# CPU_Power.net
KiCad netlist of a schematic drawn in Altium Designer
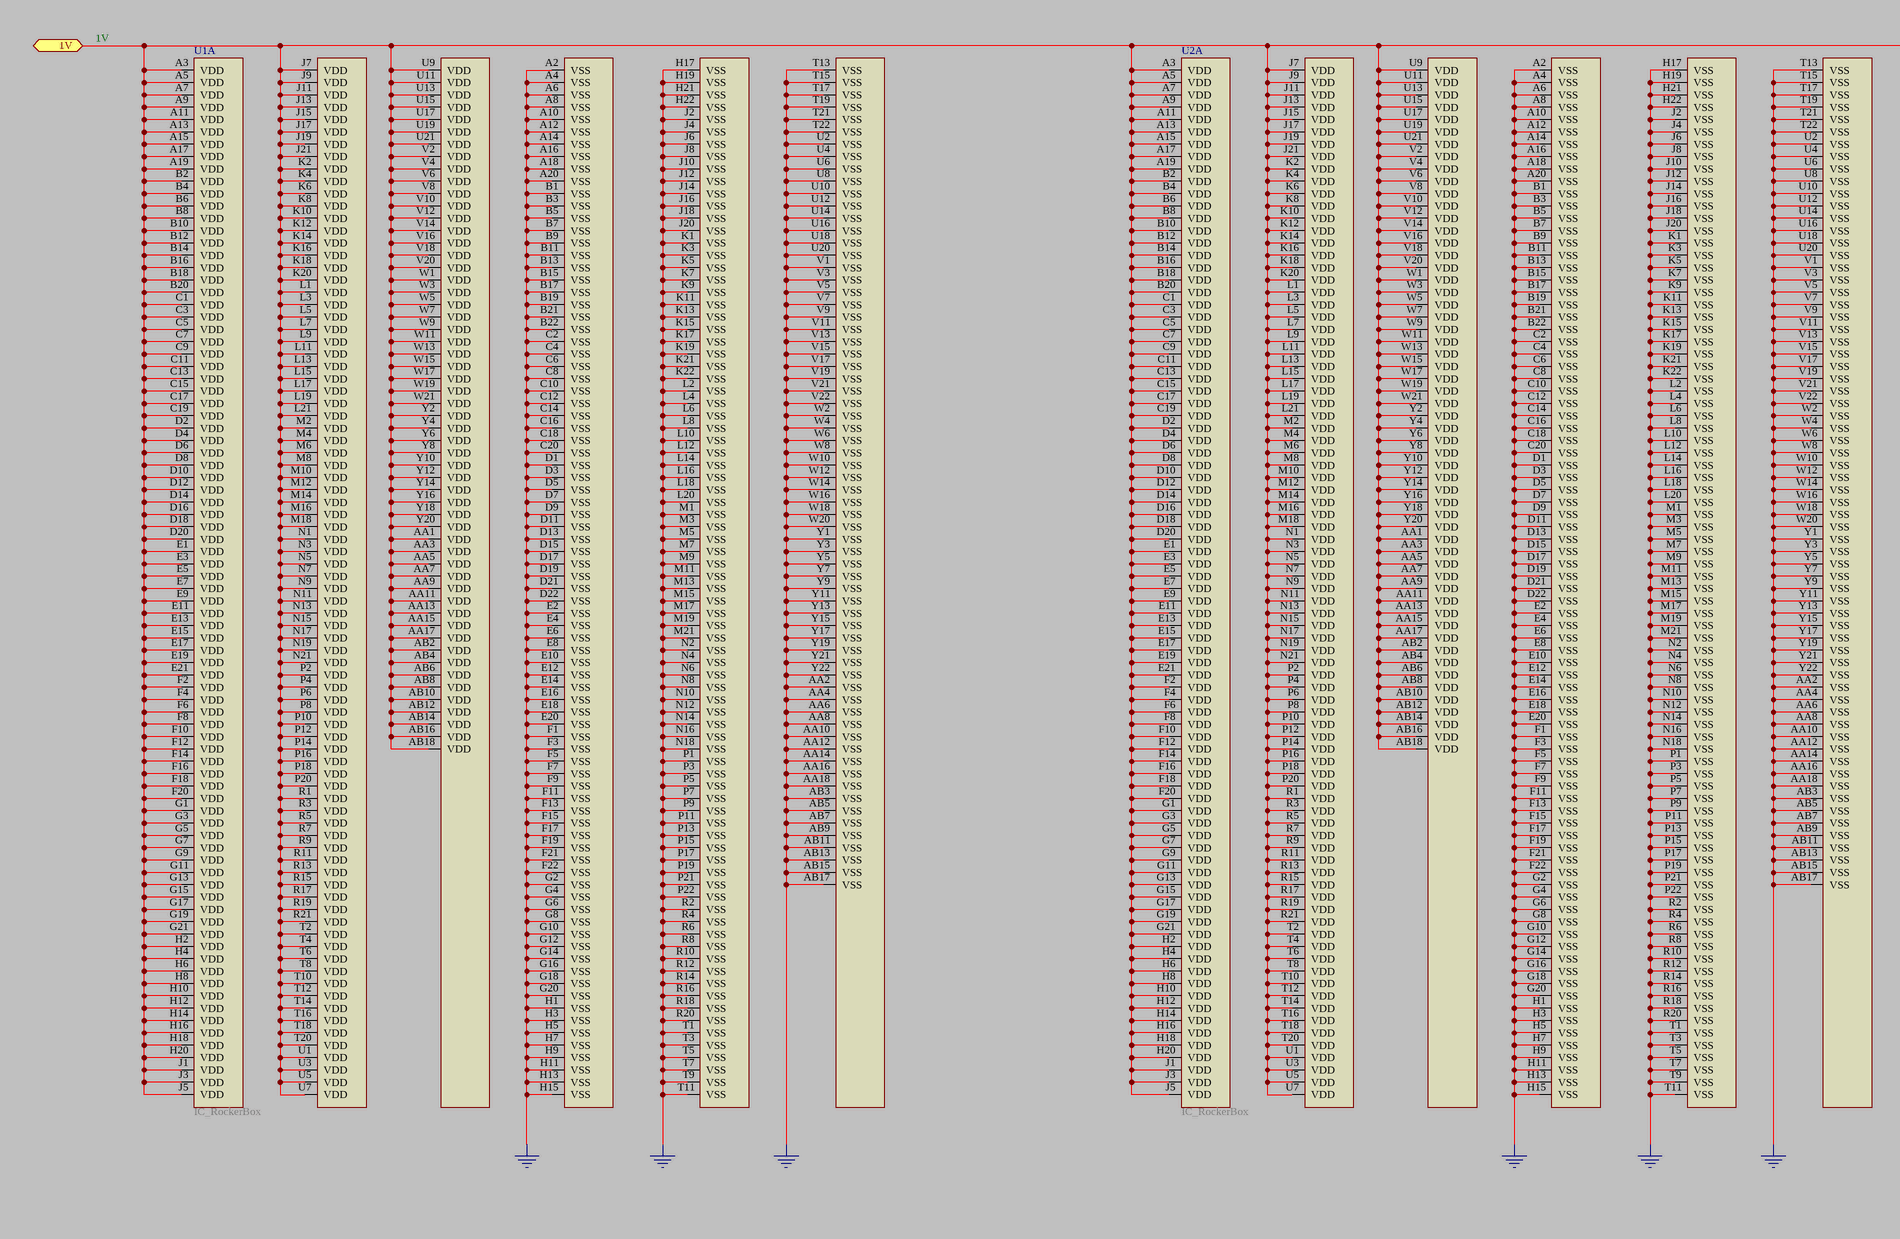
[diagram p0: CPU_Power.SchDoc, top left]
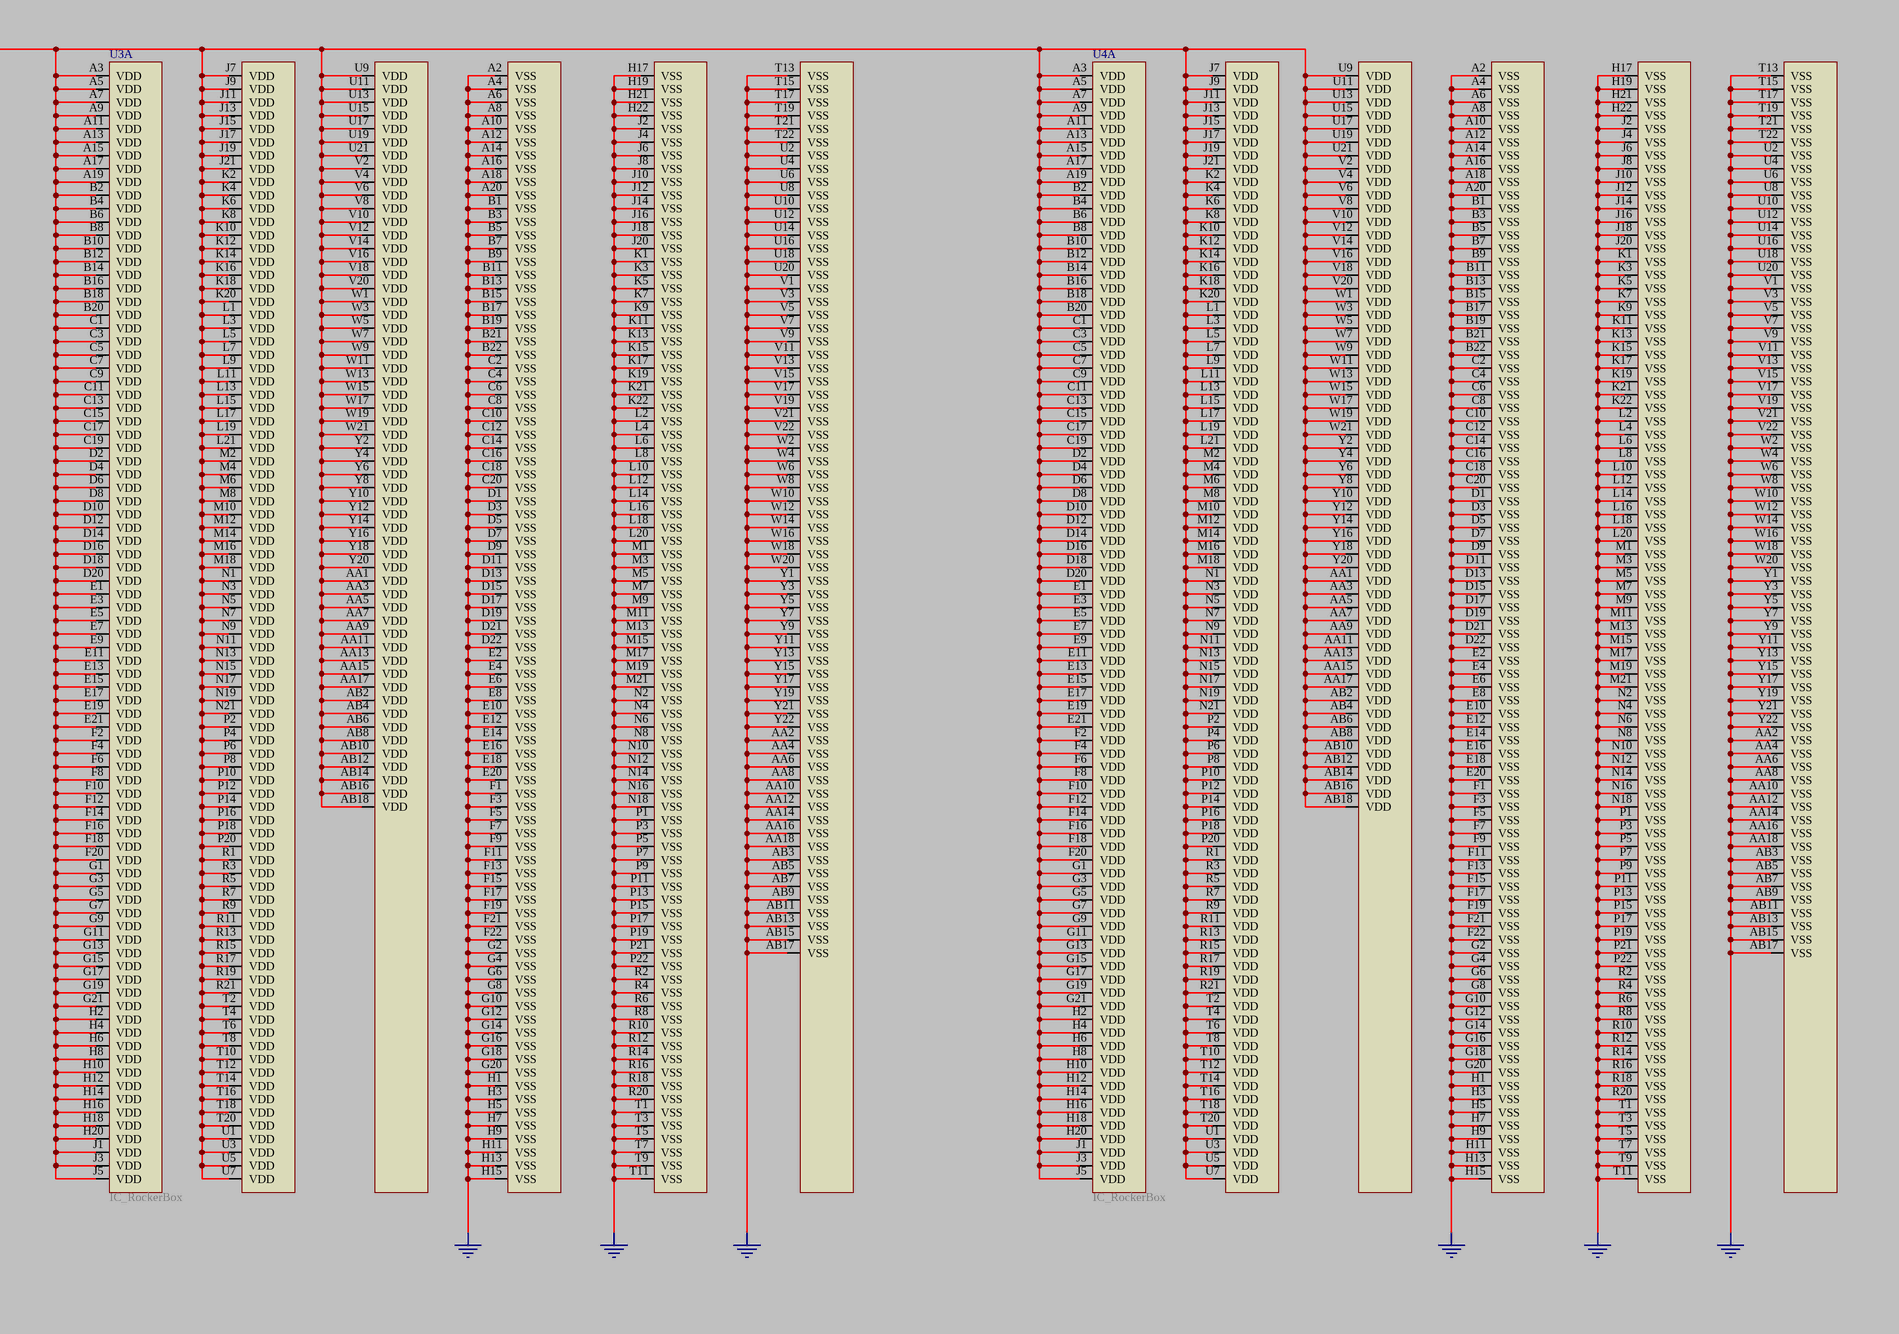
[diagram p1: CPU_Power.SchDoc, top right]
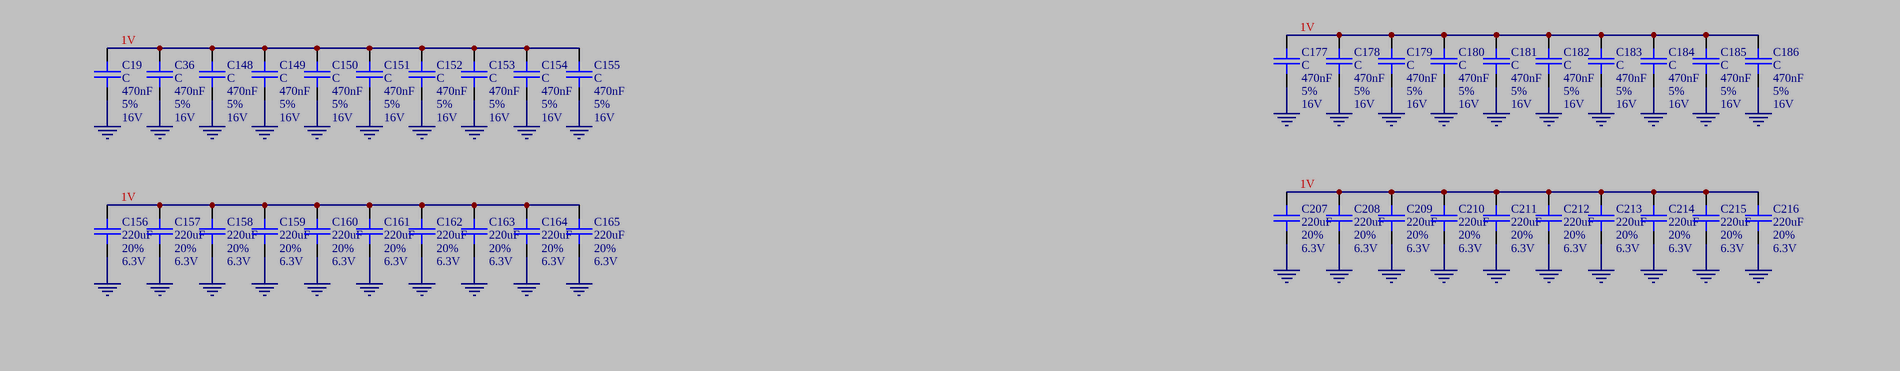
[diagram p2: CPU_Power.SchDoc, bottom left]
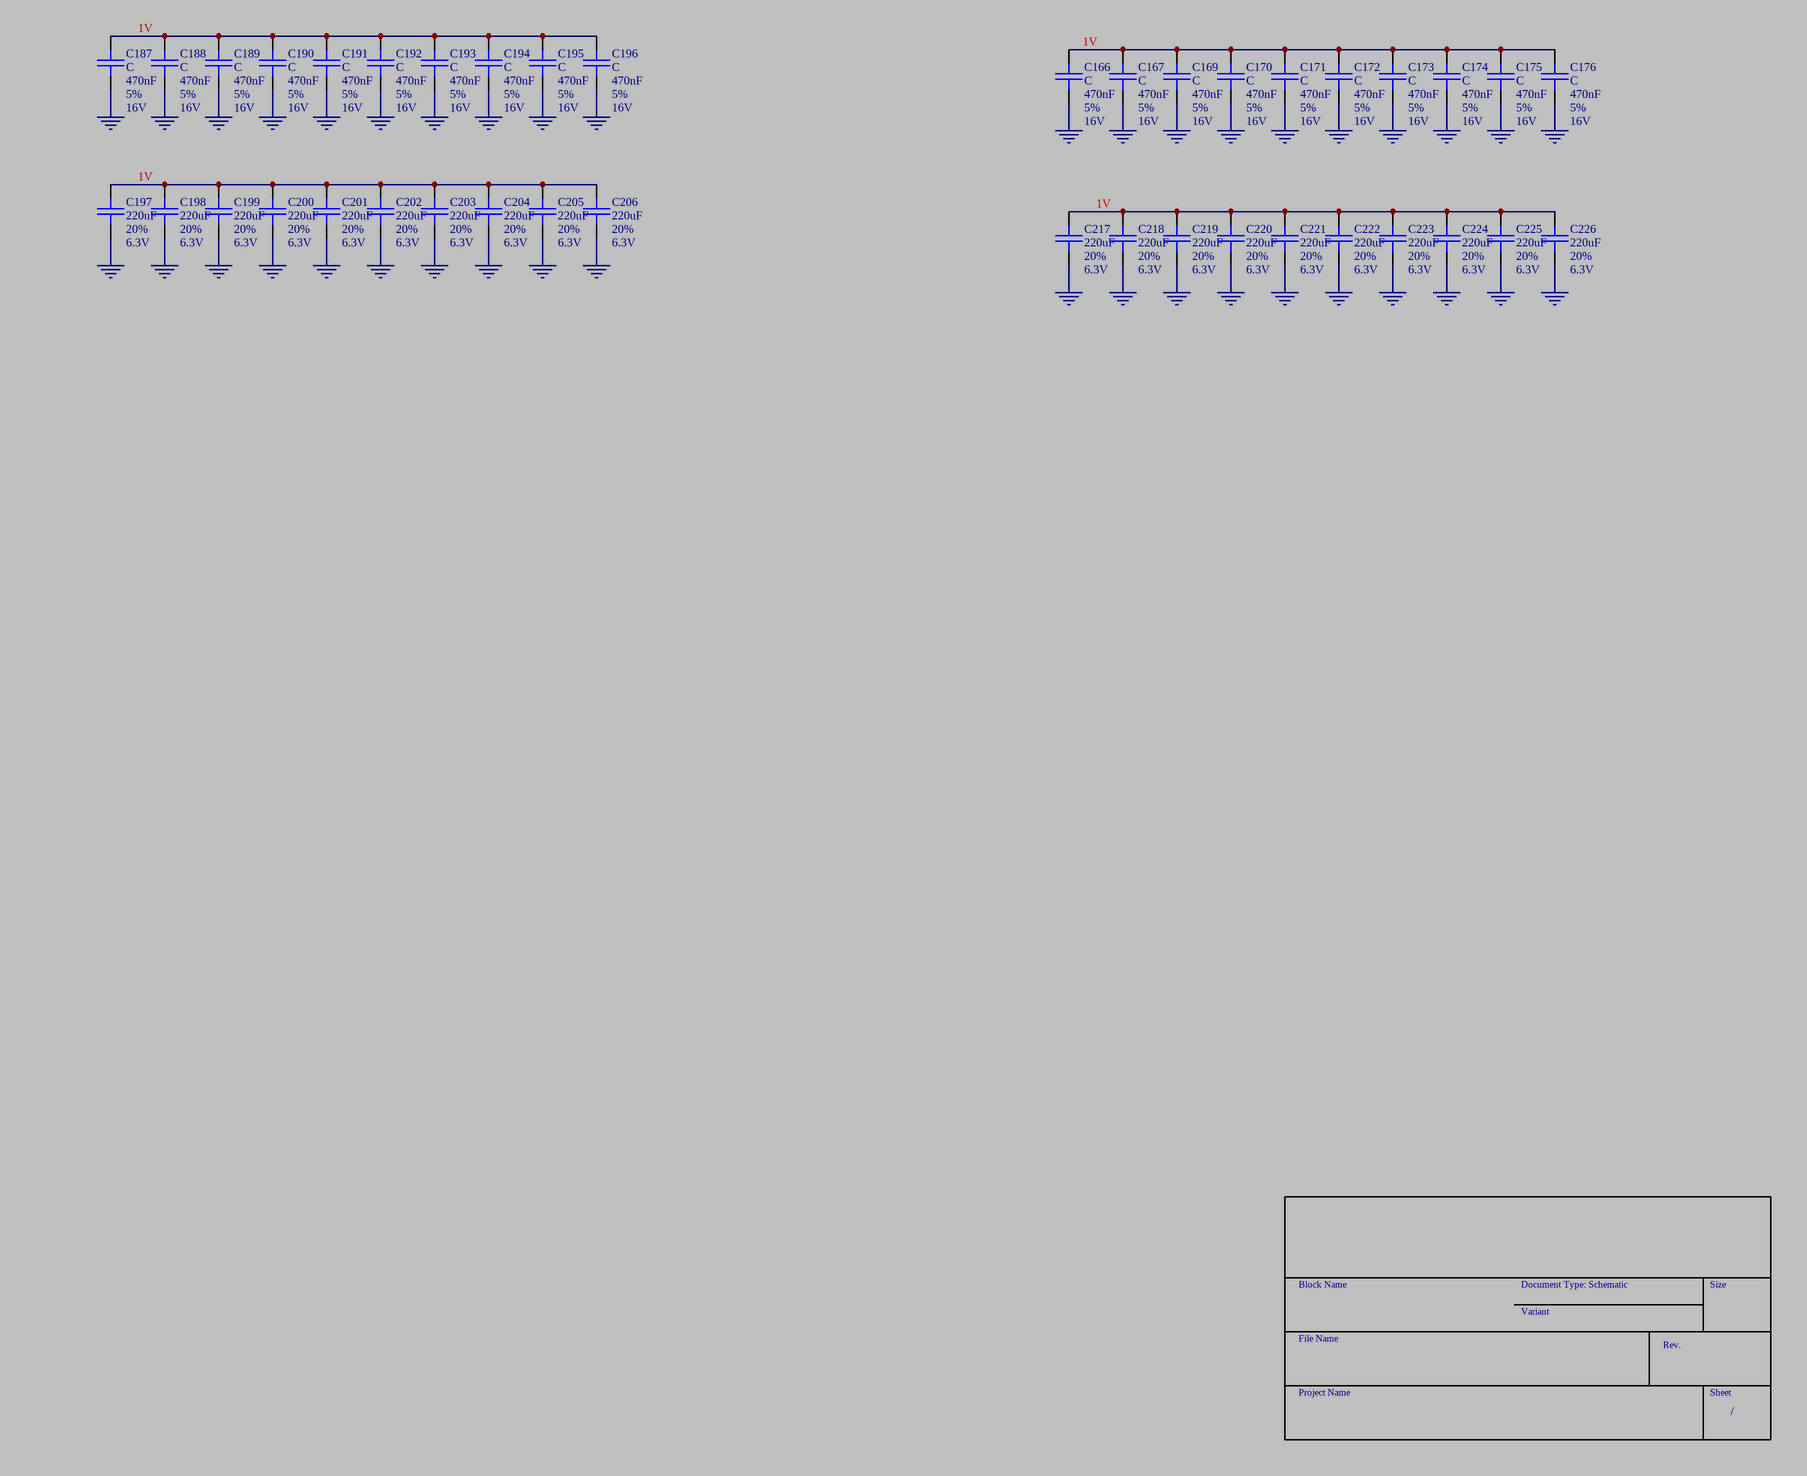
[diagram p3: CPU_Power.SchDoc, bottom right]

(export (version "E")
  (design (tool "Eeschema 10.0.6"))
  (components
    (comp (ref "C19")
      (value "C")
      (footprint "SMD_0603_CAPC1608X95N")
      (fields
        (field (name "DB_PART_NUMBER") "CAP000028169")
        (field (name "DB_VALUE") "470nF")
        (field (name "DB_TOLERANCE") "5%")
        (field (name "DB_VOLTAGE") "16V")
        (field (name "DB_MANUFACTURER_PART") "KEMET    C0603C474J4RAC")
      )
      (libsource (lib "Database_Libs1") (part "C"))
    )
    (comp (ref "C36")
      (value "C")
      (footprint "SMD_0603_CAPC1608X95N")
      (fields
        (field (name "DB_PART_NUMBER") "CAP000028169")
        (field (name "DB_VALUE") "470nF")
        (field (name "DB_TOLERANCE") "5%")
        (field (name "DB_VOLTAGE") "16V")
        (field (name "DB_MANUFACTURER_PART") "KEMET    C0603C474J4RAC")
      )
      (libsource (lib "Database_Libs1") (part "C"))
    )
    (comp (ref "C148")
      (value "C")
      (footprint "SMD_0603_CAPC1608X95N")
      (fields
        (field (name "DB_PART_NUMBER") "CAP000028169")
        (field (name "DB_VALUE") "470nF")
        (field (name "DB_TOLERANCE") "5%")
        (field (name "DB_VOLTAGE") "16V")
        (field (name "DB_MANUFACTURER_PART") "KEMET    C0603C474J4RAC")
      )
      (libsource (lib "Database_Libs1") (part "C"))
    )
    (comp (ref "C149")
      (value "C")
      (footprint "SMD_0603_CAPC1608X95N")
      (fields
        (field (name "DB_PART_NUMBER") "CAP000028169")
        (field (name "DB_VALUE") "470nF")
        (field (name "DB_TOLERANCE") "5%")
        (field (name "DB_VOLTAGE") "16V")
        (field (name "DB_MANUFACTURER_PART") "KEMET    C0603C474J4RAC")
      )
      (libsource (lib "Database_Libs1") (part "C"))
    )
    (comp (ref "C150")
      (value "C")
      (footprint "SMD_0603_CAPC1608X95N")
      (fields
        (field (name "DB_PART_NUMBER") "CAP000028169")
        (field (name "DB_VALUE") "470nF")
        (field (name "DB_TOLERANCE") "5%")
        (field (name "DB_VOLTAGE") "16V")
        (field (name "DB_MANUFACTURER_PART") "KEMET    C0603C474J4RAC")
      )
      (libsource (lib "Database_Libs1") (part "C"))
    )
    (comp (ref "C151")
      (value "C")
      (footprint "SMD_0603_CAPC1608X95N")
      (fields
        (field (name "DB_PART_NUMBER") "CAP000028169")
        (field (name "DB_VALUE") "470nF")
        (field (name "DB_TOLERANCE") "5%")
        (field (name "DB_VOLTAGE") "16V")
        (field (name "DB_MANUFACTURER_PART") "KEMET    C0603C474J4RAC")
      )
      (libsource (lib "Database_Libs1") (part "C"))
    )
    (comp (ref "C152")
      (value "C")
      (footprint "SMD_0603_CAPC1608X95N")
      (fields
        (field (name "DB_PART_NUMBER") "CAP000028169")
        (field (name "DB_VALUE") "470nF")
        (field (name "DB_TOLERANCE") "5%")
        (field (name "DB_VOLTAGE") "16V")
        (field (name "DB_MANUFACTURER_PART") "KEMET    C0603C474J4RAC")
      )
      (libsource (lib "Database_Libs1") (part "C"))
    )
    (comp (ref "C153")
      (value "C")
      (footprint "SMD_0603_CAPC1608X95N")
      (fields
        (field (name "DB_PART_NUMBER") "CAP000028169")
        (field (name "DB_VALUE") "470nF")
        (field (name "DB_TOLERANCE") "5%")
        (field (name "DB_VOLTAGE") "16V")
        (field (name "DB_MANUFACTURER_PART") "KEMET    C0603C474J4RAC")
      )
      (libsource (lib "Database_Libs1") (part "C"))
    )
    (comp (ref "C154")
      (value "C")
      (footprint "SMD_0603_CAPC1608X95N")
      (fields
        (field (name "DB_PART_NUMBER") "CAP000028169")
        (field (name "DB_VALUE") "470nF")
        (field (name "DB_TOLERANCE") "5%")
        (field (name "DB_VOLTAGE") "16V")
        (field (name "DB_MANUFACTURER_PART") "KEMET    C0603C474J4RAC")
      )
      (libsource (lib "Database_Libs1") (part "C"))
    )
    (comp (ref "C155")
      (value "C")
      (footprint "SMD_0603_CAPC1608X95N")
      (fields
        (field (name "DB_PART_NUMBER") "CAP000028169")
        (field (name "DB_VALUE") "470nF")
        (field (name "DB_TOLERANCE") "5%")
        (field (name "DB_VOLTAGE") "16V")
        (field (name "DB_MANUFACTURER_PART") "KEMET    C0603C474J4RAC")
      )
      (libsource (lib "Database_Libs1") (part "C"))
    )
    (comp (ref "C156")
      (value "C")
      (footprint "SMD_1210_CAPC3225X279N")
      (fields
        (field (name "DB_PART_NUMBER") "CAP000047355")
        (field (name "DB_VALUE") "220uF")
        (field (name "DB_TOLERANCE") "20%")
        (field (name "DB_VOLTAGE") "6.3V")
        (field (name "DB_MANUFACTURER_PART") "SAMSUNG    CL32A227MQVNNNE")
        (field (name "DB_APPROVED_BY") "VSN")
      )
      (libsource (lib "Database_Libs1") (part "C"))
    )
    (comp (ref "C157")
      (value "C")
      (footprint "SMD_1210_CAPC3225X279N")
      (fields
        (field (name "DB_PART_NUMBER") "CAP000047355")
        (field (name "DB_VALUE") "220uF")
        (field (name "DB_TOLERANCE") "20%")
        (field (name "DB_VOLTAGE") "6.3V")
        (field (name "DB_MANUFACTURER_PART") "SAMSUNG    CL32A227MQVNNNE")
        (field (name "DB_APPROVED_BY") "VSN")
      )
      (libsource (lib "Database_Libs1") (part "C"))
    )
    (comp (ref "C158")
      (value "C")
      (footprint "SMD_1210_CAPC3225X279N")
      (fields
        (field (name "DB_PART_NUMBER") "CAP000047355")
        (field (name "DB_VALUE") "220uF")
        (field (name "DB_TOLERANCE") "20%")
        (field (name "DB_VOLTAGE") "6.3V")
        (field (name "DB_MANUFACTURER_PART") "SAMSUNG    CL32A227MQVNNNE")
        (field (name "DB_APPROVED_BY") "VSN")
      )
      (libsource (lib "Database_Libs1") (part "C"))
    )
    (comp (ref "C159")
      (value "C")
      (footprint "SMD_1210_CAPC3225X279N")
      (fields
        (field (name "DB_PART_NUMBER") "CAP000047355")
        (field (name "DB_VALUE") "220uF")
        (field (name "DB_TOLERANCE") "20%")
        (field (name "DB_VOLTAGE") "6.3V")
        (field (name "DB_MANUFACTURER_PART") "SAMSUNG    CL32A227MQVNNNE")
        (field (name "DB_APPROVED_BY") "VSN")
      )
      (libsource (lib "Database_Libs1") (part "C"))
    )
    (comp (ref "C160")
      (value "C")
      (footprint "SMD_1210_CAPC3225X279N")
      (fields
        (field (name "DB_PART_NUMBER") "CAP000047355")
        (field (name "DB_VALUE") "220uF")
        (field (name "DB_TOLERANCE") "20%")
        (field (name "DB_VOLTAGE") "6.3V")
        (field (name "DB_MANUFACTURER_PART") "SAMSUNG    CL32A227MQVNNNE")
        (field (name "DB_APPROVED_BY") "VSN")
      )
      (libsource (lib "Database_Libs1") (part "C"))
    )
    (comp (ref "C161")
      (value "C")
      (footprint "SMD_1210_CAPC3225X279N")
      (fields
        (field (name "DB_PART_NUMBER") "CAP000047355")
        (field (name "DB_VALUE") "220uF")
        (field (name "DB_TOLERANCE") "20%")
        (field (name "DB_VOLTAGE") "6.3V")
        (field (name "DB_MANUFACTURER_PART") "SAMSUNG    CL32A227MQVNNNE")
        (field (name "DB_APPROVED_BY") "VSN")
      )
      (libsource (lib "Database_Libs1") (part "C"))
    )
    (comp (ref "C162")
      (value "C")
      (footprint "SMD_1210_CAPC3225X279N")
      (fields
        (field (name "DB_PART_NUMBER") "CAP000047355")
        (field (name "DB_VALUE") "220uF")
        (field (name "DB_TOLERANCE") "20%")
        (field (name "DB_VOLTAGE") "6.3V")
        (field (name "DB_MANUFACTURER_PART") "SAMSUNG    CL32A227MQVNNNE")
        (field (name "DB_APPROVED_BY") "VSN")
      )
      (libsource (lib "Database_Libs1") (part "C"))
    )
    (comp (ref "C163")
      (value "C")
      (footprint "SMD_1210_CAPC3225X279N")
      (fields
        (field (name "DB_PART_NUMBER") "CAP000047355")
        (field (name "DB_VALUE") "220uF")
        (field (name "DB_TOLERANCE") "20%")
        (field (name "DB_VOLTAGE") "6.3V")
        (field (name "DB_MANUFACTURER_PART") "SAMSUNG    CL32A227MQVNNNE")
        (field (name "DB_APPROVED_BY") "VSN")
      )
      (libsource (lib "Database_Libs1") (part "C"))
    )
    (comp (ref "C164")
      (value "C")
      (footprint "SMD_1210_CAPC3225X279N")
      (fields
        (field (name "DB_PART_NUMBER") "CAP000047355")
        (field (name "DB_VALUE") "220uF")
        (field (name "DB_TOLERANCE") "20%")
        (field (name "DB_VOLTAGE") "6.3V")
        (field (name "DB_MANUFACTURER_PART") "SAMSUNG    CL32A227MQVNNNE")
        (field (name "DB_APPROVED_BY") "VSN")
      )
      (libsource (lib "Database_Libs1") (part "C"))
    )
    (comp (ref "C165")
      (value "C")
      (footprint "SMD_1210_CAPC3225X279N")
      (fields
        (field (name "DB_PART_NUMBER") "CAP000047355")
        (field (name "DB_VALUE") "220uF")
        (field (name "DB_TOLERANCE") "20%")
        (field (name "DB_VOLTAGE") "6.3V")
        (field (name "DB_MANUFACTURER_PART") "SAMSUNG    CL32A227MQVNNNE")
        (field (name "DB_APPROVED_BY") "VSN")
      )
      (libsource (lib "Database_Libs1") (part "C"))
    )
    (comp (ref "C166")
      (value "C")
      (footprint "SMD_0603_CAPC1608X95N")
      (fields
        (field (name "DB_PART_NUMBER") "CAP000028169")
        (field (name "DB_VALUE") "470nF")
        (field (name "DB_TOLERANCE") "5%")
        (field (name "DB_VOLTAGE") "16V")
        (field (name "DB_MANUFACTURER_PART") "KEMET    C0603C474J4RAC")
      )
      (libsource (lib "Database_Libs1") (part "C"))
    )
    (comp (ref "C167")
      (value "C")
      (footprint "SMD_0603_CAPC1608X95N")
      (fields
        (field (name "DB_PART_NUMBER") "CAP000028169")
        (field (name "DB_VALUE") "470nF")
        (field (name "DB_TOLERANCE") "5%")
        (field (name "DB_VOLTAGE") "16V")
        (field (name "DB_MANUFACTURER_PART") "KEMET    C0603C474J4RAC")
      )
      (libsource (lib "Database_Libs1") (part "C"))
    )
    (comp (ref "C169")
      (value "C")
      (footprint "SMD_0603_CAPC1608X95N")
      (fields
        (field (name "DB_PART_NUMBER") "CAP000028169")
        (field (name "DB_VALUE") "470nF")
        (field (name "DB_TOLERANCE") "5%")
        (field (name "DB_VOLTAGE") "16V")
        (field (name "DB_MANUFACTURER_PART") "KEMET    C0603C474J4RAC")
      )
      (libsource (lib "Database_Libs1") (part "C"))
    )
    (comp (ref "C170")
      (value "C")
      (footprint "SMD_0603_CAPC1608X95N")
      (fields
        (field (name "DB_PART_NUMBER") "CAP000028169")
        (field (name "DB_VALUE") "470nF")
        (field (name "DB_TOLERANCE") "5%")
        (field (name "DB_VOLTAGE") "16V")
        (field (name "DB_MANUFACTURER_PART") "KEMET    C0603C474J4RAC")
      )
      (libsource (lib "Database_Libs1") (part "C"))
    )
    (comp (ref "C171")
      (value "C")
      (footprint "SMD_0603_CAPC1608X95N")
      (fields
        (field (name "DB_PART_NUMBER") "CAP000028169")
        (field (name "DB_VALUE") "470nF")
        (field (name "DB_TOLERANCE") "5%")
        (field (name "DB_VOLTAGE") "16V")
        (field (name "DB_MANUFACTURER_PART") "KEMET    C0603C474J4RAC")
      )
      (libsource (lib "Database_Libs1") (part "C"))
    )
    (comp (ref "C172")
      (value "C")
      (footprint "SMD_0603_CAPC1608X95N")
      (fields
        (field (name "DB_PART_NUMBER") "CAP000028169")
        (field (name "DB_VALUE") "470nF")
        (field (name "DB_TOLERANCE") "5%")
        (field (name "DB_VOLTAGE") "16V")
        (field (name "DB_MANUFACTURER_PART") "KEMET    C0603C474J4RAC")
      )
      (libsource (lib "Database_Libs1") (part "C"))
    )
    (comp (ref "C173")
      (value "C")
      (footprint "SMD_0603_CAPC1608X95N")
      (fields
        (field (name "DB_PART_NUMBER") "CAP000028169")
        (field (name "DB_VALUE") "470nF")
        (field (name "DB_TOLERANCE") "5%")
        (field (name "DB_VOLTAGE") "16V")
        (field (name "DB_MANUFACTURER_PART") "KEMET    C0603C474J4RAC")
      )
      (libsource (lib "Database_Libs1") (part "C"))
    )
    (comp (ref "C174")
      (value "C")
      (footprint "SMD_0603_CAPC1608X95N")
      (fields
        (field (name "DB_PART_NUMBER") "CAP000028169")
        (field (name "DB_VALUE") "470nF")
        (field (name "DB_TOLERANCE") "5%")
        (field (name "DB_VOLTAGE") "16V")
        (field (name "DB_MANUFACTURER_PART") "KEMET    C0603C474J4RAC")
      )
      (libsource (lib "Database_Libs1") (part "C"))
    )
    (comp (ref "C175")
      (value "C")
      (footprint "SMD_0603_CAPC1608X95N")
      (fields
        (field (name "DB_PART_NUMBER") "CAP000028169")
        (field (name "DB_VALUE") "470nF")
        (field (name "DB_TOLERANCE") "5%")
        (field (name "DB_VOLTAGE") "16V")
        (field (name "DB_MANUFACTURER_PART") "KEMET    C0603C474J4RAC")
      )
      (libsource (lib "Database_Libs1") (part "C"))
    )
    (comp (ref "C176")
      (value "C")
      (footprint "SMD_0603_CAPC1608X95N")
      (fields
        (field (name "DB_PART_NUMBER") "CAP000028169")
        (field (name "DB_VALUE") "470nF")
        (field (name "DB_TOLERANCE") "5%")
        (field (name "DB_VOLTAGE") "16V")
        (field (name "DB_MANUFACTURER_PART") "KEMET    C0603C474J4RAC")
      )
      (libsource (lib "Database_Libs1") (part "C"))
    )
    (comp (ref "C177")
      (value "C")
      (footprint "SMD_0603_CAPC1608X95N")
      (fields
        (field (name "DB_PART_NUMBER") "CAP000028169")
        (field (name "DB_VALUE") "470nF")
        (field (name "DB_TOLERANCE") "5%")
        (field (name "DB_VOLTAGE") "16V")
        (field (name "DB_MANUFACTURER_PART") "KEMET    C0603C474J4RAC")
      )
      (libsource (lib "Database_Libs1") (part "C"))
    )
    (comp (ref "C178")
      (value "C")
      (footprint "SMD_0603_CAPC1608X95N")
      (fields
        (field (name "DB_PART_NUMBER") "CAP000028169")
        (field (name "DB_VALUE") "470nF")
        (field (name "DB_TOLERANCE") "5%")
        (field (name "DB_VOLTAGE") "16V")
        (field (name "DB_MANUFACTURER_PART") "KEMET    C0603C474J4RAC")
      )
      (libsource (lib "Database_Libs1") (part "C"))
    )
    (comp (ref "C179")
      (value "C")
      (footprint "SMD_0603_CAPC1608X95N")
      (fields
        (field (name "DB_PART_NUMBER") "CAP000028169")
        (field (name "DB_VALUE") "470nF")
        (field (name "DB_TOLERANCE") "5%")
        (field (name "DB_VOLTAGE") "16V")
        (field (name "DB_MANUFACTURER_PART") "KEMET    C0603C474J4RAC")
      )
      (libsource (lib "Database_Libs1") (part "C"))
    )
    (comp (ref "C180")
      (value "C")
      (footprint "SMD_0603_CAPC1608X95N")
      (fields
        (field (name "DB_PART_NUMBER") "CAP000028169")
        (field (name "DB_VALUE") "470nF")
        (field (name "DB_TOLERANCE") "5%")
        (field (name "DB_VOLTAGE") "16V")
        (field (name "DB_MANUFACTURER_PART") "KEMET    C0603C474J4RAC")
      )
      (libsource (lib "Database_Libs1") (part "C"))
    )
    (comp (ref "C181")
      (value "C")
      (footprint "SMD_0603_CAPC1608X95N")
      (fields
        (field (name "DB_PART_NUMBER") "CAP000028169")
        (field (name "DB_VALUE") "470nF")
        (field (name "DB_TOLERANCE") "5%")
        (field (name "DB_VOLTAGE") "16V")
        (field (name "DB_MANUFACTURER_PART") "KEMET    C0603C474J4RAC")
      )
      (libsource (lib "Database_Libs1") (part "C"))
    )
    (comp (ref "C182")
      (value "C")
      (footprint "SMD_0603_CAPC1608X95N")
      (fields
        (field (name "DB_PART_NUMBER") "CAP000028169")
        (field (name "DB_VALUE") "470nF")
        (field (name "DB_TOLERANCE") "5%")
        (field (name "DB_VOLTAGE") "16V")
        (field (name "DB_MANUFACTURER_PART") "KEMET    C0603C474J4RAC")
      )
      (libsource (lib "Database_Libs1") (part "C"))
    )
    (comp (ref "C183")
      (value "C")
      (footprint "SMD_0603_CAPC1608X95N")
      (fields
        (field (name "DB_PART_NUMBER") "CAP000028169")
        (field (name "DB_VALUE") "470nF")
        (field (name "DB_TOLERANCE") "5%")
        (field (name "DB_VOLTAGE") "16V")
        (field (name "DB_MANUFACTURER_PART") "KEMET    C0603C474J4RAC")
      )
      (libsource (lib "Database_Libs1") (part "C"))
    )
    (comp (ref "C184")
      (value "C")
      (footprint "SMD_0603_CAPC1608X95N")
      (fields
        (field (name "DB_PART_NUMBER") "CAP000028169")
        (field (name "DB_VALUE") "470nF")
        (field (name "DB_TOLERANCE") "5%")
        (field (name "DB_VOLTAGE") "16V")
        (field (name "DB_MANUFACTURER_PART") "KEMET    C0603C474J4RAC")
      )
      (libsource (lib "Database_Libs1") (part "C"))
    )
    (comp (ref "C185")
      (value "C")
      (footprint "SMD_0603_CAPC1608X95N")
      (fields
        (field (name "DB_PART_NUMBER") "CAP000028169")
        (field (name "DB_VALUE") "470nF")
        (field (name "DB_TOLERANCE") "5%")
        (field (name "DB_VOLTAGE") "16V")
        (field (name "DB_MANUFACTURER_PART") "KEMET    C0603C474J4RAC")
      )
      (libsource (lib "Database_Libs1") (part "C"))
    )
    (comp (ref "C186")
      (value "C")
      (footprint "SMD_0603_CAPC1608X95N")
      (fields
        (field (name "DB_PART_NUMBER") "CAP000028169")
        (field (name "DB_VALUE") "470nF")
        (field (name "DB_TOLERANCE") "5%")
        (field (name "DB_VOLTAGE") "16V")
        (field (name "DB_MANUFACTURER_PART") "KEMET    C0603C474J4RAC")
      )
      (libsource (lib "Database_Libs1") (part "C"))
    )
    (comp (ref "C187")
      (value "C")
      (footprint "SMD_0603_CAPC1608X95N")
      (fields
        (field (name "DB_PART_NUMBER") "CAP000028169")
        (field (name "DB_VALUE") "470nF")
        (field (name "DB_TOLERANCE") "5%")
        (field (name "DB_VOLTAGE") "16V")
        (field (name "DB_MANUFACTURER_PART") "KEMET    C0603C474J4RAC")
      )
      (libsource (lib "Database_Libs1") (part "C"))
    )
    (comp (ref "C188")
      (value "C")
      (footprint "SMD_0603_CAPC1608X95N")
      (fields
        (field (name "DB_PART_NUMBER") "CAP000028169")
        (field (name "DB_VALUE") "470nF")
        (field (name "DB_TOLERANCE") "5%")
        (field (name "DB_VOLTAGE") "16V")
        (field (name "DB_MANUFACTURER_PART") "KEMET    C0603C474J4RAC")
      )
      (libsource (lib "Database_Libs1") (part "C"))
    )
    (comp (ref "C189")
      (value "C")
      (footprint "SMD_0603_CAPC1608X95N")
      (fields
        (field (name "DB_PART_NUMBER") "CAP000028169")
        (field (name "DB_VALUE") "470nF")
        (field (name "DB_TOLERANCE") "5%")
        (field (name "DB_VOLTAGE") "16V")
        (field (name "DB_MANUFACTURER_PART") "KEMET    C0603C474J4RAC")
      )
      (libsource (lib "Database_Libs1") (part "C"))
    )
    (comp (ref "C190")
      (value "C")
      (footprint "SMD_0603_CAPC1608X95N")
      (fields
        (field (name "DB_PART_NUMBER") "CAP000028169")
        (field (name "DB_VALUE") "470nF")
        (field (name "DB_TOLERANCE") "5%")
        (field (name "DB_VOLTAGE") "16V")
        (field (name "DB_MANUFACTURER_PART") "KEMET    C0603C474J4RAC")
      )
      (libsource (lib "Database_Libs1") (part "C"))
    )
    (comp (ref "C191")
      (value "C")
      (footprint "SMD_0603_CAPC1608X95N")
      (fields
        (field (name "DB_PART_NUMBER") "CAP000028169")
        (field (name "DB_VALUE") "470nF")
        (field (name "DB_TOLERANCE") "5%")
        (field (name "DB_VOLTAGE") "16V")
        (field (name "DB_MANUFACTURER_PART") "KEMET    C0603C474J4RAC")
      )
      (libsource (lib "Database_Libs1") (part "C"))
    )
    (comp (ref "C192")
      (value "C")
      (footprint "SMD_0603_CAPC1608X95N")
      (fields
        (field (name "DB_PART_NUMBER") "CAP000028169")
        (field (name "DB_VALUE") "470nF")
        (field (name "DB_TOLERANCE") "5%")
        (field (name "DB_VOLTAGE") "16V")
        (field (name "DB_MANUFACTURER_PART") "KEMET    C0603C474J4RAC")
      )
      (libsource (lib "Database_Libs1") (part "C"))
    )
    (comp (ref "C193")
      (value "C")
      (footprint "SMD_0603_CAPC1608X95N")
      (fields
        (field (name "DB_PART_NUMBER") "CAP000028169")
        (field (name "DB_VALUE") "470nF")
        (field (name "DB_TOLERANCE") "5%")
        (field (name "DB_VOLTAGE") "16V")
        (field (name "DB_MANUFACTURER_PART") "KEMET    C0603C474J4RAC")
      )
      (libsource (lib "Database_Libs1") (part "C"))
    )
    (comp (ref "C194")
      (value "C")
      (footprint "SMD_0603_CAPC1608X95N")
      (fields
        (field (name "DB_PART_NUMBER") "CAP000028169")
        (field (name "DB_VALUE") "470nF")
        (field (name "DB_TOLERANCE") "5%")
        (field (name "DB_VOLTAGE") "16V")
        (field (name "DB_MANUFACTURER_PART") "KEMET    C0603C474J4RAC")
      )
      (libsource (lib "Database_Libs1") (part "C"))
    )
    (comp (ref "C195")
      (value "C")
      (footprint "SMD_0603_CAPC1608X95N")
      (fields
        (field (name "DB_PART_NUMBER") "CAP000028169")
        (field (name "DB_VALUE") "470nF")
        (field (name "DB_TOLERANCE") "5%")
        (field (name "DB_VOLTAGE") "16V")
        (field (name "DB_MANUFACTURER_PART") "KEMET    C0603C474J4RAC")
      )
      (libsource (lib "Database_Libs1") (part "C"))
    )
    (comp (ref "C196")
      (value "C")
      (footprint "SMD_0603_CAPC1608X95N")
      (fields
        (field (name "DB_PART_NUMBER") "CAP000028169")
        (field (name "DB_VALUE") "470nF")
        (field (name "DB_TOLERANCE") "5%")
        (field (name "DB_VOLTAGE") "16V")
        (field (name "DB_MANUFACTURER_PART") "KEMET    C0603C474J4RAC")
      )
      (libsource (lib "Database_Libs1") (part "C"))
    )
    (comp (ref "C197")
      (value "C")
      (footprint "SMD_1210_CAPC3225X279N")
      (fields
        (field (name "DB_PART_NUMBER") "CAP000047355")
        (field (name "DB_VALUE") "220uF")
        (field (name "DB_TOLERANCE") "20%")
        (field (name "DB_VOLTAGE") "6.3V")
        (field (name "DB_MANUFACTURER_PART") "SAMSUNG    CL32A227MQVNNNE")
        (field (name "DB_APPROVED_BY") "VSN")
      )
      (libsource (lib "Database_Libs1") (part "C"))
    )
    (comp (ref "C198")
      (value "C")
      (footprint "SMD_1210_CAPC3225X279N")
      (fields
        (field (name "DB_PART_NUMBER") "CAP000047355")
        (field (name "DB_VALUE") "220uF")
        (field (name "DB_TOLERANCE") "20%")
        (field (name "DB_VOLTAGE") "6.3V")
        (field (name "DB_MANUFACTURER_PART") "SAMSUNG    CL32A227MQVNNNE")
        (field (name "DB_APPROVED_BY") "VSN")
      )
      (libsource (lib "Database_Libs1") (part "C"))
    )
    (comp (ref "C199")
      (value "C")
      (footprint "SMD_1210_CAPC3225X279N")
      (fields
        (field (name "DB_PART_NUMBER") "CAP000047355")
        (field (name "DB_VALUE") "220uF")
        (field (name "DB_TOLERANCE") "20%")
        (field (name "DB_VOLTAGE") "6.3V")
        (field (name "DB_MANUFACTURER_PART") "SAMSUNG    CL32A227MQVNNNE")
        (field (name "DB_APPROVED_BY") "VSN")
      )
      (libsource (lib "Database_Libs1") (part "C"))
    )
    (comp (ref "C200")
      (value "C")
      (footprint "SMD_1210_CAPC3225X279N")
      (fields
        (field (name "DB_PART_NUMBER") "CAP000047355")
        (field (name "DB_VALUE") "220uF")
        (field (name "DB_TOLERANCE") "20%")
        (field (name "DB_VOLTAGE") "6.3V")
        (field (name "DB_MANUFACTURER_PART") "SAMSUNG    CL32A227MQVNNNE")
        (field (name "DB_APPROVED_BY") "VSN")
      )
      (libsource (lib "Database_Libs1") (part "C"))
    )
    (comp (ref "C201")
      (value "C")
      (footprint "SMD_1210_CAPC3225X279N")
      (fields
        (field (name "DB_PART_NUMBER") "CAP000047355")
        (field (name "DB_VALUE") "220uF")
        (field (name "DB_TOLERANCE") "20%")
        (field (name "DB_VOLTAGE") "6.3V")
        (field (name "DB_MANUFACTURER_PART") "SAMSUNG    CL32A227MQVNNNE")
        (field (name "DB_APPROVED_BY") "VSN")
      )
      (libsource (lib "Database_Libs1") (part "C"))
    )
    (comp (ref "C202")
      (value "C")
      (footprint "SMD_1210_CAPC3225X279N")
      (fields
        (field (name "DB_PART_NUMBER") "CAP000047355")
        (field (name "DB_VALUE") "220uF")
        (field (name "DB_TOLERANCE") "20%")
        (field (name "DB_VOLTAGE") "6.3V")
        (field (name "DB_MANUFACTURER_PART") "SAMSUNG    CL32A227MQVNNNE")
        (field (name "DB_APPROVED_BY") "VSN")
      )
      (libsource (lib "Database_Libs1") (part "C"))
    )
    (comp (ref "C203")
      (value "C")
      (footprint "SMD_1210_CAPC3225X279N")
      (fields
        (field (name "DB_PART_NUMBER") "CAP000047355")
        (field (name "DB_VALUE") "220uF")
        (field (name "DB_TOLERANCE") "20%")
        (field (name "DB_VOLTAGE") "6.3V")
        (field (name "DB_MANUFACTURER_PART") "SAMSUNG    CL32A227MQVNNNE")
        (field (name "DB_APPROVED_BY") "VSN")
      )
      (libsource (lib "Database_Libs1") (part "C"))
    )
    (comp (ref "C204")
      (value "C")
      (footprint "SMD_1210_CAPC3225X279N")
      (fields
        (field (name "DB_PART_NUMBER") "CAP000047355")
        (field (name "DB_VALUE") "220uF")
        (field (name "DB_TOLERANCE") "20%")
        (field (name "DB_VOLTAGE") "6.3V")
        (field (name "DB_MANUFACTURER_PART") "SAMSUNG    CL32A227MQVNNNE")
        (field (name "DB_APPROVED_BY") "VSN")
      )
      (libsource (lib "Database_Libs1") (part "C"))
    )
    (comp (ref "C205")
      (value "C")
      (footprint "SMD_1210_CAPC3225X279N")
      (fields
        (field (name "DB_PART_NUMBER") "CAP000047355")
        (field (name "DB_VALUE") "220uF")
        (field (name "DB_TOLERANCE") "20%")
        (field (name "DB_VOLTAGE") "6.3V")
        (field (name "DB_MANUFACTURER_PART") "SAMSUNG    CL32A227MQVNNNE")
        (field (name "DB_APPROVED_BY") "VSN")
      )
      (libsource (lib "Database_Libs1") (part "C"))
    )
    (comp (ref "C206")
      (value "C")
      (footprint "SMD_1210_CAPC3225X279N")
      (fields
        (field (name "DB_PART_NUMBER") "CAP000047355")
        (field (name "DB_VALUE") "220uF")
        (field (name "DB_TOLERANCE") "20%")
        (field (name "DB_VOLTAGE") "6.3V")
        (field (name "DB_MANUFACTURER_PART") "SAMSUNG    CL32A227MQVNNNE")
        (field (name "DB_APPROVED_BY") "VSN")
      )
      (libsource (lib "Database_Libs1") (part "C"))
    )
    (comp (ref "C207")
      (value "C")
      (footprint "SMD_1210_CAPC3225X279N")
      (fields
        (field (name "DB_PART_NUMBER") "CAP000047355")
        (field (name "DB_VALUE") "220uF")
        (field (name "DB_TOLERANCE") "20%")
        (field (name "DB_VOLTAGE") "6.3V")
        (field (name "DB_MANUFACTURER_PART") "SAMSUNG    CL32A227MQVNNNE")
        (field (name "DB_APPROVED_BY") "VSN")
      )
      (libsource (lib "Database_Libs1") (part "C"))
    )
    (comp (ref "C208")
      (value "C")
      (footprint "SMD_1210_CAPC3225X279N")
      (fields
        (field (name "DB_PART_NUMBER") "CAP000047355")
        (field (name "DB_VALUE") "220uF")
        (field (name "DB_TOLERANCE") "20%")
        (field (name "DB_VOLTAGE") "6.3V")
        (field (name "DB_MANUFACTURER_PART") "SAMSUNG    CL32A227MQVNNNE")
        (field (name "DB_APPROVED_BY") "VSN")
      )
      (libsource (lib "Database_Libs1") (part "C"))
    )
    (comp (ref "C209")
      (value "C")
      (footprint "SMD_1210_CAPC3225X279N")
      (fields
        (field (name "DB_PART_NUMBER") "CAP000047355")
        (field (name "DB_VALUE") "220uF")
        (field (name "DB_TOLERANCE") "20%")
        (field (name "DB_VOLTAGE") "6.3V")
        (field (name "DB_MANUFACTURER_PART") "SAMSUNG    CL32A227MQVNNNE")
        (field (name "DB_APPROVED_BY") "VSN")
      )
      (libsource (lib "Database_Libs1") (part "C"))
    )
    (comp (ref "C210")
      (value "C")
      (footprint "SMD_1210_CAPC3225X279N")
      (fields
        (field (name "DB_PART_NUMBER") "CAP000047355")
        (field (name "DB_VALUE") "220uF")
        (field (name "DB_TOLERANCE") "20%")
        (field (name "DB_VOLTAGE") "6.3V")
        (field (name "DB_MANUFACTURER_PART") "SAMSUNG    CL32A227MQVNNNE")
        (field (name "DB_APPROVED_BY") "VSN")
      )
      (libsource (lib "Database_Libs1") (part "C"))
    )
    (comp (ref "C211")
      (value "C")
      (footprint "SMD_1210_CAPC3225X279N")
      (fields
        (field (name "DB_PART_NUMBER") "CAP000047355")
        (field (name "DB_VALUE") "220uF")
        (field (name "DB_TOLERANCE") "20%")
        (field (name "DB_VOLTAGE") "6.3V")
        (field (name "DB_MANUFACTURER_PART") "SAMSUNG    CL32A227MQVNNNE")
        (field (name "DB_APPROVED_BY") "VSN")
      )
      (libsource (lib "Database_Libs1") (part "C"))
    )
    (comp (ref "C212")
      (value "C")
      (footprint "SMD_1210_CAPC3225X279N")
      (fields
        (field (name "DB_PART_NUMBER") "CAP000047355")
        (field (name "DB_VALUE") "220uF")
        (field (name "DB_TOLERANCE") "20%")
        (field (name "DB_VOLTAGE") "6.3V")
        (field (name "DB_MANUFACTURER_PART") "SAMSUNG    CL32A227MQVNNNE")
        (field (name "DB_APPROVED_BY") "VSN")
      )
      (libsource (lib "Database_Libs1") (part "C"))
    )
    (comp (ref "C213")
      (value "C")
      (footprint "SMD_1210_CAPC3225X279N")
      (fields
        (field (name "DB_PART_NUMBER") "CAP000047355")
        (field (name "DB_VALUE") "220uF")
        (field (name "DB_TOLERANCE") "20%")
        (field (name "DB_VOLTAGE") "6.3V")
        (field (name "DB_MANUFACTURER_PART") "SAMSUNG    CL32A227MQVNNNE")
        (field (name "DB_APPROVED_BY") "VSN")
      )
      (libsource (lib "Database_Libs1") (part "C"))
    )
    (comp (ref "C214")
      (value "C")
      (footprint "SMD_1210_CAPC3225X279N")
      (fields
        (field (name "DB_PART_NUMBER") "CAP000047355")
        (field (name "DB_VALUE") "220uF")
        (field (name "DB_TOLERANCE") "20%")
        (field (name "DB_VOLTAGE") "6.3V")
        (field (name "DB_MANUFACTURER_PART") "SAMSUNG    CL32A227MQVNNNE")
        (field (name "DB_APPROVED_BY") "VSN")
      )
      (libsource (lib "Database_Libs1") (part "C"))
    )
    (comp (ref "C215")
      (value "C")
      (footprint "SMD_1210_CAPC3225X279N")
      (fields
        (field (name "DB_PART_NUMBER") "CAP000047355")
        (field (name "DB_VALUE") "220uF")
        (field (name "DB_TOLERANCE") "20%")
        (field (name "DB_VOLTAGE") "6.3V")
        (field (name "DB_MANUFACTURER_PART") "SAMSUNG    CL32A227MQVNNNE")
        (field (name "DB_APPROVED_BY") "VSN")
      )
      (libsource (lib "Database_Libs1") (part "C"))
    )
    (comp (ref "C216")
      (value "C")
      (footprint "SMD_1210_CAPC3225X279N")
      (fields
        (field (name "DB_PART_NUMBER") "CAP000047355")
        (field (name "DB_VALUE") "220uF")
        (field (name "DB_TOLERANCE") "20%")
        (field (name "DB_VOLTAGE") "6.3V")
        (field (name "DB_MANUFACTURER_PART") "SAMSUNG    CL32A227MQVNNNE")
        (field (name "DB_APPROVED_BY") "VSN")
      )
      (libsource (lib "Database_Libs1") (part "C"))
    )
    (comp (ref "C217")
      (value "C")
      (footprint "SMD_1210_CAPC3225X279N")
      (fields
        (field (name "DB_PART_NUMBER") "CAP000047355")
        (field (name "DB_VALUE") "220uF")
        (field (name "DB_TOLERANCE") "20%")
        (field (name "DB_VOLTAGE") "6.3V")
        (field (name "DB_MANUFACTURER_PART") "SAMSUNG    CL32A227MQVNNNE")
        (field (name "DB_APPROVED_BY") "VSN")
      )
      (libsource (lib "Database_Libs1") (part "C"))
    )
    (comp (ref "C218")
      (value "C")
      (footprint "SMD_1210_CAPC3225X279N")
      (fields
        (field (name "DB_PART_NUMBER") "CAP000047355")
        (field (name "DB_VALUE") "220uF")
        (field (name "DB_TOLERANCE") "20%")
        (field (name "DB_VOLTAGE") "6.3V")
        (field (name "DB_MANUFACTURER_PART") "SAMSUNG    CL32A227MQVNNNE")
        (field (name "DB_APPROVED_BY") "VSN")
      )
      (libsource (lib "Database_Libs1") (part "C"))
    )
    (comp (ref "C219")
      (value "C")
      (footprint "SMD_1210_CAPC3225X279N")
      (fields
        (field (name "DB_PART_NUMBER") "CAP000047355")
        (field (name "DB_VALUE") "220uF")
        (field (name "DB_TOLERANCE") "20%")
        (field (name "DB_VOLTAGE") "6.3V")
        (field (name "DB_MANUFACTURER_PART") "SAMSUNG    CL32A227MQVNNNE")
        (field (name "DB_APPROVED_BY") "VSN")
      )
      (libsource (lib "Database_Libs1") (part "C"))
    )
    (comp (ref "C220")
      (value "C")
      (footprint "SMD_1210_CAPC3225X279N")
      (fields
        (field (name "DB_PART_NUMBER") "CAP000047355")
        (field (name "DB_VALUE") "220uF")
        (field (name "DB_TOLERANCE") "20%")
        (field (name "DB_VOLTAGE") "6.3V")
        (field (name "DB_MANUFACTURER_PART") "SAMSUNG    CL32A227MQVNNNE")
        (field (name "DB_APPROVED_BY") "VSN")
      )
      (libsource (lib "Database_Libs1") (part "C"))
    )
    (comp (ref "C221")
      (value "C")
      (footprint "SMD_1210_CAPC3225X279N")
      (fields
        (field (name "DB_PART_NUMBER") "CAP000047355")
        (field (name "DB_VALUE") "220uF")
        (field (name "DB_TOLERANCE") "20%")
        (field (name "DB_VOLTAGE") "6.3V")
        (field (name "DB_MANUFACTURER_PART") "SAMSUNG    CL32A227MQVNNNE")
        (field (name "DB_APPROVED_BY") "VSN")
      )
      (libsource (lib "Database_Libs1") (part "C"))
    )
    (comp (ref "C222")
      (value "C")
      (footprint "SMD_1210_CAPC3225X279N")
      (fields
        (field (name "DB_PART_NUMBER") "CAP000047355")
        (field (name "DB_VALUE") "220uF")
        (field (name "DB_TOLERANCE") "20%")
        (field (name "DB_VOLTAGE") "6.3V")
        (field (name "DB_MANUFACTURER_PART") "SAMSUNG    CL32A227MQVNNNE")
        (field (name "DB_APPROVED_BY") "VSN")
      )
      (libsource (lib "Database_Libs1") (part "C"))
    )
    (comp (ref "C223")
      (value "C")
      (footprint "SMD_1210_CAPC3225X279N")
      (fields
        (field (name "DB_PART_NUMBER") "CAP000047355")
        (field (name "DB_VALUE") "220uF")
        (field (name "DB_TOLERANCE") "20%")
        (field (name "DB_VOLTAGE") "6.3V")
        (field (name "DB_MANUFACTURER_PART") "SAMSUNG    CL32A227MQVNNNE")
        (field (name "DB_APPROVED_BY") "VSN")
      )
      (libsource (lib "Database_Libs1") (part "C"))
    )
    (comp (ref "C224")
      (value "C")
      (footprint "SMD_1210_CAPC3225X279N")
      (fields
        (field (name "DB_PART_NUMBER") "CAP000047355")
        (field (name "DB_VALUE") "220uF")
        (field (name "DB_TOLERANCE") "20%")
        (field (name "DB_VOLTAGE") "6.3V")
        (field (name "DB_MANUFACTURER_PART") "SAMSUNG    CL32A227MQVNNNE")
        (field (name "DB_APPROVED_BY") "VSN")
      )
      (libsource (lib "Database_Libs1") (part "C"))
    )
    (comp (ref "C225")
      (value "C")
      (footprint "SMD_1210_CAPC3225X279N")
      (fields
        (field (name "DB_PART_NUMBER") "CAP000047355")
        (field (name "DB_VALUE") "220uF")
        (field (name "DB_TOLERANCE") "20%")
        (field (name "DB_VOLTAGE") "6.3V")
        (field (name "DB_MANUFACTURER_PART") "SAMSUNG    CL32A227MQVNNNE")
        (field (name "DB_APPROVED_BY") "VSN")
      )
      (libsource (lib "Database_Libs1") (part "C"))
    )
    (comp (ref "C226")
      (value "C")
      (footprint "SMD_1210_CAPC3225X279N")
      (fields
        (field (name "DB_PART_NUMBER") "CAP000047355")
        (field (name "DB_VALUE") "220uF")
        (field (name "DB_TOLERANCE") "20%")
        (field (name "DB_VOLTAGE") "6.3V")
        (field (name "DB_MANUFACTURER_PART") "SAMSUNG    CL32A227MQVNNNE")
        (field (name "DB_APPROVED_BY") "VSN")
      )
      (libsource (lib "Database_Libs1") (part "C"))
    )
    (comp (ref "U1")
      (value "IC_RockerBox")
      (footprint "SMD_BGA480C80P22X22")
      (libsource (lib "RockerBox") (part "IC_RockerBox"))
    )
    (comp (ref "U2")
      (value "IC_RockerBox")
      (footprint "SMD_BGA480C80P22X22")
      (libsource (lib "RockerBox") (part "IC_RockerBox"))
    )
    (comp (ref "U3")
      (value "IC_RockerBox")
      (footprint "SMD_BGA480C80P22X22")
      (libsource (lib "RockerBox") (part "IC_RockerBox"))
    )
    (comp (ref "U4")
      (value "IC_RockerBox")
      (footprint "SMD_BGA480C80P22X22")
      (libsource (lib "RockerBox") (part "IC_RockerBox"))
    )
  )
  (nets
    (net (code "1") (name "/1V") (class "Default")
      (node (ref "C148") (pin "2") (pinfunction "2_2") (pintype "passive"))
      (node (ref "C149") (pin "2") (pinfunction "2_2") (pintype "passive"))
      (node (ref "C150") (pin "2") (pinfunction "2_2") (pintype "passive"))
      (node (ref "C151") (pin "2") (pinfunction "2_2") (pintype "passive"))
      (node (ref "C152") (pin "2") (pinfunction "2_2") (pintype "passive"))
      (node (ref "C153") (pin "2") (pinfunction "2_2") (pintype "passive"))
      (node (ref "C154") (pin "2") (pinfunction "2_2") (pintype "passive"))
      (node (ref "C155") (pin "2") (pinfunction "2_2") (pintype "passive"))
      (node (ref "C156") (pin "2") (pinfunction "2_2") (pintype "passive"))
      (node (ref "C157") (pin "2") (pinfunction "2_2") (pintype "passive"))
      (node (ref "C158") (pin "2") (pinfunction "2_2") (pintype "passive"))
      (node (ref "C159") (pin "2") (pinfunction "2_2") (pintype "passive"))
      (node (ref "C160") (pin "2") (pinfunction "2_2") (pintype "passive"))
      (node (ref "C161") (pin "2") (pinfunction "2_2") (pintype "passive"))
      (node (ref "C162") (pin "2") (pinfunction "2_2") (pintype "passive"))
      (node (ref "C163") (pin "2") (pinfunction "2_2") (pintype "passive"))
      (node (ref "C164") (pin "2") (pinfunction "2_2") (pintype "passive"))
      (node (ref "C165") (pin "2") (pinfunction "2_2") (pintype "passive"))
      (node (ref "C166") (pin "2") (pinfunction "2_2") (pintype "passive"))
      (node (ref "C167") (pin "2") (pinfunction "2_2") (pintype "passive"))
      (node (ref "C169") (pin "2") (pinfunction "2_2") (pintype "passive"))
      (node (ref "C170") (pin "2") (pinfunction "2_2") (pintype "passive"))
      (node (ref "C171") (pin "2") (pinfunction "2_2") (pintype "passive"))
      (node (ref "C172") (pin "2") (pinfunction "2_2") (pintype "passive"))
      (node (ref "C173") (pin "2") (pinfunction "2_2") (pintype "passive"))
      (node (ref "C174") (pin "2") (pinfunction "2_2") (pintype "passive"))
      (node (ref "C175") (pin "2") (pinfunction "2_2") (pintype "passive"))
      (node (ref "C176") (pin "2") (pinfunction "2_2") (pintype "passive"))
      (node (ref "C177") (pin "2") (pinfunction "2_2") (pintype "passive"))
      (node (ref "C178") (pin "2") (pinfunction "2_2") (pintype "passive"))
      (node (ref "C179") (pin "2") (pinfunction "2_2") (pintype "passive"))
      (node (ref "C180") (pin "2") (pinfunction "2_2") (pintype "passive"))
      (node (ref "C181") (pin "2") (pinfunction "2_2") (pintype "passive"))
      (node (ref "C182") (pin "2") (pinfunction "2_2") (pintype "passive"))
      (node (ref "C183") (pin "2") (pinfunction "2_2") (pintype "passive"))
      (node (ref "C184") (pin "2") (pinfunction "2_2") (pintype "passive"))
      (node (ref "C185") (pin "2") (pinfunction "2_2") (pintype "passive"))
      (node (ref "C186") (pin "2") (pinfunction "2_2") (pintype "passive"))
      (node (ref "C187") (pin "2") (pinfunction "2_2") (pintype "passive"))
      (node (ref "C188") (pin "2") (pinfunction "2_2") (pintype "passive"))
      (node (ref "C189") (pin "2") (pinfunction "2_2") (pintype "passive"))
      (node (ref "C19") (pin "2") (pinfunction "2_2") (pintype "passive"))
      (node (ref "C190") (pin "2") (pinfunction "2_2") (pintype "passive"))
      (node (ref "C191") (pin "2") (pinfunction "2_2") (pintype "passive"))
      (node (ref "C192") (pin "2") (pinfunction "2_2") (pintype "passive"))
      (node (ref "C193") (pin "2") (pinfunction "2_2") (pintype "passive"))
      (node (ref "C194") (pin "2") (pinfunction "2_2") (pintype "passive"))
      (node (ref "C195") (pin "2") (pinfunction "2_2") (pintype "passive"))
      (node (ref "C196") (pin "2") (pinfunction "2_2") (pintype "passive"))
      (node (ref "C197") (pin "2") (pinfunction "2_2") (pintype "passive"))
      (node (ref "C198") (pin "2") (pinfunction "2_2") (pintype "passive"))
      (node (ref "C199") (pin "2") (pinfunction "2_2") (pintype "passive"))
      (node (ref "C200") (pin "2") (pinfunction "2_2") (pintype "passive"))
      (node (ref "C201") (pin "2") (pinfunction "2_2") (pintype "passive"))
      (node (ref "C202") (pin "2") (pinfunction "2_2") (pintype "passive"))
      (node (ref "C203") (pin "2") (pinfunction "2_2") (pintype "passive"))
      (node (ref "C204") (pin "2") (pinfunction "2_2") (pintype "passive"))
      (node (ref "C205") (pin "2") (pinfunction "2_2") (pintype "passive"))
      (node (ref "C206") (pin "2") (pinfunction "2_2") (pintype "passive"))
      (node (ref "C207") (pin "2") (pinfunction "2_2") (pintype "passive"))
      (node (ref "C208") (pin "2") (pinfunction "2_2") (pintype "passive"))
      (node (ref "C209") (pin "2") (pinfunction "2_2") (pintype "passive"))
      (node (ref "C210") (pin "2") (pinfunction "2_2") (pintype "passive"))
      (node (ref "C211") (pin "2") (pinfunction "2_2") (pintype "passive"))
      (node (ref "C212") (pin "2") (pinfunction "2_2") (pintype "passive"))
      (node (ref "C213") (pin "2") (pinfunction "2_2") (pintype "passive"))
      (node (ref "C214") (pin "2") (pinfunction "2_2") (pintype "passive"))
      (node (ref "C215") (pin "2") (pinfunction "2_2") (pintype "passive"))
      (node (ref "C216") (pin "2") (pinfunction "2_2") (pintype "passive"))
      (node (ref "C217") (pin "2") (pinfunction "2_2") (pintype "passive"))
      (node (ref "C218") (pin "2") (pinfunction "2_2") (pintype "passive"))
      (node (ref "C219") (pin "2") (pinfunction "2_2") (pintype "passive"))
      (node (ref "C220") (pin "2") (pinfunction "2_2") (pintype "passive"))
      (node (ref "C221") (pin "2") (pinfunction "2_2") (pintype "passive"))
      (node (ref "C222") (pin "2") (pinfunction "2_2") (pintype "passive"))
      (node (ref "C223") (pin "2") (pinfunction "2_2") (pintype "passive"))
      (node (ref "C224") (pin "2") (pinfunction "2_2") (pintype "passive"))
      (node (ref "C225") (pin "2") (pinfunction "2_2") (pintype "passive"))
      (node (ref "C226") (pin "2") (pinfunction "2_2") (pintype "passive"))
      (node (ref "C36") (pin "2") (pinfunction "2_2") (pintype "passive"))
      (node (ref "U1") (pin "A11") (pinfunction "VDD_A11") (pintype "passive"))
      (node (ref "U1") (pin "A13") (pinfunction "VDD_A13") (pintype "passive"))
      (node (ref "U1") (pin "A15") (pinfunction "VDD_A15") (pintype "passive"))
      (node (ref "U1") (pin "A17") (pinfunction "VDD_A17") (pintype "passive"))
      (node (ref "U1") (pin "A19") (pinfunction "VDD_A19") (pintype "passive"))
      (node (ref "U1") (pin "A3") (pinfunction "VDD_A3") (pintype "passive"))
      (node (ref "U1") (pin "A5") (pinfunction "VDD_A5") (pintype "passive"))
      (node (ref "U1") (pin "A7") (pinfunction "VDD_A7") (pintype "passive"))
      (node (ref "U1") (pin "A9") (pinfunction "VDD_A9") (pintype "passive"))
      (node (ref "U1") (pin "AA1") (pinfunction "VDD_AA1") (pintype "passive"))
      (node (ref "U1") (pin "AA11") (pinfunction "VDD_AA11") (pintype "passive"))
      (node (ref "U1") (pin "AA13") (pinfunction "VDD_AA13") (pintype "passive"))
      (node (ref "U1") (pin "AA15") (pinfunction "VDD_AA15") (pintype "passive"))
      (node (ref "U1") (pin "AA17") (pinfunction "VDD_AA17") (pintype "passive"))
      (node (ref "U1") (pin "AA3") (pinfunction "VDD_AA3") (pintype "passive"))
      (node (ref "U1") (pin "AA5") (pinfunction "VDD_AA5") (pintype "passive"))
      (node (ref "U1") (pin "AA7") (pinfunction "VDD_AA7") (pintype "passive"))
      (node (ref "U1") (pin "AA9") (pinfunction "VDD_AA9") (pintype "passive"))
      (node (ref "U1") (pin "AB10") (pinfunction "VDD_AB10") (pintype "passive"))
      (node (ref "U1") (pin "AB12") (pinfunction "VDD_AB12") (pintype "passive"))
      (node (ref "U1") (pin "AB14") (pinfunction "VDD_AB14") (pintype "passive"))
      (node (ref "U1") (pin "AB16") (pinfunction "VDD_AB16") (pintype "passive"))
      (node (ref "U1") (pin "AB18") (pinfunction "VDD_AB18") (pintype "passive"))
      (node (ref "U1") (pin "AB2") (pinfunction "VDD_AB2") (pintype "passive"))
      (node (ref "U1") (pin "AB4") (pinfunction "VDD_AB4") (pintype "passive"))
      (node (ref "U1") (pin "AB6") (pinfunction "VDD_AB6") (pintype "passive"))
      (node (ref "U1") (pin "AB8") (pinfunction "VDD_AB8") (pintype "passive"))
      (node (ref "U1") (pin "B10") (pinfunction "VDD_B10") (pintype "passive"))
      (node (ref "U1") (pin "B12") (pinfunction "VDD_B12") (pintype "passive"))
      (node (ref "U1") (pin "B14") (pinfunction "VDD_B14") (pintype "passive"))
      (node (ref "U1") (pin "B16") (pinfunction "VDD_B16") (pintype "passive"))
      (node (ref "U1") (pin "B18") (pinfunction "VDD_B18") (pintype "passive"))
      (node (ref "U1") (pin "B2") (pinfunction "VDD_B2") (pintype "passive"))
      (node (ref "U1") (pin "B20") (pinfunction "VDD_B20") (pintype "passive"))
      (node (ref "U1") (pin "B4") (pinfunction "VDD_B4") (pintype "passive"))
      (node (ref "U1") (pin "B6") (pinfunction "VDD_B6") (pintype "passive"))
      (node (ref "U1") (pin "B8") (pinfunction "VDD_B8") (pintype "passive"))
      (node (ref "U1") (pin "C1") (pinfunction "VDD_C1") (pintype "passive"))
      (node (ref "U1") (pin "C11") (pinfunction "VDD_C11") (pintype "passive"))
      (node (ref "U1") (pin "C13") (pinfunction "VDD_C13") (pintype "passive"))
      (node (ref "U1") (pin "C15") (pinfunction "VDD_C15") (pintype "passive"))
      (node (ref "U1") (pin "C17") (pinfunction "VDD_C17") (pintype "passive"))
      (node (ref "U1") (pin "C19") (pinfunction "VDD_C19") (pintype "passive"))
      (node (ref "U1") (pin "C3") (pinfunction "VDD_C3") (pintype "passive"))
      (node (ref "U1") (pin "C5") (pinfunction "VDD_C5") (pintype "passive"))
      (node (ref "U1") (pin "C7") (pinfunction "VDD_C7") (pintype "passive"))
      (node (ref "U1") (pin "C9") (pinfunction "VDD_C9") (pintype "passive"))
      (node (ref "U1") (pin "D10") (pinfunction "VDD_D10") (pintype "passive"))
      (node (ref "U1") (pin "D12") (pinfunction "VDD_D12") (pintype "passive"))
      (node (ref "U1") (pin "D14") (pinfunction "VDD_D14") (pintype "passive"))
      (node (ref "U1") (pin "D16") (pinfunction "VDD_D16") (pintype "passive"))
      (node (ref "U1") (pin "D18") (pinfunction "VDD_D18") (pintype "passive"))
      (node (ref "U1") (pin "D2") (pinfunction "VDD_D2") (pintype "passive"))
      (node (ref "U1") (pin "D20") (pinfunction "VDD_D20") (pintype "passive"))
      (node (ref "U1") (pin "D4") (pinfunction "VDD_D4") (pintype "passive"))
      (node (ref "U1") (pin "D6") (pinfunction "VDD_D6") (pintype "passive"))
      (node (ref "U1") (pin "D8") (pinfunction "VDD_D8") (pintype "passive"))
      (node (ref "U1") (pin "E1") (pinfunction "VDD_E1") (pintype "passive"))
      (node (ref "U1") (pin "E11") (pinfunction "VDD_E11") (pintype "passive"))
      (node (ref "U1") (pin "E13") (pinfunction "VDD_E13") (pintype "passive"))
      (node (ref "U1") (pin "E15") (pinfunction "VDD_E15") (pintype "passive"))
      (node (ref "U1") (pin "E17") (pinfunction "VDD_E17") (pintype "passive"))
      (node (ref "U1") (pin "E19") (pinfunction "VDD_E19") (pintype "passive"))
      (node (ref "U1") (pin "E21") (pinfunction "VDD_E21") (pintype "passive"))
      (node (ref "U1") (pin "E3") (pinfunction "VDD_E3") (pintype "passive"))
      (node (ref "U1") (pin "E5") (pinfunction "VDD_E5") (pintype "passive"))
      (node (ref "U1") (pin "E7") (pinfunction "VDD_E7") (pintype "passive"))
      (node (ref "U1") (pin "E9") (pinfunction "VDD_E9") (pintype "passive"))
      (node (ref "U1") (pin "F10") (pinfunction "VDD_F10") (pintype "passive"))
      (node (ref "U1") (pin "F12") (pinfunction "VDD_F12") (pintype "passive"))
      (node (ref "U1") (pin "F14") (pinfunction "VDD_F14") (pintype "passive"))
      (node (ref "U1") (pin "F16") (pinfunction "VDD_F16") (pintype "passive"))
      (node (ref "U1") (pin "F18") (pinfunction "VDD_F18") (pintype "passive"))
      (node (ref "U1") (pin "F2") (pinfunction "VDD_F2") (pintype "passive"))
      (node (ref "U1") (pin "F20") (pinfunction "VDD_F20") (pintype "passive"))
      (node (ref "U1") (pin "F4") (pinfunction "VDD_F4") (pintype "passive"))
      (node (ref "U1") (pin "F6") (pinfunction "VDD_F6") (pintype "passive"))
      (node (ref "U1") (pin "F8") (pinfunction "VDD_F8") (pintype "passive"))
      (node (ref "U1") (pin "G1") (pinfunction "VDD_G1") (pintype "passive"))
      (node (ref "U1") (pin "G11") (pinfunction "VDD_G11") (pintype "passive"))
      (node (ref "U1") (pin "G13") (pinfunction "VDD_G13") (pintype "passive"))
      (node (ref "U1") (pin "G15") (pinfunction "VDD_G15") (pintype "passive"))
      (node (ref "U1") (pin "G17") (pinfunction "VDD_G17") (pintype "passive"))
      (node (ref "U1") (pin "G19") (pinfunction "VDD_G19") (pintype "passive"))
      (node (ref "U1") (pin "G21") (pinfunction "VDD_G21") (pintype "passive"))
      (node (ref "U1") (pin "G3") (pinfunction "VDD_G3") (pintype "passive"))
      (node (ref "U1") (pin "G5") (pinfunction "VDD_G5") (pintype "passive"))
      (node (ref "U1") (pin "G7") (pinfunction "VDD_G7") (pintype "passive"))
      (node (ref "U1") (pin "G9") (pinfunction "VDD_G9") (pintype "passive"))
      (node (ref "U1") (pin "H10") (pinfunction "VDD_H10") (pintype "passive"))
      (node (ref "U1") (pin "H12") (pinfunction "VDD_H12") (pintype "passive"))
      (node (ref "U1") (pin "H14") (pinfunction "VDD_H14") (pintype "passive"))
      (node (ref "U1") (pin "H16") (pinfunction "VDD_H16") (pintype "passive"))
      (node (ref "U1") (pin "H18") (pinfunction "VDD_H18") (pintype "passive"))
      (node (ref "U1") (pin "H2") (pinfunction "VDD_H2") (pintype "passive"))
      (node (ref "U1") (pin "H20") (pinfunction "VDD_H20") (pintype "passive"))
      (node (ref "U1") (pin "H4") (pinfunction "VDD_H4") (pintype "passive"))
      (node (ref "U1") (pin "H6") (pinfunction "VDD_H6") (pintype "passive"))
      (node (ref "U1") (pin "H8") (pinfunction "VDD_H8") (pintype "passive"))
      (node (ref "U1") (pin "J1") (pinfunction "VDD_J1") (pintype "passive"))
      (node (ref "U1") (pin "J11") (pinfunction "VDD_J11") (pintype "passive"))
      (node (ref "U1") (pin "J13") (pinfunction "VDD_J13") (pintype "passive"))
      (node (ref "U1") (pin "J15") (pinfunction "VDD_J15") (pintype "passive"))
      (node (ref "U1") (pin "J17") (pinfunction "VDD_J17") (pintype "passive"))
      (node (ref "U1") (pin "J19") (pinfunction "VDD_J19") (pintype "passive"))
      (node (ref "U1") (pin "J21") (pinfunction "VDD_J21") (pintype "passive"))
      (node (ref "U1") (pin "J3") (pinfunction "VDD_J3") (pintype "passive"))
      (node (ref "U1") (pin "J5") (pinfunction "VDD_J5") (pintype "passive"))
      (node (ref "U1") (pin "J7") (pinfunction "VDD_J7") (pintype "passive"))
      (node (ref "U1") (pin "J9") (pinfunction "VDD_J9") (pintype "passive"))
      (node (ref "U1") (pin "K10") (pinfunction "VDD_K10") (pintype "passive"))
      (node (ref "U1") (pin "K12") (pinfunction "VDD_K12") (pintype "passive"))
      (node (ref "U1") (pin "K14") (pinfunction "VDD_K14") (pintype "passive"))
      (node (ref "U1") (pin "K16") (pinfunction "VDD_K16") (pintype "passive"))
      (node (ref "U1") (pin "K18") (pinfunction "VDD_K18") (pintype "passive"))
      (node (ref "U1") (pin "K2") (pinfunction "VDD_K2") (pintype "passive"))
      (node (ref "U1") (pin "K20") (pinfunction "VDD_K20") (pintype "passive"))
      (node (ref "U1") (pin "K4") (pinfunction "VDD_K4") (pintype "passive"))
      (node (ref "U1") (pin "K6") (pinfunction "VDD_K6") (pintype "passive"))
      (node (ref "U1") (pin "K8") (pinfunction "VDD_K8") (pintype "passive"))
      (node (ref "U1") (pin "L1") (pinfunction "VDD_L1") (pintype "passive"))
      (node (ref "U1") (pin "L11") (pinfunction "VDD_L11") (pintype "passive"))
      (node (ref "U1") (pin "L13") (pinfunction "VDD_L13") (pintype "passive"))
      (node (ref "U1") (pin "L15") (pinfunction "VDD_L15") (pintype "passive"))
      (node (ref "U1") (pin "L17") (pinfunction "VDD_L17") (pintype "passive"))
      (node (ref "U1") (pin "L19") (pinfunction "VDD_L19") (pintype "passive"))
      (node (ref "U1") (pin "L21") (pinfunction "VDD_L21") (pintype "passive"))
      (node (ref "U1") (pin "L3") (pinfunction "VDD_L3") (pintype "passive"))
      (node (ref "U1") (pin "L5") (pinfunction "VDD_L5") (pintype "passive"))
      (node (ref "U1") (pin "L7") (pinfunction "VDD_L7") (pintype "passive"))
      (node (ref "U1") (pin "L9") (pinfunction "VDD_L9") (pintype "passive"))
      (node (ref "U1") (pin "M10") (pinfunction "VDD_M10") (pintype "passive"))
      (node (ref "U1") (pin "M12") (pinfunction "VDD_M12") (pintype "passive"))
      (node (ref "U1") (pin "M14") (pinfunction "VDD_M14") (pintype "passive"))
      (node (ref "U1") (pin "M16") (pinfunction "VDD_M16") (pintype "passive"))
      (node (ref "U1") (pin "M18") (pinfunction "VDD_M18") (pintype "passive"))
      (node (ref "U1") (pin "M2") (pinfunction "VDD_M2") (pintype "passive"))
      (node (ref "U1") (pin "M4") (pinfunction "VDD_M4") (pintype "passive"))
      (node (ref "U1") (pin "M6") (pinfunction "VDD_M6") (pintype "passive"))
      (node (ref "U1") (pin "M8") (pinfunction "VDD_M8") (pintype "passive"))
      (node (ref "U1") (pin "N1") (pinfunction "VDD_N1") (pintype "passive"))
      (node (ref "U1") (pin "N11") (pinfunction "VDD_N11") (pintype "passive"))
      (node (ref "U1") (pin "N13") (pinfunction "VDD_N13") (pintype "passive"))
      (node (ref "U1") (pin "N15") (pinfunction "VDD_N15") (pintype "passive"))
      (node (ref "U1") (pin "N17") (pinfunction "VDD_N17") (pintype "passive"))
      (node (ref "U1") (pin "N19") (pinfunction "VDD_N19") (pintype "passive"))
      (node (ref "U1") (pin "N21") (pinfunction "VDD_N21") (pintype "passive"))
      (node (ref "U1") (pin "N3") (pinfunction "VDD_N3") (pintype "passive"))
      (node (ref "U1") (pin "N5") (pinfunction "VDD_N5") (pintype "passive"))
      (node (ref "U1") (pin "N7") (pinfunction "VDD_N7") (pintype "passive"))
      (node (ref "U1") (pin "N9") (pinfunction "VDD_N9") (pintype "passive"))
      (node (ref "U1") (pin "P10") (pinfunction "VDD_P10") (pintype "passive"))
      (node (ref "U1") (pin "P12") (pinfunction "VDD_P12") (pintype "passive"))
      (node (ref "U1") (pin "P14") (pinfunction "VDD_P14") (pintype "passive"))
      (node (ref "U1") (pin "P16") (pinfunction "VDD_P16") (pintype "passive"))
      (node (ref "U1") (pin "P18") (pinfunction "VDD_P18") (pintype "passive"))
      (node (ref "U1") (pin "P2") (pinfunction "VDD_P2") (pintype "passive"))
      (node (ref "U1") (pin "P20") (pinfunction "VDD_P20") (pintype "passive"))
      (node (ref "U1") (pin "P4") (pinfunction "VDD_P4") (pintype "passive"))
      (node (ref "U1") (pin "P6") (pinfunction "VDD_P6") (pintype "passive"))
      (node (ref "U1") (pin "P8") (pinfunction "VDD_P8") (pintype "passive"))
      (node (ref "U1") (pin "R1") (pinfunction "VDD_R1") (pintype "passive"))
      (node (ref "U1") (pin "R11") (pinfunction "VDD_R11") (pintype "passive"))
      (node (ref "U1") (pin "R13") (pinfunction "VDD_R13") (pintype "passive"))
      (node (ref "U1") (pin "R15") (pinfunction "VDD_R15") (pintype "passive"))
      (node (ref "U1") (pin "R17") (pinfunction "VDD_R17") (pintype "passive"))
      (node (ref "U1") (pin "R19") (pinfunction "VDD_R19") (pintype "passive"))
      (node (ref "U1") (pin "R21") (pinfunction "VDD_R21") (pintype "passive"))
      (node (ref "U1") (pin "R3") (pinfunction "VDD_R3") (pintype "passive"))
      (node (ref "U1") (pin "R5") (pinfunction "VDD_R5") (pintype "passive"))
      (node (ref "U1") (pin "R7") (pinfunction "VDD_R7") (pintype "passive"))
      (node (ref "U1") (pin "R9") (pinfunction "VDD_R9") (pintype "passive"))
      (node (ref "U1") (pin "T10") (pinfunction "VDD_T10") (pintype "passive"))
      (node (ref "U1") (pin "T12") (pinfunction "VDD_T12") (pintype "passive"))
      (node (ref "U1") (pin "T14") (pinfunction "VDD_T14") (pintype "passive"))
      (node (ref "U1") (pin "T16") (pinfunction "VDD_T16") (pintype "passive"))
      (node (ref "U1") (pin "T18") (pinfunction "VDD_T18") (pintype "passive"))
      (node (ref "U1") (pin "T2") (pinfunction "VDD_T2") (pintype "passive"))
      (node (ref "U1") (pin "T20") (pinfunction "VDD_T20") (pintype "passive"))
      (node (ref "U1") (pin "T4") (pinfunction "VDD_T4") (pintype "passive"))
      (node (ref "U1") (pin "T6") (pinfunction "VDD_T6") (pintype "passive"))
      (node (ref "U1") (pin "T8") (pinfunction "VDD_T8") (pintype "passive"))
      (node (ref "U1") (pin "U1") (pinfunction "VDD_U1") (pintype "passive"))
      (node (ref "U1") (pin "U11") (pinfunction "VDD_U11") (pintype "passive"))
      (node (ref "U1") (pin "U13") (pinfunction "VDD_U13") (pintype "passive"))
      (node (ref "U1") (pin "U15") (pinfunction "VDD_U15") (pintype "passive"))
      (node (ref "U1") (pin "U17") (pinfunction "VDD_U17") (pintype "passive"))
      (node (ref "U1") (pin "U19") (pinfunction "VDD_U19") (pintype "passive"))
      (node (ref "U1") (pin "U21") (pinfunction "VDD_U21") (pintype "passive"))
      (node (ref "U1") (pin "U3") (pinfunction "VDD_U3") (pintype "passive"))
      (node (ref "U1") (pin "U5") (pinfunction "VDD_U5") (pintype "passive"))
      (node (ref "U1") (pin "U7") (pinfunction "VDD_U7") (pintype "passive"))
      (node (ref "U1") (pin "U9") (pinfunction "VDD_U9") (pintype "passive"))
      (node (ref "U1") (pin "V10") (pinfunction "VDD_V10") (pintype "passive"))
      (node (ref "U1") (pin "V12") (pinfunction "VDD_V12") (pintype "passive"))
      (node (ref "U1") (pin "V14") (pinfunction "VDD_V14") (pintype "passive"))
      (node (ref "U1") (pin "V16") (pinfunction "VDD_V16") (pintype "passive"))
      (node (ref "U1") (pin "V18") (pinfunction "VDD_V18") (pintype "passive"))
      (node (ref "U1") (pin "V2") (pinfunction "VDD_V2") (pintype "passive"))
      (node (ref "U1") (pin "V20") (pinfunction "VDD_V20") (pintype "passive"))
      (node (ref "U1") (pin "V4") (pinfunction "VDD_V4") (pintype "passive"))
      (node (ref "U1") (pin "V6") (pinfunction "VDD_V6") (pintype "passive"))
      (node (ref "U1") (pin "V8") (pinfunction "VDD_V8") (pintype "passive"))
      (node (ref "U1") (pin "W1") (pinfunction "VDD_W1") (pintype "passive"))
      (node (ref "U1") (pin "W11") (pinfunction "VDD_W11") (pintype "passive"))
      (node (ref "U1") (pin "W13") (pinfunction "VDD_W13") (pintype "passive"))
      (node (ref "U1") (pin "W15") (pinfunction "VDD_W15") (pintype "passive"))
      (node (ref "U1") (pin "W17") (pinfunction "VDD_W17") (pintype "passive"))
      (node (ref "U1") (pin "W19") (pinfunction "VDD_W19") (pintype "passive"))
      (node (ref "U1") (pin "W21") (pinfunction "VDD_W21") (pintype "passive"))
      (node (ref "U1") (pin "W3") (pinfunction "VDD_W3") (pintype "passive"))
      (node (ref "U1") (pin "W5") (pinfunction "VDD_W5") (pintype "passive"))
      (node (ref "U1") (pin "W7") (pinfunction "VDD_W7") (pintype "passive"))
      (node (ref "U1") (pin "W9") (pinfunction "VDD_W9") (pintype "passive"))
      (node (ref "U1") (pin "Y10") (pinfunction "VDD_Y10") (pintype "passive"))
      (node (ref "U1") (pin "Y12") (pinfunction "VDD_Y12") (pintype "passive"))
      (node (ref "U1") (pin "Y14") (pinfunction "VDD_Y14") (pintype "passive"))
      (node (ref "U1") (pin "Y16") (pinfunction "VDD_Y16") (pintype "passive"))
      (node (ref "U1") (pin "Y18") (pinfunction "VDD_Y18") (pintype "passive"))
      (node (ref "U1") (pin "Y2") (pinfunction "VDD_Y2") (pintype "passive"))
      (node (ref "U1") (pin "Y20") (pinfunction "VDD_Y20") (pintype "passive"))
      (node (ref "U1") (pin "Y4") (pinfunction "VDD_Y4") (pintype "passive"))
      (node (ref "U1") (pin "Y6") (pinfunction "VDD_Y6") (pintype "passive"))
      (node (ref "U1") (pin "Y8") (pinfunction "VDD_Y8") (pintype "passive"))
      (node (ref "U2") (pin "A11") (pinfunction "VDD_A11") (pintype "passive"))
      (node (ref "U2") (pin "A13") (pinfunction "VDD_A13") (pintype "passive"))
      (node (ref "U2") (pin "A15") (pinfunction "VDD_A15") (pintype "passive"))
      (node (ref "U2") (pin "A17") (pinfunction "VDD_A17") (pintype "passive"))
      (node (ref "U2") (pin "A19") (pinfunction "VDD_A19") (pintype "passive"))
      (node (ref "U2") (pin "A3") (pinfunction "VDD_A3") (pintype "passive"))
      (node (ref "U2") (pin "A5") (pinfunction "VDD_A5") (pintype "passive"))
      (node (ref "U2") (pin "A7") (pinfunction "VDD_A7") (pintype "passive"))
      (node (ref "U2") (pin "A9") (pinfunction "VDD_A9") (pintype "passive"))
      (node (ref "U2") (pin "AA1") (pinfunction "VDD_AA1") (pintype "passive"))
      (node (ref "U2") (pin "AA11") (pinfunction "VDD_AA11") (pintype "passive"))
      (node (ref "U2") (pin "AA13") (pinfunction "VDD_AA13") (pintype "passive"))
      (node (ref "U2") (pin "AA15") (pinfunction "VDD_AA15") (pintype "passive"))
      (node (ref "U2") (pin "AA17") (pinfunction "VDD_AA17") (pintype "passive"))
      (node (ref "U2") (pin "AA3") (pinfunction "VDD_AA3") (pintype "passive"))
      (node (ref "U2") (pin "AA5") (pinfunction "VDD_AA5") (pintype "passive"))
      (node (ref "U2") (pin "AA7") (pinfunction "VDD_AA7") (pintype "passive"))
      (node (ref "U2") (pin "AA9") (pinfunction "VDD_AA9") (pintype "passive"))
      (node (ref "U2") (pin "AB10") (pinfunction "VDD_AB10") (pintype "passive"))
      (node (ref "U2") (pin "AB12") (pinfunction "VDD_AB12") (pintype "passive"))
      (node (ref "U2") (pin "AB14") (pinfunction "VDD_AB14") (pintype "passive"))
      (node (ref "U2") (pin "AB16") (pinfunction "VDD_AB16") (pintype "passive"))
      (node (ref "U2") (pin "AB18") (pinfunction "VDD_AB18") (pintype "passive"))
      (node (ref "U2") (pin "AB2") (pinfunction "VDD_AB2") (pintype "passive"))
      (node (ref "U2") (pin "AB4") (pinfunction "VDD_AB4") (pintype "passive"))
      (node (ref "U2") (pin "AB6") (pinfunction "VDD_AB6") (pintype "passive"))
      (node (ref "U2") (pin "AB8") (pinfunction "VDD_AB8") (pintype "passive"))
      (node (ref "U2") (pin "B10") (pinfunction "VDD_B10") (pintype "passive"))
      (node (ref "U2") (pin "B12") (pinfunction "VDD_B12") (pintype "passive"))
      (node (ref "U2") (pin "B14") (pinfunction "VDD_B14") (pintype "passive"))
      (node (ref "U2") (pin "B16") (pinfunction "VDD_B16") (pintype "passive"))
      (node (ref "U2") (pin "B18") (pinfunction "VDD_B18") (pintype "passive"))
      (node (ref "U2") (pin "B2") (pinfunction "VDD_B2") (pintype "passive"))
      (node (ref "U2") (pin "B20") (pinfunction "VDD_B20") (pintype "passive"))
      (node (ref "U2") (pin "B4") (pinfunction "VDD_B4") (pintype "passive"))
      (node (ref "U2") (pin "B6") (pinfunction "VDD_B6") (pintype "passive"))
      (node (ref "U2") (pin "B8") (pinfunction "VDD_B8") (pintype "passive"))
      (node (ref "U2") (pin "C1") (pinfunction "VDD_C1") (pintype "passive"))
      (node (ref "U2") (pin "C11") (pinfunction "VDD_C11") (pintype "passive"))
      (node (ref "U2") (pin "C13") (pinfunction "VDD_C13") (pintype "passive"))
      (node (ref "U2") (pin "C15") (pinfunction "VDD_C15") (pintype "passive"))
      (node (ref "U2") (pin "C17") (pinfunction "VDD_C17") (pintype "passive"))
      (node (ref "U2") (pin "C19") (pinfunction "VDD_C19") (pintype "passive"))
      (node (ref "U2") (pin "C3") (pinfunction "VDD_C3") (pintype "passive"))
      (node (ref "U2") (pin "C5") (pinfunction "VDD_C5") (pintype "passive"))
      (node (ref "U2") (pin "C7") (pinfunction "VDD_C7") (pintype "passive"))
      (node (ref "U2") (pin "C9") (pinfunction "VDD_C9") (pintype "passive"))
      (node (ref "U2") (pin "D10") (pinfunction "VDD_D10") (pintype "passive"))
      (node (ref "U2") (pin "D12") (pinfunction "VDD_D12") (pintype "passive"))
      (node (ref "U2") (pin "D14") (pinfunction "VDD_D14") (pintype "passive"))
      (node (ref "U2") (pin "D16") (pinfunction "VDD_D16") (pintype "passive"))
      (node (ref "U2") (pin "D18") (pinfunction "VDD_D18") (pintype "passive"))
      (node (ref "U2") (pin "D2") (pinfunction "VDD_D2") (pintype "passive"))
      (node (ref "U2") (pin "D20") (pinfunction "VDD_D20") (pintype "passive"))
      (node (ref "U2") (pin "D4") (pinfunction "VDD_D4") (pintype "passive"))
      (node (ref "U2") (pin "D6") (pinfunction "VDD_D6") (pintype "passive"))
      (node (ref "U2") (pin "D8") (pinfunction "VDD_D8") (pintype "passive"))
      (node (ref "U2") (pin "E1") (pinfunction "VDD_E1") (pintype "passive"))
      (node (ref "U2") (pin "E11") (pinfunction "VDD_E11") (pintype "passive"))
      (node (ref "U2") (pin "E13") (pinfunction "VDD_E13") (pintype "passive"))
      (node (ref "U2") (pin "E15") (pinfunction "VDD_E15") (pintype "passive"))
      (node (ref "U2") (pin "E17") (pinfunction "VDD_E17") (pintype "passive"))
      (node (ref "U2") (pin "E19") (pinfunction "VDD_E19") (pintype "passive"))
      (node (ref "U2") (pin "E21") (pinfunction "VDD_E21") (pintype "passive"))
      (node (ref "U2") (pin "E3") (pinfunction "VDD_E3") (pintype "passive"))
      (node (ref "U2") (pin "E5") (pinfunction "VDD_E5") (pintype "passive"))
      (node (ref "U2") (pin "E7") (pinfunction "VDD_E7") (pintype "passive"))
      (node (ref "U2") (pin "E9") (pinfunction "VDD_E9") (pintype "passive"))
      (node (ref "U2") (pin "F10") (pinfunction "VDD_F10") (pintype "passive"))
      (node (ref "U2") (pin "F12") (pinfunction "VDD_F12") (pintype "passive"))
      (node (ref "U2") (pin "F14") (pinfunction "VDD_F14") (pintype "passive"))
      (node (ref "U2") (pin "F16") (pinfunction "VDD_F16") (pintype "passive"))
      (node (ref "U2") (pin "F18") (pinfunction "VDD_F18") (pintype "passive"))
      (node (ref "U2") (pin "F2") (pinfunction "VDD_F2") (pintype "passive"))
      (node (ref "U2") (pin "F20") (pinfunction "VDD_F20") (pintype "passive"))
      (node (ref "U2") (pin "F4") (pinfunction "VDD_F4") (pintype "passive"))
      (node (ref "U2") (pin "F6") (pinfunction "VDD_F6") (pintype "passive"))
      (node (ref "U2") (pin "F8") (pinfunction "VDD_F8") (pintype "passive"))
      (node (ref "U2") (pin "G1") (pinfunction "VDD_G1") (pintype "passive"))
      (node (ref "U2") (pin "G11") (pinfunction "VDD_G11") (pintype "passive"))
      (node (ref "U2") (pin "G13") (pinfunction "VDD_G13") (pintype "passive"))
      (node (ref "U2") (pin "G15") (pinfunction "VDD_G15") (pintype "passive"))
      (node (ref "U2") (pin "G17") (pinfunction "VDD_G17") (pintype "passive"))
      (node (ref "U2") (pin "G19") (pinfunction "VDD_G19") (pintype "passive"))
      (node (ref "U2") (pin "G21") (pinfunction "VDD_G21") (pintype "passive"))
      (node (ref "U2") (pin "G3") (pinfunction "VDD_G3") (pintype "passive"))
      (node (ref "U2") (pin "G5") (pinfunction "VDD_G5") (pintype "passive"))
      (node (ref "U2") (pin "G7") (pinfunction "VDD_G7") (pintype "passive"))
      (node (ref "U2") (pin "G9") (pinfunction "VDD_G9") (pintype "passive"))
      (node (ref "U2") (pin "H10") (pinfunction "VDD_H10") (pintype "passive"))
      (node (ref "U2") (pin "H12") (pinfunction "VDD_H12") (pintype "passive"))
      (node (ref "U2") (pin "H14") (pinfunction "VDD_H14") (pintype "passive"))
      (node (ref "U2") (pin "H16") (pinfunction "VDD_H16") (pintype "passive"))
      (node (ref "U2") (pin "H18") (pinfunction "VDD_H18") (pintype "passive"))
      (node (ref "U2") (pin "H2") (pinfunction "VDD_H2") (pintype "passive"))
      (node (ref "U2") (pin "H20") (pinfunction "VDD_H20") (pintype "passive"))
      (node (ref "U2") (pin "H4") (pinfunction "VDD_H4") (pintype "passive"))
      (node (ref "U2") (pin "H6") (pinfunction "VDD_H6") (pintype "passive"))
      (node (ref "U2") (pin "H8") (pinfunction "VDD_H8") (pintype "passive"))
      (node (ref "U2") (pin "J1") (pinfunction "VDD_J1") (pintype "passive"))
      (node (ref "U2") (pin "J11") (pinfunction "VDD_J11") (pintype "passive"))
      (node (ref "U2") (pin "J13") (pinfunction "VDD_J13") (pintype "passive"))
      (node (ref "U2") (pin "J15") (pinfunction "VDD_J15") (pintype "passive"))
      (node (ref "U2") (pin "J17") (pinfunction "VDD_J17") (pintype "passive"))
      (node (ref "U2") (pin "J19") (pinfunction "VDD_J19") (pintype "passive"))
      (node (ref "U2") (pin "J21") (pinfunction "VDD_J21") (pintype "passive"))
      (node (ref "U2") (pin "J3") (pinfunction "VDD_J3") (pintype "passive"))
      (node (ref "U2") (pin "J5") (pinfunction "VDD_J5") (pintype "passive"))
      (node (ref "U2") (pin "J7") (pinfunction "VDD_J7") (pintype "passive"))
      (node (ref "U2") (pin "J9") (pinfunction "VDD_J9") (pintype "passive"))
      (node (ref "U2") (pin "K10") (pinfunction "VDD_K10") (pintype "passive"))
      (node (ref "U2") (pin "K12") (pinfunction "VDD_K12") (pintype "passive"))
      (node (ref "U2") (pin "K14") (pinfunction "VDD_K14") (pintype "passive"))
      (node (ref "U2") (pin "K16") (pinfunction "VDD_K16") (pintype "passive"))
      (node (ref "U2") (pin "K18") (pinfunction "VDD_K18") (pintype "passive"))
      (node (ref "U2") (pin "K2") (pinfunction "VDD_K2") (pintype "passive"))
      (node (ref "U2") (pin "K20") (pinfunction "VDD_K20") (pintype "passive"))
      (node (ref "U2") (pin "K4") (pinfunction "VDD_K4") (pintype "passive"))
      (node (ref "U2") (pin "K6") (pinfunction "VDD_K6") (pintype "passive"))
      (node (ref "U2") (pin "K8") (pinfunction "VDD_K8") (pintype "passive"))
      (node (ref "U2") (pin "L1") (pinfunction "VDD_L1") (pintype "passive"))
      (node (ref "U2") (pin "L11") (pinfunction "VDD_L11") (pintype "passive"))
      (node (ref "U2") (pin "L13") (pinfunction "VDD_L13") (pintype "passive"))
      (node (ref "U2") (pin "L15") (pinfunction "VDD_L15") (pintype "passive"))
      (node (ref "U2") (pin "L17") (pinfunction "VDD_L17") (pintype "passive"))
      (node (ref "U2") (pin "L19") (pinfunction "VDD_L19") (pintype "passive"))
      (node (ref "U2") (pin "L21") (pinfunction "VDD_L21") (pintype "passive"))
      (node (ref "U2") (pin "L3") (pinfunction "VDD_L3") (pintype "passive"))
      (node (ref "U2") (pin "L5") (pinfunction "VDD_L5") (pintype "passive"))
      (node (ref "U2") (pin "L7") (pinfunction "VDD_L7") (pintype "passive"))
      (node (ref "U2") (pin "L9") (pinfunction "VDD_L9") (pintype "passive"))
      (node (ref "U2") (pin "M10") (pinfunction "VDD_M10") (pintype "passive"))
      (node (ref "U2") (pin "M12") (pinfunction "VDD_M12") (pintype "passive"))
      (node (ref "U2") (pin "M14") (pinfunction "VDD_M14") (pintype "passive"))
      (node (ref "U2") (pin "M16") (pinfunction "VDD_M16") (pintype "passive"))
      (node (ref "U2") (pin "M18") (pinfunction "VDD_M18") (pintype "passive"))
      (node (ref "U2") (pin "M2") (pinfunction "VDD_M2") (pintype "passive"))
      (node (ref "U2") (pin "M4") (pinfunction "VDD_M4") (pintype "passive"))
      (node (ref "U2") (pin "M6") (pinfunction "VDD_M6") (pintype "passive"))
      (node (ref "U2") (pin "M8") (pinfunction "VDD_M8") (pintype "passive"))
      (node (ref "U2") (pin "N1") (pinfunction "VDD_N1") (pintype "passive"))
      (node (ref "U2") (pin "N11") (pinfunction "VDD_N11") (pintype "passive"))
      (node (ref "U2") (pin "N13") (pinfunction "VDD_N13") (pintype "passive"))
      (node (ref "U2") (pin "N15") (pinfunction "VDD_N15") (pintype "passive"))
      (node (ref "U2") (pin "N17") (pinfunction "VDD_N17") (pintype "passive"))
      (node (ref "U2") (pin "N19") (pinfunction "VDD_N19") (pintype "passive"))
      (node (ref "U2") (pin "N21") (pinfunction "VDD_N21") (pintype "passive"))
      (node (ref "U2") (pin "N3") (pinfunction "VDD_N3") (pintype "passive"))
      (node (ref "U2") (pin "N5") (pinfunction "VDD_N5") (pintype "passive"))
      (node (ref "U2") (pin "N7") (pinfunction "VDD_N7") (pintype "passive"))
      (node (ref "U2") (pin "N9") (pinfunction "VDD_N9") (pintype "passive"))
      (node (ref "U2") (pin "P10") (pinfunction "VDD_P10") (pintype "passive"))
      (node (ref "U2") (pin "P12") (pinfunction "VDD_P12") (pintype "passive"))
      (node (ref "U2") (pin "P14") (pinfunction "VDD_P14") (pintype "passive"))
      (node (ref "U2") (pin "P16") (pinfunction "VDD_P16") (pintype "passive"))
      (node (ref "U2") (pin "P18") (pinfunction "VDD_P18") (pintype "passive"))
      (node (ref "U2") (pin "P2") (pinfunction "VDD_P2") (pintype "passive"))
      (node (ref "U2") (pin "P20") (pinfunction "VDD_P20") (pintype "passive"))
      (node (ref "U2") (pin "P4") (pinfunction "VDD_P4") (pintype "passive"))
      (node (ref "U2") (pin "P6") (pinfunction "VDD_P6") (pintype "passive"))
      (node (ref "U2") (pin "P8") (pinfunction "VDD_P8") (pintype "passive"))
      (node (ref "U2") (pin "R1") (pinfunction "VDD_R1") (pintype "passive"))
      (node (ref "U2") (pin "R11") (pinfunction "VDD_R11") (pintype "passive"))
      (node (ref "U2") (pin "R13") (pinfunction "VDD_R13") (pintype "passive"))
      (node (ref "U2") (pin "R15") (pinfunction "VDD_R15") (pintype "passive"))
      (node (ref "U2") (pin "R17") (pinfunction "VDD_R17") (pintype "passive"))
      (node (ref "U2") (pin "R19") (pinfunction "VDD_R19") (pintype "passive"))
      (node (ref "U2") (pin "R21") (pinfunction "VDD_R21") (pintype "passive"))
      (node (ref "U2") (pin "R3") (pinfunction "VDD_R3") (pintype "passive"))
      (node (ref "U2") (pin "R5") (pinfunction "VDD_R5") (pintype "passive"))
      (node (ref "U2") (pin "R7") (pinfunction "VDD_R7") (pintype "passive"))
      (node (ref "U2") (pin "R9") (pinfunction "VDD_R9") (pintype "passive"))
      (node (ref "U2") (pin "T10") (pinfunction "VDD_T10") (pintype "passive"))
      (node (ref "U2") (pin "T12") (pinfunction "VDD_T12") (pintype "passive"))
      (node (ref "U2") (pin "T14") (pinfunction "VDD_T14") (pintype "passive"))
      (node (ref "U2") (pin "T16") (pinfunction "VDD_T16") (pintype "passive"))
      (node (ref "U2") (pin "T18") (pinfunction "VDD_T18") (pintype "passive"))
      (node (ref "U2") (pin "T2") (pinfunction "VDD_T2") (pintype "passive"))
      (node (ref "U2") (pin "T20") (pinfunction "VDD_T20") (pintype "passive"))
      (node (ref "U2") (pin "T4") (pinfunction "VDD_T4") (pintype "passive"))
      (node (ref "U2") (pin "T6") (pinfunction "VDD_T6") (pintype "passive"))
      (node (ref "U2") (pin "T8") (pinfunction "VDD_T8") (pintype "passive"))
      (node (ref "U2") (pin "U1") (pinfunction "VDD_U1") (pintype "passive"))
      (node (ref "U2") (pin "U11") (pinfunction "VDD_U11") (pintype "passive"))
      (node (ref "U2") (pin "U13") (pinfunction "VDD_U13") (pintype "passive"))
      (node (ref "U2") (pin "U15") (pinfunction "VDD_U15") (pintype "passive"))
      (node (ref "U2") (pin "U17") (pinfunction "VDD_U17") (pintype "passive"))
      (node (ref "U2") (pin "U19") (pinfunction "VDD_U19") (pintype "passive"))
      (node (ref "U2") (pin "U21") (pinfunction "VDD_U21") (pintype "passive"))
      (node (ref "U2") (pin "U3") (pinfunction "VDD_U3") (pintype "passive"))
      (node (ref "U2") (pin "U5") (pinfunction "VDD_U5") (pintype "passive"))
      (node (ref "U2") (pin "U7") (pinfunction "VDD_U7") (pintype "passive"))
      (node (ref "U2") (pin "U9") (pinfunction "VDD_U9") (pintype "passive"))
      (node (ref "U2") (pin "V10") (pinfunction "VDD_V10") (pintype "passive"))
      (node (ref "U2") (pin "V12") (pinfunction "VDD_V12") (pintype "passive"))
      (node (ref "U2") (pin "V14") (pinfunction "VDD_V14") (pintype "passive"))
      (node (ref "U2") (pin "V16") (pinfunction "VDD_V16") (pintype "passive"))
      (node (ref "U2") (pin "V18") (pinfunction "VDD_V18") (pintype "passive"))
      (node (ref "U2") (pin "V2") (pinfunction "VDD_V2") (pintype "passive"))
      (node (ref "U2") (pin "V20") (pinfunction "VDD_V20") (pintype "passive"))
      (node (ref "U2") (pin "V4") (pinfunction "VDD_V4") (pintype "passive"))
      (node (ref "U2") (pin "V6") (pinfunction "VDD_V6") (pintype "passive"))
      (node (ref "U2") (pin "V8") (pinfunction "VDD_V8") (pintype "passive"))
      (node (ref "U2") (pin "W1") (pinfunction "VDD_W1") (pintype "passive"))
      (node (ref "U2") (pin "W11") (pinfunction "VDD_W11") (pintype "passive"))
      (node (ref "U2") (pin "W13") (pinfunction "VDD_W13") (pintype "passive"))
      (node (ref "U2") (pin "W15") (pinfunction "VDD_W15") (pintype "passive"))
      (node (ref "U2") (pin "W17") (pinfunction "VDD_W17") (pintype "passive"))
      (node (ref "U2") (pin "W19") (pinfunction "VDD_W19") (pintype "passive"))
      (node (ref "U2") (pin "W21") (pinfunction "VDD_W21") (pintype "passive"))
      (node (ref "U2") (pin "W3") (pinfunction "VDD_W3") (pintype "passive"))
      (node (ref "U2") (pin "W5") (pinfunction "VDD_W5") (pintype "passive"))
      (node (ref "U2") (pin "W7") (pinfunction "VDD_W7") (pintype "passive"))
      (node (ref "U2") (pin "W9") (pinfunction "VDD_W9") (pintype "passive"))
      (node (ref "U2") (pin "Y10") (pinfunction "VDD_Y10") (pintype "passive"))
      (node (ref "U2") (pin "Y12") (pinfunction "VDD_Y12") (pintype "passive"))
      (node (ref "U2") (pin "Y14") (pinfunction "VDD_Y14") (pintype "passive"))
      (node (ref "U2") (pin "Y16") (pinfunction "VDD_Y16") (pintype "passive"))
      (node (ref "U2") (pin "Y18") (pinfunction "VDD_Y18") (pintype "passive"))
      (node (ref "U2") (pin "Y2") (pinfunction "VDD_Y2") (pintype "passive"))
      (node (ref "U2") (pin "Y20") (pinfunction "VDD_Y20") (pintype "passive"))
      (node (ref "U2") (pin "Y4") (pinfunction "VDD_Y4") (pintype "passive"))
      (node (ref "U2") (pin "Y6") (pinfunction "VDD_Y6") (pintype "passive"))
      (node (ref "U2") (pin "Y8") (pinfunction "VDD_Y8") (pintype "passive"))
      (node (ref "U3") (pin "A11") (pinfunction "VDD_A11") (pintype "passive"))
      (node (ref "U3") (pin "A13") (pinfunction "VDD_A13") (pintype "passive"))
      (node (ref "U3") (pin "A15") (pinfunction "VDD_A15") (pintype "passive"))
      (node (ref "U3") (pin "A17") (pinfunction "VDD_A17") (pintype "passive"))
      (node (ref "U3") (pin "A19") (pinfunction "VDD_A19") (pintype "passive"))
      (node (ref "U3") (pin "A3") (pinfunction "VDD_A3") (pintype "passive"))
      (node (ref "U3") (pin "A5") (pinfunction "VDD_A5") (pintype "passive"))
      (node (ref "U3") (pin "A7") (pinfunction "VDD_A7") (pintype "passive"))
      (node (ref "U3") (pin "A9") (pinfunction "VDD_A9") (pintype "passive"))
      (node (ref "U3") (pin "AA1") (pinfunction "VDD_AA1") (pintype "passive"))
      (node (ref "U3") (pin "AA11") (pinfunction "VDD_AA11") (pintype "passive"))
      (node (ref "U3") (pin "AA13") (pinfunction "VDD_AA13") (pintype "passive"))
      (node (ref "U3") (pin "AA15") (pinfunction "VDD_AA15") (pintype "passive"))
      (node (ref "U3") (pin "AA17") (pinfunction "VDD_AA17") (pintype "passive"))
      (node (ref "U3") (pin "AA3") (pinfunction "VDD_AA3") (pintype "passive"))
      (node (ref "U3") (pin "AA5") (pinfunction "VDD_AA5") (pintype "passive"))
      (node (ref "U3") (pin "AA7") (pinfunction "VDD_AA7") (pintype "passive"))
      (node (ref "U3") (pin "AA9") (pinfunction "VDD_AA9") (pintype "passive"))
      (node (ref "U3") (pin "AB10") (pinfunction "VDD_AB10") (pintype "passive"))
      (node (ref "U3") (pin "AB12") (pinfunction "VDD_AB12") (pintype "passive"))
      (node (ref "U3") (pin "AB14") (pinfunction "VDD_AB14") (pintype "passive"))
      (node (ref "U3") (pin "AB16") (pinfunction "VDD_AB16") (pintype "passive"))
      (node (ref "U3") (pin "AB18") (pinfunction "VDD_AB18") (pintype "passive"))
      (node (ref "U3") (pin "AB2") (pinfunction "VDD_AB2") (pintype "passive"))
      (node (ref "U3") (pin "AB4") (pinfunction "VDD_AB4") (pintype "passive"))
      (node (ref "U3") (pin "AB6") (pinfunction "VDD_AB6") (pintype "passive"))
      (node (ref "U3") (pin "AB8") (pinfunction "VDD_AB8") (pintype "passive"))
      (node (ref "U3") (pin "B10") (pinfunction "VDD_B10") (pintype "passive"))
      (node (ref "U3") (pin "B12") (pinfunction "VDD_B12") (pintype "passive"))
      (node (ref "U3") (pin "B14") (pinfunction "VDD_B14") (pintype "passive"))
      (node (ref "U3") (pin "B16") (pinfunction "VDD_B16") (pintype "passive"))
      (node (ref "U3") (pin "B18") (pinfunction "VDD_B18") (pintype "passive"))
      (node (ref "U3") (pin "B2") (pinfunction "VDD_B2") (pintype "passive"))
      (node (ref "U3") (pin "B20") (pinfunction "VDD_B20") (pintype "passive"))
      (node (ref "U3") (pin "B4") (pinfunction "VDD_B4") (pintype "passive"))
      (node (ref "U3") (pin "B6") (pinfunction "VDD_B6") (pintype "passive"))
      (node (ref "U3") (pin "B8") (pinfunction "VDD_B8") (pintype "passive"))
      (node (ref "U3") (pin "C1") (pinfunction "VDD_C1") (pintype "passive"))
      (node (ref "U3") (pin "C11") (pinfunction "VDD_C11") (pintype "passive"))
      (node (ref "U3") (pin "C13") (pinfunction "VDD_C13") (pintype "passive"))
      (node (ref "U3") (pin "C15") (pinfunction "VDD_C15") (pintype "passive"))
      (node (ref "U3") (pin "C17") (pinfunction "VDD_C17") (pintype "passive"))
      (node (ref "U3") (pin "C19") (pinfunction "VDD_C19") (pintype "passive"))
      (node (ref "U3") (pin "C3") (pinfunction "VDD_C3") (pintype "passive"))
      (node (ref "U3") (pin "C5") (pinfunction "VDD_C5") (pintype "passive"))
      (node (ref "U3") (pin "C7") (pinfunction "VDD_C7") (pintype "passive"))
      (node (ref "U3") (pin "C9") (pinfunction "VDD_C9") (pintype "passive"))
      (node (ref "U3") (pin "D10") (pinfunction "VDD_D10") (pintype "passive"))
      (node (ref "U3") (pin "D12") (pinfunction "VDD_D12") (pintype "passive"))
      (node (ref "U3") (pin "D14") (pinfunction "VDD_D14") (pintype "passive"))
      (node (ref "U3") (pin "D16") (pinfunction "VDD_D16") (pintype "passive"))
      (node (ref "U3") (pin "D18") (pinfunction "VDD_D18") (pintype "passive"))
      (node (ref "U3") (pin "D2") (pinfunction "VDD_D2") (pintype "passive"))
      (node (ref "U3") (pin "D20") (pinfunction "VDD_D20") (pintype "passive"))
      (node (ref "U3") (pin "D4") (pinfunction "VDD_D4") (pintype "passive"))
      (node (ref "U3") (pin "D6") (pinfunction "VDD_D6") (pintype "passive"))
      (node (ref "U3") (pin "D8") (pinfunction "VDD_D8") (pintype "passive"))
      (node (ref "U3") (pin "E1") (pinfunction "VDD_E1") (pintype "passive"))
      (node (ref "U3") (pin "E11") (pinfunction "VDD_E11") (pintype "passive"))
      (node (ref "U3") (pin "E13") (pinfunction "VDD_E13") (pintype "passive"))
      (node (ref "U3") (pin "E15") (pinfunction "VDD_E15") (pintype "passive"))
      (node (ref "U3") (pin "E17") (pinfunction "VDD_E17") (pintype "passive"))
      (node (ref "U3") (pin "E19") (pinfunction "VDD_E19") (pintype "passive"))
      (node (ref "U3") (pin "E21") (pinfunction "VDD_E21") (pintype "passive"))
      (node (ref "U3") (pin "E3") (pinfunction "VDD_E3") (pintype "passive"))
      (node (ref "U3") (pin "E5") (pinfunction "VDD_E5") (pintype "passive"))
      (node (ref "U3") (pin "E7") (pinfunction "VDD_E7") (pintype "passive"))
      (node (ref "U3") (pin "E9") (pinfunction "VDD_E9") (pintype "passive"))
      (node (ref "U3") (pin "F10") (pinfunction "VDD_F10") (pintype "passive"))
      (node (ref "U3") (pin "F12") (pinfunction "VDD_F12") (pintype "passive"))
      (node (ref "U3") (pin "F14") (pinfunction "VDD_F14") (pintype "passive"))
      (node (ref "U3") (pin "F16") (pinfunction "VDD_F16") (pintype "passive"))
      (node (ref "U3") (pin "F18") (pinfunction "VDD_F18") (pintype "passive"))
      (node (ref "U3") (pin "F2") (pinfunction "VDD_F2") (pintype "passive"))
      (node (ref "U3") (pin "F20") (pinfunction "VDD_F20") (pintype "passive"))
      (node (ref "U3") (pin "F4") (pinfunction "VDD_F4") (pintype "passive"))
      (node (ref "U3") (pin "F6") (pinfunction "VDD_F6") (pintype "passive"))
      (node (ref "U3") (pin "F8") (pinfunction "VDD_F8") (pintype "passive"))
      (node (ref "U3") (pin "G1") (pinfunction "VDD_G1") (pintype "passive"))
      (node (ref "U3") (pin "G11") (pinfunction "VDD_G11") (pintype "passive"))
      (node (ref "U3") (pin "G13") (pinfunction "VDD_G13") (pintype "passive"))
      (node (ref "U3") (pin "G15") (pinfunction "VDD_G15") (pintype "passive"))
      (node (ref "U3") (pin "G17") (pinfunction "VDD_G17") (pintype "passive"))
      (node (ref "U3") (pin "G19") (pinfunction "VDD_G19") (pintype "passive"))
      (node (ref "U3") (pin "G21") (pinfunction "VDD_G21") (pintype "passive"))
      (node (ref "U3") (pin "G3") (pinfunction "VDD_G3") (pintype "passive"))
      (node (ref "U3") (pin "G5") (pinfunction "VDD_G5") (pintype "passive"))
      (node (ref "U3") (pin "G7") (pinfunction "VDD_G7") (pintype "passive"))
      (node (ref "U3") (pin "G9") (pinfunction "VDD_G9") (pintype "passive"))
      (node (ref "U3") (pin "H10") (pinfunction "VDD_H10") (pintype "passive"))
      (node (ref "U3") (pin "H12") (pinfunction "VDD_H12") (pintype "passive"))
      (node (ref "U3") (pin "H14") (pinfunction "VDD_H14") (pintype "passive"))
      (node (ref "U3") (pin "H16") (pinfunction "VDD_H16") (pintype "passive"))
      (node (ref "U3") (pin "H18") (pinfunction "VDD_H18") (pintype "passive"))
      (node (ref "U3") (pin "H2") (pinfunction "VDD_H2") (pintype "passive"))
      (node (ref "U3") (pin "H20") (pinfunction "VDD_H20") (pintype "passive"))
      (node (ref "U3") (pin "H4") (pinfunction "VDD_H4") (pintype "passive"))
      (node (ref "U3") (pin "H6") (pinfunction "VDD_H6") (pintype "passive"))
      (node (ref "U3") (pin "H8") (pinfunction "VDD_H8") (pintype "passive"))
      (node (ref "U3") (pin "J1") (pinfunction "VDD_J1") (pintype "passive"))
      (node (ref "U3") (pin "J11") (pinfunction "VDD_J11") (pintype "passive"))
      (node (ref "U3") (pin "J13") (pinfunction "VDD_J13") (pintype "passive"))
      (node (ref "U3") (pin "J15") (pinfunction "VDD_J15") (pintype "passive"))
      (node (ref "U3") (pin "J17") (pinfunction "VDD_J17") (pintype "passive"))
      (node (ref "U3") (pin "J19") (pinfunction "VDD_J19") (pintype "passive"))
      (node (ref "U3") (pin "J21") (pinfunction "VDD_J21") (pintype "passive"))
      (node (ref "U3") (pin "J3") (pinfunction "VDD_J3") (pintype "passive"))
      (node (ref "U3") (pin "J5") (pinfunction "VDD_J5") (pintype "passive"))
      (node (ref "U3") (pin "J7") (pinfunction "VDD_J7") (pintype "passive"))
      (node (ref "U3") (pin "J9") (pinfunction "VDD_J9") (pintype "passive"))
      (node (ref "U3") (pin "K10") (pinfunction "VDD_K10") (pintype "passive"))
      (node (ref "U3") (pin "K12") (pinfunction "VDD_K12") (pintype "passive"))
      (node (ref "U3") (pin "K14") (pinfunction "VDD_K14") (pintype "passive"))
      (node (ref "U3") (pin "K16") (pinfunction "VDD_K16") (pintype "passive"))
      (node (ref "U3") (pin "K18") (pinfunction "VDD_K18") (pintype "passive"))
      (node (ref "U3") (pin "K2") (pinfunction "VDD_K2") (pintype "passive"))
      (node (ref "U3") (pin "K20") (pinfunction "VDD_K20") (pintype "passive"))
      (node (ref "U3") (pin "K4") (pinfunction "VDD_K4") (pintype "passive"))
      (node (ref "U3") (pin "K6") (pinfunction "VDD_K6") (pintype "passive"))
      (node (ref "U3") (pin "K8") (pinfunction "VDD_K8") (pintype "passive"))
      (node (ref "U3") (pin "L1") (pinfunction "VDD_L1") (pintype "passive"))
      (node (ref "U3") (pin "L11") (pinfunction "VDD_L11") (pintype "passive"))
      (node (ref "U3") (pin "L13") (pinfunction "VDD_L13") (pintype "passive"))
      (node (ref "U3") (pin "L15") (pinfunction "VDD_L15") (pintype "passive"))
      (node (ref "U3") (pin "L17") (pinfunction "VDD_L17") (pintype "passive"))
      (node (ref "U3") (pin "L19") (pinfunction "VDD_L19") (pintype "passive"))
      (node (ref "U3") (pin "L21") (pinfunction "VDD_L21") (pintype "passive"))
      (node (ref "U3") (pin "L3") (pinfunction "VDD_L3") (pintype "passive"))
      (node (ref "U3") (pin "L5") (pinfunction "VDD_L5") (pintype "passive"))
      (node (ref "U3") (pin "L7") (pinfunction "VDD_L7") (pintype "passive"))
      (node (ref "U3") (pin "L9") (pinfunction "VDD_L9") (pintype "passive"))
      (node (ref "U3") (pin "M10") (pinfunction "VDD_M10") (pintype "passive"))
      (node (ref "U3") (pin "M12") (pinfunction "VDD_M12") (pintype "passive"))
      (node (ref "U3") (pin "M14") (pinfunction "VDD_M14") (pintype "passive"))
      (node (ref "U3") (pin "M16") (pinfunction "VDD_M16") (pintype "passive"))
      (node (ref "U3") (pin "M18") (pinfunction "VDD_M18") (pintype "passive"))
      (node (ref "U3") (pin "M2") (pinfunction "VDD_M2") (pintype "passive"))
      (node (ref "U3") (pin "M4") (pinfunction "VDD_M4") (pintype "passive"))
      (node (ref "U3") (pin "M6") (pinfunction "VDD_M6") (pintype "passive"))
      (node (ref "U3") (pin "M8") (pinfunction "VDD_M8") (pintype "passive"))
      (node (ref "U3") (pin "N1") (pinfunction "VDD_N1") (pintype "passive"))
      (node (ref "U3") (pin "N11") (pinfunction "VDD_N11") (pintype "passive"))
      (node (ref "U3") (pin "N13") (pinfunction "VDD_N13") (pintype "passive"))
      (node (ref "U3") (pin "N15") (pinfunction "VDD_N15") (pintype "passive"))
      (node (ref "U3") (pin "N17") (pinfunction "VDD_N17") (pintype "passive"))
      (node (ref "U3") (pin "N19") (pinfunction "VDD_N19") (pintype "passive"))
      (node (ref "U3") (pin "N21") (pinfunction "VDD_N21") (pintype "passive"))
      (node (ref "U3") (pin "N3") (pinfunction "VDD_N3") (pintype "passive"))
      (node (ref "U3") (pin "N5") (pinfunction "VDD_N5") (pintype "passive"))
      (node (ref "U3") (pin "N7") (pinfunction "VDD_N7") (pintype "passive"))
      (node (ref "U3") (pin "N9") (pinfunction "VDD_N9") (pintype "passive"))
      (node (ref "U3") (pin "P10") (pinfunction "VDD_P10") (pintype "passive"))
      (node (ref "U3") (pin "P12") (pinfunction "VDD_P12") (pintype "passive"))
      (node (ref "U3") (pin "P14") (pinfunction "VDD_P14") (pintype "passive"))
      (node (ref "U3") (pin "P16") (pinfunction "VDD_P16") (pintype "passive"))
      (node (ref "U3") (pin "P18") (pinfunction "VDD_P18") (pintype "passive"))
      (node (ref "U3") (pin "P2") (pinfunction "VDD_P2") (pintype "passive"))
      (node (ref "U3") (pin "P20") (pinfunction "VDD_P20") (pintype "passive"))
      (node (ref "U3") (pin "P4") (pinfunction "VDD_P4") (pintype "passive"))
      (node (ref "U3") (pin "P6") (pinfunction "VDD_P6") (pintype "passive"))
      (node (ref "U3") (pin "P8") (pinfunction "VDD_P8") (pintype "passive"))
      (node (ref "U3") (pin "R1") (pinfunction "VDD_R1") (pintype "passive"))
      (node (ref "U3") (pin "R11") (pinfunction "VDD_R11") (pintype "passive"))
      (node (ref "U3") (pin "R13") (pinfunction "VDD_R13") (pintype "passive"))
      (node (ref "U3") (pin "R15") (pinfunction "VDD_R15") (pintype "passive"))
      (node (ref "U3") (pin "R17") (pinfunction "VDD_R17") (pintype "passive"))
      (node (ref "U3") (pin "R19") (pinfunction "VDD_R19") (pintype "passive"))
      (node (ref "U3") (pin "R21") (pinfunction "VDD_R21") (pintype "passive"))
      (node (ref "U3") (pin "R3") (pinfunction "VDD_R3") (pintype "passive"))
      (node (ref "U3") (pin "R5") (pinfunction "VDD_R5") (pintype "passive"))
      (node (ref "U3") (pin "R7") (pinfunction "VDD_R7") (pintype "passive"))
      (node (ref "U3") (pin "R9") (pinfunction "VDD_R9") (pintype "passive"))
      (node (ref "U3") (pin "T10") (pinfunction "VDD_T10") (pintype "passive"))
      (node (ref "U3") (pin "T12") (pinfunction "VDD_T12") (pintype "passive"))
      (node (ref "U3") (pin "T14") (pinfunction "VDD_T14") (pintype "passive"))
      (node (ref "U3") (pin "T16") (pinfunction "VDD_T16") (pintype "passive"))
      (node (ref "U3") (pin "T18") (pinfunction "VDD_T18") (pintype "passive"))
      (node (ref "U3") (pin "T2") (pinfunction "VDD_T2") (pintype "passive"))
      (node (ref "U3") (pin "T20") (pinfunction "VDD_T20") (pintype "passive"))
      (node (ref "U3") (pin "T4") (pinfunction "VDD_T4") (pintype "passive"))
      (node (ref "U3") (pin "T6") (pinfunction "VDD_T6") (pintype "passive"))
      (node (ref "U3") (pin "T8") (pinfunction "VDD_T8") (pintype "passive"))
      (node (ref "U3") (pin "U1") (pinfunction "VDD_U1") (pintype "passive"))
      (node (ref "U3") (pin "U11") (pinfunction "VDD_U11") (pintype "passive"))
      (node (ref "U3") (pin "U13") (pinfunction "VDD_U13") (pintype "passive"))
      (node (ref "U3") (pin "U15") (pinfunction "VDD_U15") (pintype "passive"))
      (node (ref "U3") (pin "U17") (pinfunction "VDD_U17") (pintype "passive"))
      (node (ref "U3") (pin "U19") (pinfunction "VDD_U19") (pintype "passive"))
      (node (ref "U3") (pin "U21") (pinfunction "VDD_U21") (pintype "passive"))
      (node (ref "U3") (pin "U3") (pinfunction "VDD_U3") (pintype "passive"))
      (node (ref "U3") (pin "U5") (pinfunction "VDD_U5") (pintype "passive"))
      (node (ref "U3") (pin "U7") (pinfunction "VDD_U7") (pintype "passive"))
      (node (ref "U3") (pin "U9") (pinfunction "VDD_U9") (pintype "passive"))
      (node (ref "U3") (pin "V10") (pinfunction "VDD_V10") (pintype "passive"))
      (node (ref "U3") (pin "V12") (pinfunction "VDD_V12") (pintype "passive"))
      (node (ref "U3") (pin "V14") (pinfunction "VDD_V14") (pintype "passive"))
      (node (ref "U3") (pin "V16") (pinfunction "VDD_V16") (pintype "passive"))
      (node (ref "U3") (pin "V18") (pinfunction "VDD_V18") (pintype "passive"))
      (node (ref "U3") (pin "V2") (pinfunction "VDD_V2") (pintype "passive"))
      (node (ref "U3") (pin "V20") (pinfunction "VDD_V20") (pintype "passive"))
      (node (ref "U3") (pin "V4") (pinfunction "VDD_V4") (pintype "passive"))
      (node (ref "U3") (pin "V6") (pinfunction "VDD_V6") (pintype "passive"))
      (node (ref "U3") (pin "V8") (pinfunction "VDD_V8") (pintype "passive"))
      (node (ref "U3") (pin "W1") (pinfunction "VDD_W1") (pintype "passive"))
      (node (ref "U3") (pin "W11") (pinfunction "VDD_W11") (pintype "passive"))
      (node (ref "U3") (pin "W13") (pinfunction "VDD_W13") (pintype "passive"))
      (node (ref "U3") (pin "W15") (pinfunction "VDD_W15") (pintype "passive"))
      (node (ref "U3") (pin "W17") (pinfunction "VDD_W17") (pintype "passive"))
      (node (ref "U3") (pin "W19") (pinfunction "VDD_W19") (pintype "passive"))
      (node (ref "U3") (pin "W21") (pinfunction "VDD_W21") (pintype "passive"))
      (node (ref "U3") (pin "W3") (pinfunction "VDD_W3") (pintype "passive"))
      (node (ref "U3") (pin "W5") (pinfunction "VDD_W5") (pintype "passive"))
      (node (ref "U3") (pin "W7") (pinfunction "VDD_W7") (pintype "passive"))
      (node (ref "U3") (pin "W9") (pinfunction "VDD_W9") (pintype "passive"))
      (node (ref "U3") (pin "Y10") (pinfunction "VDD_Y10") (pintype "passive"))
      (node (ref "U3") (pin "Y12") (pinfunction "VDD_Y12") (pintype "passive"))
      (node (ref "U3") (pin "Y14") (pinfunction "VDD_Y14") (pintype "passive"))
      (node (ref "U3") (pin "Y16") (pinfunction "VDD_Y16") (pintype "passive"))
      (node (ref "U3") (pin "Y18") (pinfunction "VDD_Y18") (pintype "passive"))
      (node (ref "U3") (pin "Y2") (pinfunction "VDD_Y2") (pintype "passive"))
      (node (ref "U3") (pin "Y20") (pinfunction "VDD_Y20") (pintype "passive"))
      (node (ref "U3") (pin "Y4") (pinfunction "VDD_Y4") (pintype "passive"))
      (node (ref "U3") (pin "Y6") (pinfunction "VDD_Y6") (pintype "passive"))
      (node (ref "U3") (pin "Y8") (pinfunction "VDD_Y8") (pintype "passive"))
      (node (ref "U4") (pin "A11") (pinfunction "VDD_A11") (pintype "passive"))
      (node (ref "U4") (pin "A13") (pinfunction "VDD_A13") (pintype "passive"))
      (node (ref "U4") (pin "A15") (pinfunction "VDD_A15") (pintype "passive"))
      (node (ref "U4") (pin "A17") (pinfunction "VDD_A17") (pintype "passive"))
      (node (ref "U4") (pin "A19") (pinfunction "VDD_A19") (pintype "passive"))
      (node (ref "U4") (pin "A3") (pinfunction "VDD_A3") (pintype "passive"))
      (node (ref "U4") (pin "A5") (pinfunction "VDD_A5") (pintype "passive"))
      (node (ref "U4") (pin "A7") (pinfunction "VDD_A7") (pintype "passive"))
      (node (ref "U4") (pin "A9") (pinfunction "VDD_A9") (pintype "passive"))
      (node (ref "U4") (pin "AA1") (pinfunction "VDD_AA1") (pintype "passive"))
      (node (ref "U4") (pin "AA11") (pinfunction "VDD_AA11") (pintype "passive"))
      (node (ref "U4") (pin "AA13") (pinfunction "VDD_AA13") (pintype "passive"))
      (node (ref "U4") (pin "AA15") (pinfunction "VDD_AA15") (pintype "passive"))
      (node (ref "U4") (pin "AA17") (pinfunction "VDD_AA17") (pintype "passive"))
      (node (ref "U4") (pin "AA3") (pinfunction "VDD_AA3") (pintype "passive"))
      (node (ref "U4") (pin "AA5") (pinfunction "VDD_AA5") (pintype "passive"))
      (node (ref "U4") (pin "AA7") (pinfunction "VDD_AA7") (pintype "passive"))
      (node (ref "U4") (pin "AA9") (pinfunction "VDD_AA9") (pintype "passive"))
      (node (ref "U4") (pin "AB10") (pinfunction "VDD_AB10") (pintype "passive"))
      (node (ref "U4") (pin "AB12") (pinfunction "VDD_AB12") (pintype "passive"))
      (node (ref "U4") (pin "AB14") (pinfunction "VDD_AB14") (pintype "passive"))
      (node (ref "U4") (pin "AB16") (pinfunction "VDD_AB16") (pintype "passive"))
      (node (ref "U4") (pin "AB18") (pinfunction "VDD_AB18") (pintype "passive"))
      (node (ref "U4") (pin "AB2") (pinfunction "VDD_AB2") (pintype "passive"))
      (node (ref "U4") (pin "AB4") (pinfunction "VDD_AB4") (pintype "passive"))
      (node (ref "U4") (pin "AB6") (pinfunction "VDD_AB6") (pintype "passive"))
      (node (ref "U4") (pin "AB8") (pinfunction "VDD_AB8") (pintype "passive"))
      (node (ref "U4") (pin "B10") (pinfunction "VDD_B10") (pintype "passive"))
      (node (ref "U4") (pin "B12") (pinfunction "VDD_B12") (pintype "passive"))
      (node (ref "U4") (pin "B14") (pinfunction "VDD_B14") (pintype "passive"))
      (node (ref "U4") (pin "B16") (pinfunction "VDD_B16") (pintype "passive"))
      (node (ref "U4") (pin "B18") (pinfunction "VDD_B18") (pintype "passive"))
      (node (ref "U4") (pin "B2") (pinfunction "VDD_B2") (pintype "passive"))
      (node (ref "U4") (pin "B20") (pinfunction "VDD_B20") (pintype "passive"))
      (node (ref "U4") (pin "B4") (pinfunction "VDD_B4") (pintype "passive"))
      (node (ref "U4") (pin "B6") (pinfunction "VDD_B6") (pintype "passive"))
      (node (ref "U4") (pin "B8") (pinfunction "VDD_B8") (pintype "passive"))
      (node (ref "U4") (pin "C1") (pinfunction "VDD_C1") (pintype "passive"))
      (node (ref "U4") (pin "C11") (pinfunction "VDD_C11") (pintype "passive"))
      (node (ref "U4") (pin "C13") (pinfunction "VDD_C13") (pintype "passive"))
      (node (ref "U4") (pin "C15") (pinfunction "VDD_C15") (pintype "passive"))
      (node (ref "U4") (pin "C17") (pinfunction "VDD_C17") (pintype "passive"))
      (node (ref "U4") (pin "C19") (pinfunction "VDD_C19") (pintype "passive"))
      (node (ref "U4") (pin "C3") (pinfunction "VDD_C3") (pintype "passive"))
      (node (ref "U4") (pin "C5") (pinfunction "VDD_C5") (pintype "passive"))
      (node (ref "U4") (pin "C7") (pinfunction "VDD_C7") (pintype "passive"))
      (node (ref "U4") (pin "C9") (pinfunction "VDD_C9") (pintype "passive"))
      (node (ref "U4") (pin "D10") (pinfunction "VDD_D10") (pintype "passive"))
      (node (ref "U4") (pin "D12") (pinfunction "VDD_D12") (pintype "passive"))
      (node (ref "U4") (pin "D14") (pinfunction "VDD_D14") (pintype "passive"))
      (node (ref "U4") (pin "D16") (pinfunction "VDD_D16") (pintype "passive"))
      (node (ref "U4") (pin "D18") (pinfunction "VDD_D18") (pintype "passive"))
      (node (ref "U4") (pin "D2") (pinfunction "VDD_D2") (pintype "passive"))
      (node (ref "U4") (pin "D20") (pinfunction "VDD_D20") (pintype "passive"))
      (node (ref "U4") (pin "D4") (pinfunction "VDD_D4") (pintype "passive"))
      (node (ref "U4") (pin "D6") (pinfunction "VDD_D6") (pintype "passive"))
      (node (ref "U4") (pin "D8") (pinfunction "VDD_D8") (pintype "passive"))
      (node (ref "U4") (pin "E1") (pinfunction "VDD_E1") (pintype "passive"))
      (node (ref "U4") (pin "E11") (pinfunction "VDD_E11") (pintype "passive"))
      (node (ref "U4") (pin "E13") (pinfunction "VDD_E13") (pintype "passive"))
      (node (ref "U4") (pin "E15") (pinfunction "VDD_E15") (pintype "passive"))
      (node (ref "U4") (pin "E17") (pinfunction "VDD_E17") (pintype "passive"))
      (node (ref "U4") (pin "E19") (pinfunction "VDD_E19") (pintype "passive"))
      (node (ref "U4") (pin "E21") (pinfunction "VDD_E21") (pintype "passive"))
      (node (ref "U4") (pin "E3") (pinfunction "VDD_E3") (pintype "passive"))
      (node (ref "U4") (pin "E5") (pinfunction "VDD_E5") (pintype "passive"))
      (node (ref "U4") (pin "E7") (pinfunction "VDD_E7") (pintype "passive"))
      (node (ref "U4") (pin "E9") (pinfunction "VDD_E9") (pintype "passive"))
      (node (ref "U4") (pin "F10") (pinfunction "VDD_F10") (pintype "passive"))
      (node (ref "U4") (pin "F12") (pinfunction "VDD_F12") (pintype "passive"))
      (node (ref "U4") (pin "F14") (pinfunction "VDD_F14") (pintype "passive"))
      (node (ref "U4") (pin "F16") (pinfunction "VDD_F16") (pintype "passive"))
      (node (ref "U4") (pin "F18") (pinfunction "VDD_F18") (pintype "passive"))
      (node (ref "U4") (pin "F2") (pinfunction "VDD_F2") (pintype "passive"))
      (node (ref "U4") (pin "F20") (pinfunction "VDD_F20") (pintype "passive"))
      (node (ref "U4") (pin "F4") (pinfunction "VDD_F4") (pintype "passive"))
      (node (ref "U4") (pin "F6") (pinfunction "VDD_F6") (pintype "passive"))
      (node (ref "U4") (pin "F8") (pinfunction "VDD_F8") (pintype "passive"))
      (node (ref "U4") (pin "G1") (pinfunction "VDD_G1") (pintype "passive"))
      (node (ref "U4") (pin "G11") (pinfunction "VDD_G11") (pintype "passive"))
      (node (ref "U4") (pin "G13") (pinfunction "VDD_G13") (pintype "passive"))
      (node (ref "U4") (pin "G15") (pinfunction "VDD_G15") (pintype "passive"))
      (node (ref "U4") (pin "G17") (pinfunction "VDD_G17") (pintype "passive"))
      (node (ref "U4") (pin "G19") (pinfunction "VDD_G19") (pintype "passive"))
      (node (ref "U4") (pin "G21") (pinfunction "VDD_G21") (pintype "passive"))
      (node (ref "U4") (pin "G3") (pinfunction "VDD_G3") (pintype "passive"))
      (node (ref "U4") (pin "G5") (pinfunction "VDD_G5") (pintype "passive"))
      (node (ref "U4") (pin "G7") (pinfunction "VDD_G7") (pintype "passive"))
      (node (ref "U4") (pin "G9") (pinfunction "VDD_G9") (pintype "passive"))
      (node (ref "U4") (pin "H10") (pinfunction "VDD_H10") (pintype "passive"))
      (node (ref "U4") (pin "H12") (pinfunction "VDD_H12") (pintype "passive"))
      (node (ref "U4") (pin "H14") (pinfunction "VDD_H14") (pintype "passive"))
      (node (ref "U4") (pin "H16") (pinfunction "VDD_H16") (pintype "passive"))
      (node (ref "U4") (pin "H18") (pinfunction "VDD_H18") (pintype "passive"))
      (node (ref "U4") (pin "H2") (pinfunction "VDD_H2") (pintype "passive"))
      (node (ref "U4") (pin "H20") (pinfunction "VDD_H20") (pintype "passive"))
      (node (ref "U4") (pin "H4") (pinfunction "VDD_H4") (pintype "passive"))
      (node (ref "U4") (pin "H6") (pinfunction "VDD_H6") (pintype "passive"))
      (node (ref "U4") (pin "H8") (pinfunction "VDD_H8") (pintype "passive"))
      (node (ref "U4") (pin "J1") (pinfunction "VDD_J1") (pintype "passive"))
      (node (ref "U4") (pin "J11") (pinfunction "VDD_J11") (pintype "passive"))
      (node (ref "U4") (pin "J13") (pinfunction "VDD_J13") (pintype "passive"))
      (node (ref "U4") (pin "J15") (pinfunction "VDD_J15") (pintype "passive"))
      (node (ref "U4") (pin "J17") (pinfunction "VDD_J17") (pintype "passive"))
      (node (ref "U4") (pin "J19") (pinfunction "VDD_J19") (pintype "passive"))
      (node (ref "U4") (pin "J21") (pinfunction "VDD_J21") (pintype "passive"))
      (node (ref "U4") (pin "J3") (pinfunction "VDD_J3") (pintype "passive"))
      (node (ref "U4") (pin "J5") (pinfunction "VDD_J5") (pintype "passive"))
      (node (ref "U4") (pin "J7") (pinfunction "VDD_J7") (pintype "passive"))
      (node (ref "U4") (pin "J9") (pinfunction "VDD_J9") (pintype "passive"))
      (node (ref "U4") (pin "K10") (pinfunction "VDD_K10") (pintype "passive"))
      (node (ref "U4") (pin "K12") (pinfunction "VDD_K12") (pintype "passive"))
      (node (ref "U4") (pin "K14") (pinfunction "VDD_K14") (pintype "passive"))
      (node (ref "U4") (pin "K16") (pinfunction "VDD_K16") (pintype "passive"))
      (node (ref "U4") (pin "K18") (pinfunction "VDD_K18") (pintype "passive"))
      (node (ref "U4") (pin "K2") (pinfunction "VDD_K2") (pintype "passive"))
      (node (ref "U4") (pin "K20") (pinfunction "VDD_K20") (pintype "passive"))
      (node (ref "U4") (pin "K4") (pinfunction "VDD_K4") (pintype "passive"))
      (node (ref "U4") (pin "K6") (pinfunction "VDD_K6") (pintype "passive"))
      (node (ref "U4") (pin "K8") (pinfunction "VDD_K8") (pintype "passive"))
      (node (ref "U4") (pin "L1") (pinfunction "VDD_L1") (pintype "passive"))
      (node (ref "U4") (pin "L11") (pinfunction "VDD_L11") (pintype "passive"))
      (node (ref "U4") (pin "L13") (pinfunction "VDD_L13") (pintype "passive"))
      (node (ref "U4") (pin "L15") (pinfunction "VDD_L15") (pintype "passive"))
      (node (ref "U4") (pin "L17") (pinfunction "VDD_L17") (pintype "passive"))
      (node (ref "U4") (pin "L19") (pinfunction "VDD_L19") (pintype "passive"))
      (node (ref "U4") (pin "L21") (pinfunction "VDD_L21") (pintype "passive"))
      (node (ref "U4") (pin "L3") (pinfunction "VDD_L3") (pintype "passive"))
      (node (ref "U4") (pin "L5") (pinfunction "VDD_L5") (pintype "passive"))
      (node (ref "U4") (pin "L7") (pinfunction "VDD_L7") (pintype "passive"))
      (node (ref "U4") (pin "L9") (pinfunction "VDD_L9") (pintype "passive"))
      (node (ref "U4") (pin "M10") (pinfunction "VDD_M10") (pintype "passive"))
      (node (ref "U4") (pin "M12") (pinfunction "VDD_M12") (pintype "passive"))
      (node (ref "U4") (pin "M14") (pinfunction "VDD_M14") (pintype "passive"))
      (node (ref "U4") (pin "M16") (pinfunction "VDD_M16") (pintype "passive"))
      (node (ref "U4") (pin "M18") (pinfunction "VDD_M18") (pintype "passive"))
      (node (ref "U4") (pin "M2") (pinfunction "VDD_M2") (pintype "passive"))
      (node (ref "U4") (pin "M4") (pinfunction "VDD_M4") (pintype "passive"))
      (node (ref "U4") (pin "M6") (pinfunction "VDD_M6") (pintype "passive"))
      (node (ref "U4") (pin "M8") (pinfunction "VDD_M8") (pintype "passive"))
      (node (ref "U4") (pin "N1") (pinfunction "VDD_N1") (pintype "passive"))
      (node (ref "U4") (pin "N11") (pinfunction "VDD_N11") (pintype "passive"))
      (node (ref "U4") (pin "N13") (pinfunction "VDD_N13") (pintype "passive"))
      (node (ref "U4") (pin "N15") (pinfunction "VDD_N15") (pintype "passive"))
      (node (ref "U4") (pin "N17") (pinfunction "VDD_N17") (pintype "passive"))
      (node (ref "U4") (pin "N19") (pinfunction "VDD_N19") (pintype "passive"))
      (node (ref "U4") (pin "N21") (pinfunction "VDD_N21") (pintype "passive"))
      (node (ref "U4") (pin "N3") (pinfunction "VDD_N3") (pintype "passive"))
      (node (ref "U4") (pin "N5") (pinfunction "VDD_N5") (pintype "passive"))
      (node (ref "U4") (pin "N7") (pinfunction "VDD_N7") (pintype "passive"))
      (node (ref "U4") (pin "N9") (pinfunction "VDD_N9") (pintype "passive"))
      (node (ref "U4") (pin "P10") (pinfunction "VDD_P10") (pintype "passive"))
      (node (ref "U4") (pin "P12") (pinfunction "VDD_P12") (pintype "passive"))
      (node (ref "U4") (pin "P14") (pinfunction "VDD_P14") (pintype "passive"))
      (node (ref "U4") (pin "P16") (pinfunction "VDD_P16") (pintype "passive"))
      (node (ref "U4") (pin "P18") (pinfunction "VDD_P18") (pintype "passive"))
      (node (ref "U4") (pin "P2") (pinfunction "VDD_P2") (pintype "passive"))
      (node (ref "U4") (pin "P20") (pinfunction "VDD_P20") (pintype "passive"))
      (node (ref "U4") (pin "P4") (pinfunction "VDD_P4") (pintype "passive"))
      (node (ref "U4") (pin "P6") (pinfunction "VDD_P6") (pintype "passive"))
      (node (ref "U4") (pin "P8") (pinfunction "VDD_P8") (pintype "passive"))
      (node (ref "U4") (pin "R1") (pinfunction "VDD_R1") (pintype "passive"))
      (node (ref "U4") (pin "R11") (pinfunction "VDD_R11") (pintype "passive"))
      (node (ref "U4") (pin "R13") (pinfunction "VDD_R13") (pintype "passive"))
      (node (ref "U4") (pin "R15") (pinfunction "VDD_R15") (pintype "passive"))
      (node (ref "U4") (pin "R17") (pinfunction "VDD_R17") (pintype "passive"))
      (node (ref "U4") (pin "R19") (pinfunction "VDD_R19") (pintype "passive"))
      (node (ref "U4") (pin "R21") (pinfunction "VDD_R21") (pintype "passive"))
      (node (ref "U4") (pin "R3") (pinfunction "VDD_R3") (pintype "passive"))
      (node (ref "U4") (pin "R5") (pinfunction "VDD_R5") (pintype "passive"))
      (node (ref "U4") (pin "R7") (pinfunction "VDD_R7") (pintype "passive"))
      (node (ref "U4") (pin "R9") (pinfunction "VDD_R9") (pintype "passive"))
      (node (ref "U4") (pin "T10") (pinfunction "VDD_T10") (pintype "passive"))
      (node (ref "U4") (pin "T12") (pinfunction "VDD_T12") (pintype "passive"))
      (node (ref "U4") (pin "T14") (pinfunction "VDD_T14") (pintype "passive"))
      (node (ref "U4") (pin "T16") (pinfunction "VDD_T16") (pintype "passive"))
      (node (ref "U4") (pin "T18") (pinfunction "VDD_T18") (pintype "passive"))
      (node (ref "U4") (pin "T2") (pinfunction "VDD_T2") (pintype "passive"))
      (node (ref "U4") (pin "T20") (pinfunction "VDD_T20") (pintype "passive"))
      (node (ref "U4") (pin "T4") (pinfunction "VDD_T4") (pintype "passive"))
      (node (ref "U4") (pin "T6") (pinfunction "VDD_T6") (pintype "passive"))
      (node (ref "U4") (pin "T8") (pinfunction "VDD_T8") (pintype "passive"))
      (node (ref "U4") (pin "U1") (pinfunction "VDD_U1") (pintype "passive"))
      (node (ref "U4") (pin "U11") (pinfunction "VDD_U11") (pintype "passive"))
      (node (ref "U4") (pin "U13") (pinfunction "VDD_U13") (pintype "passive"))
      (node (ref "U4") (pin "U15") (pinfunction "VDD_U15") (pintype "passive"))
      (node (ref "U4") (pin "U17") (pinfunction "VDD_U17") (pintype "passive"))
      (node (ref "U4") (pin "U19") (pinfunction "VDD_U19") (pintype "passive"))
      (node (ref "U4") (pin "U21") (pinfunction "VDD_U21") (pintype "passive"))
      (node (ref "U4") (pin "U3") (pinfunction "VDD_U3") (pintype "passive"))
      (node (ref "U4") (pin "U5") (pinfunction "VDD_U5") (pintype "passive"))
      (node (ref "U4") (pin "U7") (pinfunction "VDD_U7") (pintype "passive"))
      (node (ref "U4") (pin "U9") (pinfunction "VDD_U9") (pintype "passive"))
      (node (ref "U4") (pin "V10") (pinfunction "VDD_V10") (pintype "passive"))
      (node (ref "U4") (pin "V12") (pinfunction "VDD_V12") (pintype "passive"))
      (node (ref "U4") (pin "V14") (pinfunction "VDD_V14") (pintype "passive"))
      (node (ref "U4") (pin "V16") (pinfunction "VDD_V16") (pintype "passive"))
      (node (ref "U4") (pin "V18") (pinfunction "VDD_V18") (pintype "passive"))
      (node (ref "U4") (pin "V2") (pinfunction "VDD_V2") (pintype "passive"))
      (node (ref "U4") (pin "V20") (pinfunction "VDD_V20") (pintype "passive"))
      (node (ref "U4") (pin "V4") (pinfunction "VDD_V4") (pintype "passive"))
      (node (ref "U4") (pin "V6") (pinfunction "VDD_V6") (pintype "passive"))
      (node (ref "U4") (pin "V8") (pinfunction "VDD_V8") (pintype "passive"))
      (node (ref "U4") (pin "W1") (pinfunction "VDD_W1") (pintype "passive"))
      (node (ref "U4") (pin "W11") (pinfunction "VDD_W11") (pintype "passive"))
      (node (ref "U4") (pin "W13") (pinfunction "VDD_W13") (pintype "passive"))
      (node (ref "U4") (pin "W15") (pinfunction "VDD_W15") (pintype "passive"))
      (node (ref "U4") (pin "W17") (pinfunction "VDD_W17") (pintype "passive"))
      (node (ref "U4") (pin "W19") (pinfunction "VDD_W19") (pintype "passive"))
      (node (ref "U4") (pin "W21") (pinfunction "VDD_W21") (pintype "passive"))
      (node (ref "U4") (pin "W3") (pinfunction "VDD_W3") (pintype "passive"))
      (node (ref "U4") (pin "W5") (pinfunction "VDD_W5") (pintype "passive"))
      (node (ref "U4") (pin "W7") (pinfunction "VDD_W7") (pintype "passive"))
      (node (ref "U4") (pin "W9") (pinfunction "VDD_W9") (pintype "passive"))
      (node (ref "U4") (pin "Y10") (pinfunction "VDD_Y10") (pintype "passive"))
      (node (ref "U4") (pin "Y12") (pinfunction "VDD_Y12") (pintype "passive"))
      (node (ref "U4") (pin "Y14") (pinfunction "VDD_Y14") (pintype "passive"))
      (node (ref "U4") (pin "Y16") (pinfunction "VDD_Y16") (pintype "passive"))
      (node (ref "U4") (pin "Y18") (pinfunction "VDD_Y18") (pintype "passive"))
      (node (ref "U4") (pin "Y2") (pinfunction "VDD_Y2") (pintype "passive"))
      (node (ref "U4") (pin "Y20") (pinfunction "VDD_Y20") (pintype "passive"))
      (node (ref "U4") (pin "Y4") (pinfunction "VDD_Y4") (pintype "passive"))
      (node (ref "U4") (pin "Y6") (pinfunction "VDD_Y6") (pintype "passive"))
      (node (ref "U4") (pin "Y8") (pinfunction "VDD_Y8") (pintype "passive"))
    )
    (net (code "2") (name "GND") (class "Default")
      (node (ref "C148") (pin "1") (pinfunction "1_1") (pintype "passive"))
      (node (ref "C149") (pin "1") (pinfunction "1_1") (pintype "passive"))
      (node (ref "C150") (pin "1") (pinfunction "1_1") (pintype "passive"))
      (node (ref "C151") (pin "1") (pinfunction "1_1") (pintype "passive"))
      (node (ref "C152") (pin "1") (pinfunction "1_1") (pintype "passive"))
      (node (ref "C153") (pin "1") (pinfunction "1_1") (pintype "passive"))
      (node (ref "C154") (pin "1") (pinfunction "1_1") (pintype "passive"))
      (node (ref "C155") (pin "1") (pinfunction "1_1") (pintype "passive"))
      (node (ref "C156") (pin "1") (pinfunction "1_1") (pintype "passive"))
      (node (ref "C157") (pin "1") (pinfunction "1_1") (pintype "passive"))
      (node (ref "C158") (pin "1") (pinfunction "1_1") (pintype "passive"))
      (node (ref "C159") (pin "1") (pinfunction "1_1") (pintype "passive"))
      (node (ref "C160") (pin "1") (pinfunction "1_1") (pintype "passive"))
      (node (ref "C161") (pin "1") (pinfunction "1_1") (pintype "passive"))
      (node (ref "C162") (pin "1") (pinfunction "1_1") (pintype "passive"))
      (node (ref "C163") (pin "1") (pinfunction "1_1") (pintype "passive"))
      (node (ref "C164") (pin "1") (pinfunction "1_1") (pintype "passive"))
      (node (ref "C165") (pin "1") (pinfunction "1_1") (pintype "passive"))
      (node (ref "C166") (pin "1") (pinfunction "1_1") (pintype "passive"))
      (node (ref "C167") (pin "1") (pinfunction "1_1") (pintype "passive"))
      (node (ref "C169") (pin "1") (pinfunction "1_1") (pintype "passive"))
      (node (ref "C170") (pin "1") (pinfunction "1_1") (pintype "passive"))
      (node (ref "C171") (pin "1") (pinfunction "1_1") (pintype "passive"))
      (node (ref "C172") (pin "1") (pinfunction "1_1") (pintype "passive"))
      (node (ref "C173") (pin "1") (pinfunction "1_1") (pintype "passive"))
      (node (ref "C174") (pin "1") (pinfunction "1_1") (pintype "passive"))
      (node (ref "C175") (pin "1") (pinfunction "1_1") (pintype "passive"))
      (node (ref "C176") (pin "1") (pinfunction "1_1") (pintype "passive"))
      (node (ref "C177") (pin "1") (pinfunction "1_1") (pintype "passive"))
      (node (ref "C178") (pin "1") (pinfunction "1_1") (pintype "passive"))
      (node (ref "C179") (pin "1") (pinfunction "1_1") (pintype "passive"))
      (node (ref "C180") (pin "1") (pinfunction "1_1") (pintype "passive"))
      (node (ref "C181") (pin "1") (pinfunction "1_1") (pintype "passive"))
      (node (ref "C182") (pin "1") (pinfunction "1_1") (pintype "passive"))
      (node (ref "C183") (pin "1") (pinfunction "1_1") (pintype "passive"))
      (node (ref "C184") (pin "1") (pinfunction "1_1") (pintype "passive"))
      (node (ref "C185") (pin "1") (pinfunction "1_1") (pintype "passive"))
      (node (ref "C186") (pin "1") (pinfunction "1_1") (pintype "passive"))
      (node (ref "C187") (pin "1") (pinfunction "1_1") (pintype "passive"))
      (node (ref "C188") (pin "1") (pinfunction "1_1") (pintype "passive"))
      (node (ref "C189") (pin "1") (pinfunction "1_1") (pintype "passive"))
      (node (ref "C19") (pin "1") (pinfunction "1_1") (pintype "passive"))
      (node (ref "C190") (pin "1") (pinfunction "1_1") (pintype "passive"))
      (node (ref "C191") (pin "1") (pinfunction "1_1") (pintype "passive"))
      (node (ref "C192") (pin "1") (pinfunction "1_1") (pintype "passive"))
      (node (ref "C193") (pin "1") (pinfunction "1_1") (pintype "passive"))
      (node (ref "C194") (pin "1") (pinfunction "1_1") (pintype "passive"))
      (node (ref "C195") (pin "1") (pinfunction "1_1") (pintype "passive"))
      (node (ref "C196") (pin "1") (pinfunction "1_1") (pintype "passive"))
      (node (ref "C197") (pin "1") (pinfunction "1_1") (pintype "passive"))
      (node (ref "C198") (pin "1") (pinfunction "1_1") (pintype "passive"))
      (node (ref "C199") (pin "1") (pinfunction "1_1") (pintype "passive"))
      (node (ref "C200") (pin "1") (pinfunction "1_1") (pintype "passive"))
      (node (ref "C201") (pin "1") (pinfunction "1_1") (pintype "passive"))
      (node (ref "C202") (pin "1") (pinfunction "1_1") (pintype "passive"))
      (node (ref "C203") (pin "1") (pinfunction "1_1") (pintype "passive"))
      (node (ref "C204") (pin "1") (pinfunction "1_1") (pintype "passive"))
      (node (ref "C205") (pin "1") (pinfunction "1_1") (pintype "passive"))
      (node (ref "C206") (pin "1") (pinfunction "1_1") (pintype "passive"))
      (node (ref "C207") (pin "1") (pinfunction "1_1") (pintype "passive"))
      (node (ref "C208") (pin "1") (pinfunction "1_1") (pintype "passive"))
      (node (ref "C209") (pin "1") (pinfunction "1_1") (pintype "passive"))
      (node (ref "C210") (pin "1") (pinfunction "1_1") (pintype "passive"))
      (node (ref "C211") (pin "1") (pinfunction "1_1") (pintype "passive"))
      (node (ref "C212") (pin "1") (pinfunction "1_1") (pintype "passive"))
      (node (ref "C213") (pin "1") (pinfunction "1_1") (pintype "passive"))
      (node (ref "C214") (pin "1") (pinfunction "1_1") (pintype "passive"))
      (node (ref "C215") (pin "1") (pinfunction "1_1") (pintype "passive"))
      (node (ref "C216") (pin "1") (pinfunction "1_1") (pintype "passive"))
      (node (ref "C217") (pin "1") (pinfunction "1_1") (pintype "passive"))
      (node (ref "C218") (pin "1") (pinfunction "1_1") (pintype "passive"))
      (node (ref "C219") (pin "1") (pinfunction "1_1") (pintype "passive"))
      (node (ref "C220") (pin "1") (pinfunction "1_1") (pintype "passive"))
      (node (ref "C221") (pin "1") (pinfunction "1_1") (pintype "passive"))
      (node (ref "C222") (pin "1") (pinfunction "1_1") (pintype "passive"))
      (node (ref "C223") (pin "1") (pinfunction "1_1") (pintype "passive"))
      (node (ref "C224") (pin "1") (pinfunction "1_1") (pintype "passive"))
      (node (ref "C225") (pin "1") (pinfunction "1_1") (pintype "passive"))
      (node (ref "C226") (pin "1") (pinfunction "1_1") (pintype "passive"))
      (node (ref "C36") (pin "1") (pinfunction "1_1") (pintype "passive"))
      (node (ref "U1") (pin "A10") (pinfunction "VSS_A10") (pintype "passive"))
      (node (ref "U1") (pin "A12") (pinfunction "VSS_A12") (pintype "passive"))
      (node (ref "U1") (pin "A14") (pinfunction "VSS_A14") (pintype "passive"))
      (node (ref "U1") (pin "A16") (pinfunction "VSS_A16") (pintype "passive"))
      (node (ref "U1") (pin "A18") (pinfunction "VSS_A18") (pintype "passive"))
      (node (ref "U1") (pin "A2") (pinfunction "VSS_A2") (pintype "passive"))
      (node (ref "U1") (pin "A20") (pinfunction "VSS_A20") (pintype "passive"))
      (node (ref "U1") (pin "A4") (pinfunction "VSS_A4") (pintype "passive"))
      (node (ref "U1") (pin "A6") (pinfunction "VSS_A6") (pintype "passive"))
      (node (ref "U1") (pin "A8") (pinfunction "VSS_A8") (pintype "passive"))
      (node (ref "U1") (pin "AA10") (pinfunction "VSS_AA10") (pintype "passive"))
      (node (ref "U1") (pin "AA12") (pinfunction "VSS_AA12") (pintype "passive"))
      (node (ref "U1") (pin "AA14") (pinfunction "VSS_AA14") (pintype "passive"))
      (node (ref "U1") (pin "AA16") (pinfunction "VSS_AA16") (pintype "passive"))
      (node (ref "U1") (pin "AA18") (pinfunction "VSS_AA18") (pintype "passive"))
      (node (ref "U1") (pin "AA2") (pinfunction "VSS_AA2") (pintype "passive"))
      (node (ref "U1") (pin "AA4") (pinfunction "VSS_AA4") (pintype "passive"))
      (node (ref "U1") (pin "AA6") (pinfunction "VSS_AA6") (pintype "passive"))
      (node (ref "U1") (pin "AA8") (pinfunction "VSS_AA8") (pintype "passive"))
      (node (ref "U1") (pin "AB11") (pinfunction "VSS_AB11") (pintype "passive"))
      (node (ref "U1") (pin "AB13") (pinfunction "VSS_AB13") (pintype "passive"))
      (node (ref "U1") (pin "AB15") (pinfunction "VSS_AB15") (pintype "passive"))
      (node (ref "U1") (pin "AB17") (pinfunction "VSS_AB17") (pintype "passive"))
      (node (ref "U1") (pin "AB3") (pinfunction "VSS_AB3") (pintype "passive"))
      (node (ref "U1") (pin "AB5") (pinfunction "VSS_AB5") (pintype "passive"))
      (node (ref "U1") (pin "AB7") (pinfunction "VSS_AB7") (pintype "passive"))
      (node (ref "U1") (pin "AB9") (pinfunction "VSS_AB9") (pintype "passive"))
      (node (ref "U1") (pin "B1") (pinfunction "VSS_B1") (pintype "passive"))
      (node (ref "U1") (pin "B11") (pinfunction "VSS_B11") (pintype "passive"))
      (node (ref "U1") (pin "B13") (pinfunction "VSS_B13") (pintype "passive"))
      (node (ref "U1") (pin "B15") (pinfunction "VSS_B15") (pintype "passive"))
      (node (ref "U1") (pin "B17") (pinfunction "VSS_B17") (pintype "passive"))
      (node (ref "U1") (pin "B19") (pinfunction "VSS_B19") (pintype "passive"))
      (node (ref "U1") (pin "B21") (pinfunction "VSS_B21") (pintype "passive"))
      (node (ref "U1") (pin "B22") (pinfunction "VSS_B22") (pintype "passive"))
      (node (ref "U1") (pin "B3") (pinfunction "VSS_B3") (pintype "passive"))
      (node (ref "U1") (pin "B5") (pinfunction "VSS_B5") (pintype "passive"))
      (node (ref "U1") (pin "B7") (pinfunction "VSS_B7") (pintype "passive"))
      (node (ref "U1") (pin "B9") (pinfunction "VSS_B9") (pintype "passive"))
      (node (ref "U1") (pin "C10") (pinfunction "VSS_C10") (pintype "passive"))
      (node (ref "U1") (pin "C12") (pinfunction "VSS_C12") (pintype "passive"))
      (node (ref "U1") (pin "C14") (pinfunction "VSS_C14") (pintype "passive"))
      (node (ref "U1") (pin "C16") (pinfunction "VSS_C16") (pintype "passive"))
      (node (ref "U1") (pin "C18") (pinfunction "VSS_C18") (pintype "passive"))
      (node (ref "U1") (pin "C2") (pinfunction "VSS_C2") (pintype "passive"))
      (node (ref "U1") (pin "C20") (pinfunction "VSS_C20") (pintype "passive"))
      (node (ref "U1") (pin "C4") (pinfunction "VSS_C4") (pintype "passive"))
      (node (ref "U1") (pin "C6") (pinfunction "VSS_C6") (pintype "passive"))
      (node (ref "U1") (pin "C8") (pinfunction "VSS_C8") (pintype "passive"))
      (node (ref "U1") (pin "D1") (pinfunction "VSS_D1") (pintype "passive"))
      (node (ref "U1") (pin "D11") (pinfunction "VSS_D11") (pintype "passive"))
      (node (ref "U1") (pin "D13") (pinfunction "VSS_D13") (pintype "passive"))
      (node (ref "U1") (pin "D15") (pinfunction "VSS_D15") (pintype "passive"))
      (node (ref "U1") (pin "D17") (pinfunction "VSS_D17") (pintype "passive"))
      (node (ref "U1") (pin "D19") (pinfunction "VSS_D19") (pintype "passive"))
      (node (ref "U1") (pin "D21") (pinfunction "VSS_D21") (pintype "passive"))
      (node (ref "U1") (pin "D22") (pinfunction "VSS_D22") (pintype "passive"))
      (node (ref "U1") (pin "D3") (pinfunction "VSS_D3") (pintype "passive"))
      (node (ref "U1") (pin "D5") (pinfunction "VSS_D5") (pintype "passive"))
      (node (ref "U1") (pin "D7") (pinfunction "VSS_D7") (pintype "passive"))
      (node (ref "U1") (pin "D9") (pinfunction "VSS_D9") (pintype "passive"))
      (node (ref "U1") (pin "E10") (pinfunction "VSS_E10") (pintype "passive"))
      (node (ref "U1") (pin "E12") (pinfunction "VSS_E12") (pintype "passive"))
      (node (ref "U1") (pin "E14") (pinfunction "VSS_E14") (pintype "passive"))
      (node (ref "U1") (pin "E16") (pinfunction "VSS_E16") (pintype "passive"))
      (node (ref "U1") (pin "E18") (pinfunction "VSS_E18") (pintype "passive"))
      (node (ref "U1") (pin "E2") (pinfunction "VSS_E2") (pintype "passive"))
      (node (ref "U1") (pin "E20") (pinfunction "VSS_E20") (pintype "passive"))
      (node (ref "U1") (pin "E4") (pinfunction "VSS_E4") (pintype "passive"))
      (node (ref "U1") (pin "E6") (pinfunction "VSS_E6") (pintype "passive"))
      (node (ref "U1") (pin "E8") (pinfunction "VSS_E8") (pintype "passive"))
      (node (ref "U1") (pin "F1") (pinfunction "VSS_F1") (pintype "passive"))
      (node (ref "U1") (pin "F11") (pinfunction "VSS_F11") (pintype "passive"))
      (node (ref "U1") (pin "F13") (pinfunction "VSS_F13") (pintype "passive"))
      (node (ref "U1") (pin "F15") (pinfunction "VSS_F15") (pintype "passive"))
      (node (ref "U1") (pin "F17") (pinfunction "VSS_F17") (pintype "passive"))
      (node (ref "U1") (pin "F19") (pinfunction "VSS_F19") (pintype "passive"))
      (node (ref "U1") (pin "F21") (pinfunction "VSS_F21") (pintype "passive"))
      (node (ref "U1") (pin "F22") (pinfunction "VSS_F22") (pintype "passive"))
      (node (ref "U1") (pin "F3") (pinfunction "VSS_F3") (pintype "passive"))
      (node (ref "U1") (pin "F5") (pinfunction "VSS_F5") (pintype "passive"))
      (node (ref "U1") (pin "F7") (pinfunction "VSS_F7") (pintype "passive"))
      (node (ref "U1") (pin "F9") (pinfunction "VSS_F9") (pintype "passive"))
      (node (ref "U1") (pin "G10") (pinfunction "VSS_G10") (pintype "passive"))
      (node (ref "U1") (pin "G12") (pinfunction "VSS_G12") (pintype "passive"))
      (node (ref "U1") (pin "G14") (pinfunction "VSS_G14") (pintype "passive"))
      (node (ref "U1") (pin "G16") (pinfunction "VSS_G16") (pintype "passive"))
      (node (ref "U1") (pin "G18") (pinfunction "VSS_G18") (pintype "passive"))
      (node (ref "U1") (pin "G2") (pinfunction "VSS_G2") (pintype "passive"))
      (node (ref "U1") (pin "G20") (pinfunction "VSS_G20") (pintype "passive"))
      (node (ref "U1") (pin "G4") (pinfunction "VSS_G4") (pintype "passive"))
      (node (ref "U1") (pin "G6") (pinfunction "VSS_G6") (pintype "passive"))
      (node (ref "U1") (pin "G8") (pinfunction "VSS_G8") (pintype "passive"))
      (node (ref "U1") (pin "H1") (pinfunction "VSS_H1") (pintype "passive"))
      (node (ref "U1") (pin "H11") (pinfunction "VSS_H11") (pintype "passive"))
      (node (ref "U1") (pin "H13") (pinfunction "VSS_H13") (pintype "passive"))
      (node (ref "U1") (pin "H15") (pinfunction "VSS_H15") (pintype "passive"))
      (node (ref "U1") (pin "H17") (pinfunction "VSS_H17") (pintype "passive"))
      (node (ref "U1") (pin "H19") (pinfunction "VSS_H19") (pintype "passive"))
      (node (ref "U1") (pin "H21") (pinfunction "VSS_H21") (pintype "passive"))
      (node (ref "U1") (pin "H22") (pinfunction "VSS_H22") (pintype "passive"))
      (node (ref "U1") (pin "H3") (pinfunction "VSS_H3") (pintype "passive"))
      (node (ref "U1") (pin "H5") (pinfunction "VSS_H5") (pintype "passive"))
      (node (ref "U1") (pin "H7") (pinfunction "VSS_H7") (pintype "passive"))
      (node (ref "U1") (pin "H9") (pinfunction "VSS_H9") (pintype "passive"))
      (node (ref "U1") (pin "J10") (pinfunction "VSS_J10") (pintype "passive"))
      (node (ref "U1") (pin "J12") (pinfunction "VSS_J12") (pintype "passive"))
      (node (ref "U1") (pin "J14") (pinfunction "VSS_J14") (pintype "passive"))
      (node (ref "U1") (pin "J16") (pinfunction "VSS_J16") (pintype "passive"))
      (node (ref "U1") (pin "J18") (pinfunction "VSS_J18") (pintype "passive"))
      (node (ref "U1") (pin "J2") (pinfunction "VSS_J2") (pintype "passive"))
      (node (ref "U1") (pin "J20") (pinfunction "VSS_J20") (pintype "passive"))
      (node (ref "U1") (pin "J4") (pinfunction "VSS_J4") (pintype "passive"))
      (node (ref "U1") (pin "J6") (pinfunction "VSS_J6") (pintype "passive"))
      (node (ref "U1") (pin "J8") (pinfunction "VSS_J8") (pintype "passive"))
      (node (ref "U1") (pin "K1") (pinfunction "VSS_K1") (pintype "passive"))
      (node (ref "U1") (pin "K11") (pinfunction "VSS_K11") (pintype "passive"))
      (node (ref "U1") (pin "K13") (pinfunction "VSS_K13") (pintype "passive"))
      (node (ref "U1") (pin "K15") (pinfunction "VSS_K15") (pintype "passive"))
      (node (ref "U1") (pin "K17") (pinfunction "VSS_K17") (pintype "passive"))
      (node (ref "U1") (pin "K19") (pinfunction "VSS_K19") (pintype "passive"))
      (node (ref "U1") (pin "K21") (pinfunction "VSS_K21") (pintype "passive"))
      (node (ref "U1") (pin "K22") (pinfunction "VSS_K22") (pintype "passive"))
      (node (ref "U1") (pin "K3") (pinfunction "VSS_K3") (pintype "passive"))
      (node (ref "U1") (pin "K5") (pinfunction "VSS_K5") (pintype "passive"))
      (node (ref "U1") (pin "K7") (pinfunction "VSS_K7") (pintype "passive"))
      (node (ref "U1") (pin "K9") (pinfunction "VSS_K9") (pintype "passive"))
      (node (ref "U1") (pin "L10") (pinfunction "VSS_L10") (pintype "passive"))
      (node (ref "U1") (pin "L12") (pinfunction "VSS_L12") (pintype "passive"))
      (node (ref "U1") (pin "L14") (pinfunction "VSS_L14") (pintype "passive"))
      (node (ref "U1") (pin "L16") (pinfunction "VSS_L16") (pintype "passive"))
      (node (ref "U1") (pin "L18") (pinfunction "VSS_L18") (pintype "passive"))
      (node (ref "U1") (pin "L2") (pinfunction "VSS_L2") (pintype "passive"))
      (node (ref "U1") (pin "L20") (pinfunction "VSS_L20") (pintype "passive"))
      (node (ref "U1") (pin "L4") (pinfunction "VSS_L4") (pintype "passive"))
      (node (ref "U1") (pin "L6") (pinfunction "VSS_L6") (pintype "passive"))
      (node (ref "U1") (pin "L8") (pinfunction "VSS_L8") (pintype "passive"))
      (node (ref "U1") (pin "M1") (pinfunction "VSS_M1") (pintype "passive"))
      (node (ref "U1") (pin "M11") (pinfunction "VSS_M11") (pintype "passive"))
      (node (ref "U1") (pin "M13") (pinfunction "VSS_M13") (pintype "passive"))
      (node (ref "U1") (pin "M15") (pinfunction "VSS_M15") (pintype "passive"))
      (node (ref "U1") (pin "M17") (pinfunction "VSS_M17") (pintype "passive"))
      (node (ref "U1") (pin "M19") (pinfunction "VSS_M19") (pintype "passive"))
      (node (ref "U1") (pin "M21") (pinfunction "VSS_M21") (pintype "passive"))
      (node (ref "U1") (pin "M3") (pinfunction "VSS_M3") (pintype "passive"))
      (node (ref "U1") (pin "M5") (pinfunction "VSS_M5") (pintype "passive"))
      (node (ref "U1") (pin "M7") (pinfunction "VSS_M7") (pintype "passive"))
      (node (ref "U1") (pin "M9") (pinfunction "VSS_M9") (pintype "passive"))
      (node (ref "U1") (pin "N10") (pinfunction "VSS_N10") (pintype "passive"))
      (node (ref "U1") (pin "N12") (pinfunction "VSS_N12") (pintype "passive"))
      (node (ref "U1") (pin "N14") (pinfunction "VSS_N14") (pintype "passive"))
      (node (ref "U1") (pin "N16") (pinfunction "VSS_N16") (pintype "passive"))
      (node (ref "U1") (pin "N18") (pinfunction "VSS_N18") (pintype "passive"))
      (node (ref "U1") (pin "N2") (pinfunction "VSS_N2") (pintype "passive"))
      (node (ref "U1") (pin "N4") (pinfunction "VSS_N4") (pintype "passive"))
      (node (ref "U1") (pin "N6") (pinfunction "VSS_N6") (pintype "passive"))
      (node (ref "U1") (pin "N8") (pinfunction "VSS_N8") (pintype "passive"))
      (node (ref "U1") (pin "P1") (pinfunction "VSS_P1") (pintype "passive"))
      (node (ref "U1") (pin "P11") (pinfunction "VSS_P11") (pintype "passive"))
      (node (ref "U1") (pin "P13") (pinfunction "VSS_P13") (pintype "passive"))
      (node (ref "U1") (pin "P15") (pinfunction "VSS_P15") (pintype "passive"))
      (node (ref "U1") (pin "P17") (pinfunction "VSS_P17") (pintype "passive"))
      (node (ref "U1") (pin "P19") (pinfunction "VSS_P19") (pintype "passive"))
      (node (ref "U1") (pin "P21") (pinfunction "VSS_P21") (pintype "passive"))
      (node (ref "U1") (pin "P22") (pinfunction "VSS_P22") (pintype "passive"))
      (node (ref "U1") (pin "P3") (pinfunction "VSS_P3") (pintype "passive"))
      (node (ref "U1") (pin "P5") (pinfunction "VSS_P5") (pintype "passive"))
      (node (ref "U1") (pin "P7") (pinfunction "VSS_P7") (pintype "passive"))
      (node (ref "U1") (pin "P9") (pinfunction "VSS_P9") (pintype "passive"))
      (node (ref "U1") (pin "R10") (pinfunction "VSS_R10") (pintype "passive"))
      (node (ref "U1") (pin "R12") (pinfunction "VSS_R12") (pintype "passive"))
      (node (ref "U1") (pin "R14") (pinfunction "VSS_R14") (pintype "passive"))
      (node (ref "U1") (pin "R16") (pinfunction "VSS_R16") (pintype "passive"))
      (node (ref "U1") (pin "R18") (pinfunction "VSS_R18") (pintype "passive"))
      (node (ref "U1") (pin "R2") (pinfunction "VSS_R2") (pintype "passive"))
      (node (ref "U1") (pin "R20") (pinfunction "VSS_R20") (pintype "passive"))
      (node (ref "U1") (pin "R4") (pinfunction "VSS_R4") (pintype "passive"))
      (node (ref "U1") (pin "R6") (pinfunction "VSS_R6") (pintype "passive"))
      (node (ref "U1") (pin "R8") (pinfunction "VSS_R8") (pintype "passive"))
      (node (ref "U1") (pin "T1") (pinfunction "VSS_T1") (pintype "passive"))
      (node (ref "U1") (pin "T11") (pinfunction "VSS_T11") (pintype "passive"))
      (node (ref "U1") (pin "T13") (pinfunction "VSS_T13") (pintype "passive"))
      (node (ref "U1") (pin "T15") (pinfunction "VSS_T15") (pintype "passive"))
      (node (ref "U1") (pin "T17") (pinfunction "VSS_T17") (pintype "passive"))
      (node (ref "U1") (pin "T19") (pinfunction "VSS_T19") (pintype "passive"))
      (node (ref "U1") (pin "T21") (pinfunction "VSS_T21") (pintype "passive"))
      (node (ref "U1") (pin "T22") (pinfunction "VSS_T22") (pintype "passive"))
      (node (ref "U1") (pin "T3") (pinfunction "VSS_T3") (pintype "passive"))
      (node (ref "U1") (pin "T5") (pinfunction "VSS_T5") (pintype "passive"))
      (node (ref "U1") (pin "T7") (pinfunction "VSS_T7") (pintype "passive"))
      (node (ref "U1") (pin "T9") (pinfunction "VSS_T9") (pintype "passive"))
      (node (ref "U1") (pin "U10") (pinfunction "VSS_U10") (pintype "passive"))
      (node (ref "U1") (pin "U12") (pinfunction "VSS_U12") (pintype "passive"))
      (node (ref "U1") (pin "U14") (pinfunction "VSS_U14") (pintype "passive"))
      (node (ref "U1") (pin "U16") (pinfunction "VSS_U16") (pintype "passive"))
      (node (ref "U1") (pin "U18") (pinfunction "VSS_U18") (pintype "passive"))
      (node (ref "U1") (pin "U2") (pinfunction "VSS_U2") (pintype "passive"))
      (node (ref "U1") (pin "U20") (pinfunction "VSS_U20") (pintype "passive"))
      (node (ref "U1") (pin "U4") (pinfunction "VSS_U4") (pintype "passive"))
      (node (ref "U1") (pin "U6") (pinfunction "VSS_U6") (pintype "passive"))
      (node (ref "U1") (pin "U8") (pinfunction "VSS_U8") (pintype "passive"))
      (node (ref "U1") (pin "V1") (pinfunction "VSS_V1") (pintype "passive"))
      (node (ref "U1") (pin "V11") (pinfunction "VSS_V11") (pintype "passive"))
      (node (ref "U1") (pin "V13") (pinfunction "VSS_V13") (pintype "passive"))
      (node (ref "U1") (pin "V15") (pinfunction "VSS_V15") (pintype "passive"))
      (node (ref "U1") (pin "V17") (pinfunction "VSS_V17") (pintype "passive"))
      (node (ref "U1") (pin "V19") (pinfunction "VSS_V19") (pintype "passive"))
      (node (ref "U1") (pin "V21") (pinfunction "VSS_V21") (pintype "passive"))
      (node (ref "U1") (pin "V22") (pinfunction "VSS_V22") (pintype "passive"))
      (node (ref "U1") (pin "V3") (pinfunction "VSS_V3") (pintype "passive"))
      (node (ref "U1") (pin "V5") (pinfunction "VSS_V5") (pintype "passive"))
      (node (ref "U1") (pin "V7") (pinfunction "VSS_V7") (pintype "passive"))
      (node (ref "U1") (pin "V9") (pinfunction "VSS_V9") (pintype "passive"))
      (node (ref "U1") (pin "W10") (pinfunction "VSS_W10") (pintype "passive"))
      (node (ref "U1") (pin "W12") (pinfunction "VSS_W12") (pintype "passive"))
      (node (ref "U1") (pin "W14") (pinfunction "VSS_W14") (pintype "passive"))
      (node (ref "U1") (pin "W16") (pinfunction "VSS_W16") (pintype "passive"))
      (node (ref "U1") (pin "W18") (pinfunction "VSS_W18") (pintype "passive"))
      (node (ref "U1") (pin "W2") (pinfunction "VSS_W2") (pintype "passive"))
      (node (ref "U1") (pin "W20") (pinfunction "VSS_W20") (pintype "passive"))
      (node (ref "U1") (pin "W4") (pinfunction "VSS_W4") (pintype "passive"))
      (node (ref "U1") (pin "W6") (pinfunction "VSS_W6") (pintype "passive"))
      (node (ref "U1") (pin "W8") (pinfunction "VSS_W8") (pintype "passive"))
      (node (ref "U1") (pin "Y1") (pinfunction "VSS_Y1") (pintype "passive"))
      (node (ref "U1") (pin "Y11") (pinfunction "VSS_Y11") (pintype "passive"))
      (node (ref "U1") (pin "Y13") (pinfunction "VSS_Y13") (pintype "passive"))
      (node (ref "U1") (pin "Y15") (pinfunction "VSS_Y15") (pintype "passive"))
      (node (ref "U1") (pin "Y17") (pinfunction "VSS_Y17") (pintype "passive"))
      (node (ref "U1") (pin "Y19") (pinfunction "VSS_Y19") (pintype "passive"))
      (node (ref "U1") (pin "Y21") (pinfunction "VSS_Y21") (pintype "passive"))
      (node (ref "U1") (pin "Y22") (pinfunction "VSS_Y22") (pintype "passive"))
      (node (ref "U1") (pin "Y3") (pinfunction "VSS_Y3") (pintype "passive"))
      (node (ref "U1") (pin "Y5") (pinfunction "VSS_Y5") (pintype "passive"))
      (node (ref "U1") (pin "Y7") (pinfunction "VSS_Y7") (pintype "passive"))
      (node (ref "U1") (pin "Y9") (pinfunction "VSS_Y9") (pintype "passive"))
      (node (ref "U2") (pin "A10") (pinfunction "VSS_A10") (pintype "passive"))
      (node (ref "U2") (pin "A12") (pinfunction "VSS_A12") (pintype "passive"))
      (node (ref "U2") (pin "A14") (pinfunction "VSS_A14") (pintype "passive"))
      (node (ref "U2") (pin "A16") (pinfunction "VSS_A16") (pintype "passive"))
      (node (ref "U2") (pin "A18") (pinfunction "VSS_A18") (pintype "passive"))
      (node (ref "U2") (pin "A2") (pinfunction "VSS_A2") (pintype "passive"))
      (node (ref "U2") (pin "A20") (pinfunction "VSS_A20") (pintype "passive"))
      (node (ref "U2") (pin "A4") (pinfunction "VSS_A4") (pintype "passive"))
      (node (ref "U2") (pin "A6") (pinfunction "VSS_A6") (pintype "passive"))
      (node (ref "U2") (pin "A8") (pinfunction "VSS_A8") (pintype "passive"))
      (node (ref "U2") (pin "AA10") (pinfunction "VSS_AA10") (pintype "passive"))
      (node (ref "U2") (pin "AA12") (pinfunction "VSS_AA12") (pintype "passive"))
      (node (ref "U2") (pin "AA14") (pinfunction "VSS_AA14") (pintype "passive"))
      (node (ref "U2") (pin "AA16") (pinfunction "VSS_AA16") (pintype "passive"))
      (node (ref "U2") (pin "AA18") (pinfunction "VSS_AA18") (pintype "passive"))
      (node (ref "U2") (pin "AA2") (pinfunction "VSS_AA2") (pintype "passive"))
      (node (ref "U2") (pin "AA4") (pinfunction "VSS_AA4") (pintype "passive"))
      (node (ref "U2") (pin "AA6") (pinfunction "VSS_AA6") (pintype "passive"))
      (node (ref "U2") (pin "AA8") (pinfunction "VSS_AA8") (pintype "passive"))
      (node (ref "U2") (pin "AB11") (pinfunction "VSS_AB11") (pintype "passive"))
      (node (ref "U2") (pin "AB13") (pinfunction "VSS_AB13") (pintype "passive"))
      (node (ref "U2") (pin "AB15") (pinfunction "VSS_AB15") (pintype "passive"))
      (node (ref "U2") (pin "AB17") (pinfunction "VSS_AB17") (pintype "passive"))
      (node (ref "U2") (pin "AB3") (pinfunction "VSS_AB3") (pintype "passive"))
      (node (ref "U2") (pin "AB5") (pinfunction "VSS_AB5") (pintype "passive"))
      (node (ref "U2") (pin "AB7") (pinfunction "VSS_AB7") (pintype "passive"))
      (node (ref "U2") (pin "AB9") (pinfunction "VSS_AB9") (pintype "passive"))
      (node (ref "U2") (pin "B1") (pinfunction "VSS_B1") (pintype "passive"))
      (node (ref "U2") (pin "B11") (pinfunction "VSS_B11") (pintype "passive"))
      (node (ref "U2") (pin "B13") (pinfunction "VSS_B13") (pintype "passive"))
      (node (ref "U2") (pin "B15") (pinfunction "VSS_B15") (pintype "passive"))
      (node (ref "U2") (pin "B17") (pinfunction "VSS_B17") (pintype "passive"))
      (node (ref "U2") (pin "B19") (pinfunction "VSS_B19") (pintype "passive"))
      (node (ref "U2") (pin "B21") (pinfunction "VSS_B21") (pintype "passive"))
      (node (ref "U2") (pin "B22") (pinfunction "VSS_B22") (pintype "passive"))
      (node (ref "U2") (pin "B3") (pinfunction "VSS_B3") (pintype "passive"))
      (node (ref "U2") (pin "B5") (pinfunction "VSS_B5") (pintype "passive"))
      (node (ref "U2") (pin "B7") (pinfunction "VSS_B7") (pintype "passive"))
      (node (ref "U2") (pin "B9") (pinfunction "VSS_B9") (pintype "passive"))
      (node (ref "U2") (pin "C10") (pinfunction "VSS_C10") (pintype "passive"))
      (node (ref "U2") (pin "C12") (pinfunction "VSS_C12") (pintype "passive"))
      (node (ref "U2") (pin "C14") (pinfunction "VSS_C14") (pintype "passive"))
      (node (ref "U2") (pin "C16") (pinfunction "VSS_C16") (pintype "passive"))
      (node (ref "U2") (pin "C18") (pinfunction "VSS_C18") (pintype "passive"))
      (node (ref "U2") (pin "C2") (pinfunction "VSS_C2") (pintype "passive"))
      (node (ref "U2") (pin "C20") (pinfunction "VSS_C20") (pintype "passive"))
      (node (ref "U2") (pin "C4") (pinfunction "VSS_C4") (pintype "passive"))
      (node (ref "U2") (pin "C6") (pinfunction "VSS_C6") (pintype "passive"))
      (node (ref "U2") (pin "C8") (pinfunction "VSS_C8") (pintype "passive"))
      (node (ref "U2") (pin "D1") (pinfunction "VSS_D1") (pintype "passive"))
      (node (ref "U2") (pin "D11") (pinfunction "VSS_D11") (pintype "passive"))
      (node (ref "U2") (pin "D13") (pinfunction "VSS_D13") (pintype "passive"))
      (node (ref "U2") (pin "D15") (pinfunction "VSS_D15") (pintype "passive"))
      (node (ref "U2") (pin "D17") (pinfunction "VSS_D17") (pintype "passive"))
      (node (ref "U2") (pin "D19") (pinfunction "VSS_D19") (pintype "passive"))
      (node (ref "U2") (pin "D21") (pinfunction "VSS_D21") (pintype "passive"))
      (node (ref "U2") (pin "D22") (pinfunction "VSS_D22") (pintype "passive"))
      (node (ref "U2") (pin "D3") (pinfunction "VSS_D3") (pintype "passive"))
      (node (ref "U2") (pin "D5") (pinfunction "VSS_D5") (pintype "passive"))
      (node (ref "U2") (pin "D7") (pinfunction "VSS_D7") (pintype "passive"))
      (node (ref "U2") (pin "D9") (pinfunction "VSS_D9") (pintype "passive"))
      (node (ref "U2") (pin "E10") (pinfunction "VSS_E10") (pintype "passive"))
      (node (ref "U2") (pin "E12") (pinfunction "VSS_E12") (pintype "passive"))
      (node (ref "U2") (pin "E14") (pinfunction "VSS_E14") (pintype "passive"))
      (node (ref "U2") (pin "E16") (pinfunction "VSS_E16") (pintype "passive"))
      (node (ref "U2") (pin "E18") (pinfunction "VSS_E18") (pintype "passive"))
      (node (ref "U2") (pin "E2") (pinfunction "VSS_E2") (pintype "passive"))
      (node (ref "U2") (pin "E20") (pinfunction "VSS_E20") (pintype "passive"))
      (node (ref "U2") (pin "E4") (pinfunction "VSS_E4") (pintype "passive"))
      (node (ref "U2") (pin "E6") (pinfunction "VSS_E6") (pintype "passive"))
      (node (ref "U2") (pin "E8") (pinfunction "VSS_E8") (pintype "passive"))
      (node (ref "U2") (pin "F1") (pinfunction "VSS_F1") (pintype "passive"))
      (node (ref "U2") (pin "F11") (pinfunction "VSS_F11") (pintype "passive"))
      (node (ref "U2") (pin "F13") (pinfunction "VSS_F13") (pintype "passive"))
      (node (ref "U2") (pin "F15") (pinfunction "VSS_F15") (pintype "passive"))
      (node (ref "U2") (pin "F17") (pinfunction "VSS_F17") (pintype "passive"))
      (node (ref "U2") (pin "F19") (pinfunction "VSS_F19") (pintype "passive"))
      (node (ref "U2") (pin "F21") (pinfunction "VSS_F21") (pintype "passive"))
      (node (ref "U2") (pin "F22") (pinfunction "VSS_F22") (pintype "passive"))
      (node (ref "U2") (pin "F3") (pinfunction "VSS_F3") (pintype "passive"))
      (node (ref "U2") (pin "F5") (pinfunction "VSS_F5") (pintype "passive"))
      (node (ref "U2") (pin "F7") (pinfunction "VSS_F7") (pintype "passive"))
      (node (ref "U2") (pin "F9") (pinfunction "VSS_F9") (pintype "passive"))
      (node (ref "U2") (pin "G10") (pinfunction "VSS_G10") (pintype "passive"))
      (node (ref "U2") (pin "G12") (pinfunction "VSS_G12") (pintype "passive"))
      (node (ref "U2") (pin "G14") (pinfunction "VSS_G14") (pintype "passive"))
      (node (ref "U2") (pin "G16") (pinfunction "VSS_G16") (pintype "passive"))
      (node (ref "U2") (pin "G18") (pinfunction "VSS_G18") (pintype "passive"))
      (node (ref "U2") (pin "G2") (pinfunction "VSS_G2") (pintype "passive"))
      (node (ref "U2") (pin "G20") (pinfunction "VSS_G20") (pintype "passive"))
      (node (ref "U2") (pin "G4") (pinfunction "VSS_G4") (pintype "passive"))
      (node (ref "U2") (pin "G6") (pinfunction "VSS_G6") (pintype "passive"))
      (node (ref "U2") (pin "G8") (pinfunction "VSS_G8") (pintype "passive"))
      (node (ref "U2") (pin "H1") (pinfunction "VSS_H1") (pintype "passive"))
      (node (ref "U2") (pin "H11") (pinfunction "VSS_H11") (pintype "passive"))
      (node (ref "U2") (pin "H13") (pinfunction "VSS_H13") (pintype "passive"))
      (node (ref "U2") (pin "H15") (pinfunction "VSS_H15") (pintype "passive"))
      (node (ref "U2") (pin "H17") (pinfunction "VSS_H17") (pintype "passive"))
      (node (ref "U2") (pin "H19") (pinfunction "VSS_H19") (pintype "passive"))
      (node (ref "U2") (pin "H21") (pinfunction "VSS_H21") (pintype "passive"))
      (node (ref "U2") (pin "H22") (pinfunction "VSS_H22") (pintype "passive"))
      (node (ref "U2") (pin "H3") (pinfunction "VSS_H3") (pintype "passive"))
      (node (ref "U2") (pin "H5") (pinfunction "VSS_H5") (pintype "passive"))
      (node (ref "U2") (pin "H7") (pinfunction "VSS_H7") (pintype "passive"))
      (node (ref "U2") (pin "H9") (pinfunction "VSS_H9") (pintype "passive"))
      (node (ref "U2") (pin "J10") (pinfunction "VSS_J10") (pintype "passive"))
      (node (ref "U2") (pin "J12") (pinfunction "VSS_J12") (pintype "passive"))
      (node (ref "U2") (pin "J14") (pinfunction "VSS_J14") (pintype "passive"))
      (node (ref "U2") (pin "J16") (pinfunction "VSS_J16") (pintype "passive"))
      (node (ref "U2") (pin "J18") (pinfunction "VSS_J18") (pintype "passive"))
      (node (ref "U2") (pin "J2") (pinfunction "VSS_J2") (pintype "passive"))
      (node (ref "U2") (pin "J20") (pinfunction "VSS_J20") (pintype "passive"))
      (node (ref "U2") (pin "J4") (pinfunction "VSS_J4") (pintype "passive"))
      (node (ref "U2") (pin "J6") (pinfunction "VSS_J6") (pintype "passive"))
      (node (ref "U2") (pin "J8") (pinfunction "VSS_J8") (pintype "passive"))
      (node (ref "U2") (pin "K1") (pinfunction "VSS_K1") (pintype "passive"))
      (node (ref "U2") (pin "K11") (pinfunction "VSS_K11") (pintype "passive"))
      (node (ref "U2") (pin "K13") (pinfunction "VSS_K13") (pintype "passive"))
      (node (ref "U2") (pin "K15") (pinfunction "VSS_K15") (pintype "passive"))
      (node (ref "U2") (pin "K17") (pinfunction "VSS_K17") (pintype "passive"))
      (node (ref "U2") (pin "K19") (pinfunction "VSS_K19") (pintype "passive"))
      (node (ref "U2") (pin "K21") (pinfunction "VSS_K21") (pintype "passive"))
      (node (ref "U2") (pin "K22") (pinfunction "VSS_K22") (pintype "passive"))
      (node (ref "U2") (pin "K3") (pinfunction "VSS_K3") (pintype "passive"))
      (node (ref "U2") (pin "K5") (pinfunction "VSS_K5") (pintype "passive"))
      (node (ref "U2") (pin "K7") (pinfunction "VSS_K7") (pintype "passive"))
      (node (ref "U2") (pin "K9") (pinfunction "VSS_K9") (pintype "passive"))
      (node (ref "U2") (pin "L10") (pinfunction "VSS_L10") (pintype "passive"))
      (node (ref "U2") (pin "L12") (pinfunction "VSS_L12") (pintype "passive"))
      (node (ref "U2") (pin "L14") (pinfunction "VSS_L14") (pintype "passive"))
      (node (ref "U2") (pin "L16") (pinfunction "VSS_L16") (pintype "passive"))
      (node (ref "U2") (pin "L18") (pinfunction "VSS_L18") (pintype "passive"))
      (node (ref "U2") (pin "L2") (pinfunction "VSS_L2") (pintype "passive"))
      (node (ref "U2") (pin "L20") (pinfunction "VSS_L20") (pintype "passive"))
      (node (ref "U2") (pin "L4") (pinfunction "VSS_L4") (pintype "passive"))
      (node (ref "U2") (pin "L6") (pinfunction "VSS_L6") (pintype "passive"))
      (node (ref "U2") (pin "L8") (pinfunction "VSS_L8") (pintype "passive"))
      (node (ref "U2") (pin "M1") (pinfunction "VSS_M1") (pintype "passive"))
      (node (ref "U2") (pin "M11") (pinfunction "VSS_M11") (pintype "passive"))
      (node (ref "U2") (pin "M13") (pinfunction "VSS_M13") (pintype "passive"))
      (node (ref "U2") (pin "M15") (pinfunction "VSS_M15") (pintype "passive"))
      (node (ref "U2") (pin "M17") (pinfunction "VSS_M17") (pintype "passive"))
      (node (ref "U2") (pin "M19") (pinfunction "VSS_M19") (pintype "passive"))
      (node (ref "U2") (pin "M21") (pinfunction "VSS_M21") (pintype "passive"))
      (node (ref "U2") (pin "M3") (pinfunction "VSS_M3") (pintype "passive"))
      (node (ref "U2") (pin "M5") (pinfunction "VSS_M5") (pintype "passive"))
      (node (ref "U2") (pin "M7") (pinfunction "VSS_M7") (pintype "passive"))
      (node (ref "U2") (pin "M9") (pinfunction "VSS_M9") (pintype "passive"))
      (node (ref "U2") (pin "N10") (pinfunction "VSS_N10") (pintype "passive"))
      (node (ref "U2") (pin "N12") (pinfunction "VSS_N12") (pintype "passive"))
      (node (ref "U2") (pin "N14") (pinfunction "VSS_N14") (pintype "passive"))
      (node (ref "U2") (pin "N16") (pinfunction "VSS_N16") (pintype "passive"))
      (node (ref "U2") (pin "N18") (pinfunction "VSS_N18") (pintype "passive"))
      (node (ref "U2") (pin "N2") (pinfunction "VSS_N2") (pintype "passive"))
      (node (ref "U2") (pin "N4") (pinfunction "VSS_N4") (pintype "passive"))
      (node (ref "U2") (pin "N6") (pinfunction "VSS_N6") (pintype "passive"))
      (node (ref "U2") (pin "N8") (pinfunction "VSS_N8") (pintype "passive"))
      (node (ref "U2") (pin "P1") (pinfunction "VSS_P1") (pintype "passive"))
      (node (ref "U2") (pin "P11") (pinfunction "VSS_P11") (pintype "passive"))
      (node (ref "U2") (pin "P13") (pinfunction "VSS_P13") (pintype "passive"))
      (node (ref "U2") (pin "P15") (pinfunction "VSS_P15") (pintype "passive"))
      (node (ref "U2") (pin "P17") (pinfunction "VSS_P17") (pintype "passive"))
      (node (ref "U2") (pin "P19") (pinfunction "VSS_P19") (pintype "passive"))
      (node (ref "U2") (pin "P21") (pinfunction "VSS_P21") (pintype "passive"))
      (node (ref "U2") (pin "P22") (pinfunction "VSS_P22") (pintype "passive"))
      (node (ref "U2") (pin "P3") (pinfunction "VSS_P3") (pintype "passive"))
      (node (ref "U2") (pin "P5") (pinfunction "VSS_P5") (pintype "passive"))
      (node (ref "U2") (pin "P7") (pinfunction "VSS_P7") (pintype "passive"))
      (node (ref "U2") (pin "P9") (pinfunction "VSS_P9") (pintype "passive"))
      (node (ref "U2") (pin "R10") (pinfunction "VSS_R10") (pintype "passive"))
      (node (ref "U2") (pin "R12") (pinfunction "VSS_R12") (pintype "passive"))
      (node (ref "U2") (pin "R14") (pinfunction "VSS_R14") (pintype "passive"))
      (node (ref "U2") (pin "R16") (pinfunction "VSS_R16") (pintype "passive"))
      (node (ref "U2") (pin "R18") (pinfunction "VSS_R18") (pintype "passive"))
      (node (ref "U2") (pin "R2") (pinfunction "VSS_R2") (pintype "passive"))
      (node (ref "U2") (pin "R20") (pinfunction "VSS_R20") (pintype "passive"))
      (node (ref "U2") (pin "R4") (pinfunction "VSS_R4") (pintype "passive"))
      (node (ref "U2") (pin "R6") (pinfunction "VSS_R6") (pintype "passive"))
      (node (ref "U2") (pin "R8") (pinfunction "VSS_R8") (pintype "passive"))
      (node (ref "U2") (pin "T1") (pinfunction "VSS_T1") (pintype "passive"))
      (node (ref "U2") (pin "T11") (pinfunction "VSS_T11") (pintype "passive"))
      (node (ref "U2") (pin "T13") (pinfunction "VSS_T13") (pintype "passive"))
      (node (ref "U2") (pin "T15") (pinfunction "VSS_T15") (pintype "passive"))
      (node (ref "U2") (pin "T17") (pinfunction "VSS_T17") (pintype "passive"))
      (node (ref "U2") (pin "T19") (pinfunction "VSS_T19") (pintype "passive"))
      (node (ref "U2") (pin "T21") (pinfunction "VSS_T21") (pintype "passive"))
      (node (ref "U2") (pin "T22") (pinfunction "VSS_T22") (pintype "passive"))
      (node (ref "U2") (pin "T3") (pinfunction "VSS_T3") (pintype "passive"))
      (node (ref "U2") (pin "T5") (pinfunction "VSS_T5") (pintype "passive"))
      (node (ref "U2") (pin "T7") (pinfunction "VSS_T7") (pintype "passive"))
      (node (ref "U2") (pin "T9") (pinfunction "VSS_T9") (pintype "passive"))
      (node (ref "U2") (pin "U10") (pinfunction "VSS_U10") (pintype "passive"))
      (node (ref "U2") (pin "U12") (pinfunction "VSS_U12") (pintype "passive"))
      (node (ref "U2") (pin "U14") (pinfunction "VSS_U14") (pintype "passive"))
      (node (ref "U2") (pin "U16") (pinfunction "VSS_U16") (pintype "passive"))
      (node (ref "U2") (pin "U18") (pinfunction "VSS_U18") (pintype "passive"))
      (node (ref "U2") (pin "U2") (pinfunction "VSS_U2") (pintype "passive"))
      (node (ref "U2") (pin "U20") (pinfunction "VSS_U20") (pintype "passive"))
      (node (ref "U2") (pin "U4") (pinfunction "VSS_U4") (pintype "passive"))
      (node (ref "U2") (pin "U6") (pinfunction "VSS_U6") (pintype "passive"))
      (node (ref "U2") (pin "U8") (pinfunction "VSS_U8") (pintype "passive"))
      (node (ref "U2") (pin "V1") (pinfunction "VSS_V1") (pintype "passive"))
      (node (ref "U2") (pin "V11") (pinfunction "VSS_V11") (pintype "passive"))
      (node (ref "U2") (pin "V13") (pinfunction "VSS_V13") (pintype "passive"))
      (node (ref "U2") (pin "V15") (pinfunction "VSS_V15") (pintype "passive"))
      (node (ref "U2") (pin "V17") (pinfunction "VSS_V17") (pintype "passive"))
      (node (ref "U2") (pin "V19") (pinfunction "VSS_V19") (pintype "passive"))
      (node (ref "U2") (pin "V21") (pinfunction "VSS_V21") (pintype "passive"))
      (node (ref "U2") (pin "V22") (pinfunction "VSS_V22") (pintype "passive"))
      (node (ref "U2") (pin "V3") (pinfunction "VSS_V3") (pintype "passive"))
      (node (ref "U2") (pin "V5") (pinfunction "VSS_V5") (pintype "passive"))
      (node (ref "U2") (pin "V7") (pinfunction "VSS_V7") (pintype "passive"))
      (node (ref "U2") (pin "V9") (pinfunction "VSS_V9") (pintype "passive"))
      (node (ref "U2") (pin "W10") (pinfunction "VSS_W10") (pintype "passive"))
      (node (ref "U2") (pin "W12") (pinfunction "VSS_W12") (pintype "passive"))
      (node (ref "U2") (pin "W14") (pinfunction "VSS_W14") (pintype "passive"))
      (node (ref "U2") (pin "W16") (pinfunction "VSS_W16") (pintype "passive"))
      (node (ref "U2") (pin "W18") (pinfunction "VSS_W18") (pintype "passive"))
      (node (ref "U2") (pin "W2") (pinfunction "VSS_W2") (pintype "passive"))
      (node (ref "U2") (pin "W20") (pinfunction "VSS_W20") (pintype "passive"))
      (node (ref "U2") (pin "W4") (pinfunction "VSS_W4") (pintype "passive"))
      (node (ref "U2") (pin "W6") (pinfunction "VSS_W6") (pintype "passive"))
      (node (ref "U2") (pin "W8") (pinfunction "VSS_W8") (pintype "passive"))
      (node (ref "U2") (pin "Y1") (pinfunction "VSS_Y1") (pintype "passive"))
      (node (ref "U2") (pin "Y11") (pinfunction "VSS_Y11") (pintype "passive"))
      (node (ref "U2") (pin "Y13") (pinfunction "VSS_Y13") (pintype "passive"))
      (node (ref "U2") (pin "Y15") (pinfunction "VSS_Y15") (pintype "passive"))
      (node (ref "U2") (pin "Y17") (pinfunction "VSS_Y17") (pintype "passive"))
      (node (ref "U2") (pin "Y19") (pinfunction "VSS_Y19") (pintype "passive"))
      (node (ref "U2") (pin "Y21") (pinfunction "VSS_Y21") (pintype "passive"))
      (node (ref "U2") (pin "Y22") (pinfunction "VSS_Y22") (pintype "passive"))
      (node (ref "U2") (pin "Y3") (pinfunction "VSS_Y3") (pintype "passive"))
      (node (ref "U2") (pin "Y5") (pinfunction "VSS_Y5") (pintype "passive"))
      (node (ref "U2") (pin "Y7") (pinfunction "VSS_Y7") (pintype "passive"))
      (node (ref "U2") (pin "Y9") (pinfunction "VSS_Y9") (pintype "passive"))
      (node (ref "U3") (pin "A10") (pinfunction "VSS_A10") (pintype "passive"))
      (node (ref "U3") (pin "A12") (pinfunction "VSS_A12") (pintype "passive"))
      (node (ref "U3") (pin "A14") (pinfunction "VSS_A14") (pintype "passive"))
      (node (ref "U3") (pin "A16") (pinfunction "VSS_A16") (pintype "passive"))
      (node (ref "U3") (pin "A18") (pinfunction "VSS_A18") (pintype "passive"))
      (node (ref "U3") (pin "A2") (pinfunction "VSS_A2") (pintype "passive"))
      (node (ref "U3") (pin "A20") (pinfunction "VSS_A20") (pintype "passive"))
      (node (ref "U3") (pin "A4") (pinfunction "VSS_A4") (pintype "passive"))
      (node (ref "U3") (pin "A6") (pinfunction "VSS_A6") (pintype "passive"))
      (node (ref "U3") (pin "A8") (pinfunction "VSS_A8") (pintype "passive"))
      (node (ref "U3") (pin "AA10") (pinfunction "VSS_AA10") (pintype "passive"))
      (node (ref "U3") (pin "AA12") (pinfunction "VSS_AA12") (pintype "passive"))
      (node (ref "U3") (pin "AA14") (pinfunction "VSS_AA14") (pintype "passive"))
      (node (ref "U3") (pin "AA16") (pinfunction "VSS_AA16") (pintype "passive"))
      (node (ref "U3") (pin "AA18") (pinfunction "VSS_AA18") (pintype "passive"))
      (node (ref "U3") (pin "AA2") (pinfunction "VSS_AA2") (pintype "passive"))
      (node (ref "U3") (pin "AA4") (pinfunction "VSS_AA4") (pintype "passive"))
      (node (ref "U3") (pin "AA6") (pinfunction "VSS_AA6") (pintype "passive"))
      (node (ref "U3") (pin "AA8") (pinfunction "VSS_AA8") (pintype "passive"))
      (node (ref "U3") (pin "AB11") (pinfunction "VSS_AB11") (pintype "passive"))
      (node (ref "U3") (pin "AB13") (pinfunction "VSS_AB13") (pintype "passive"))
      (node (ref "U3") (pin "AB15") (pinfunction "VSS_AB15") (pintype "passive"))
      (node (ref "U3") (pin "AB17") (pinfunction "VSS_AB17") (pintype "passive"))
      (node (ref "U3") (pin "AB3") (pinfunction "VSS_AB3") (pintype "passive"))
      (node (ref "U3") (pin "AB5") (pinfunction "VSS_AB5") (pintype "passive"))
      (node (ref "U3") (pin "AB7") (pinfunction "VSS_AB7") (pintype "passive"))
      (node (ref "U3") (pin "AB9") (pinfunction "VSS_AB9") (pintype "passive"))
      (node (ref "U3") (pin "B1") (pinfunction "VSS_B1") (pintype "passive"))
      (node (ref "U3") (pin "B11") (pinfunction "VSS_B11") (pintype "passive"))
      (node (ref "U3") (pin "B13") (pinfunction "VSS_B13") (pintype "passive"))
      (node (ref "U3") (pin "B15") (pinfunction "VSS_B15") (pintype "passive"))
      (node (ref "U3") (pin "B17") (pinfunction "VSS_B17") (pintype "passive"))
      (node (ref "U3") (pin "B19") (pinfunction "VSS_B19") (pintype "passive"))
      (node (ref "U3") (pin "B21") (pinfunction "VSS_B21") (pintype "passive"))
      (node (ref "U3") (pin "B22") (pinfunction "VSS_B22") (pintype "passive"))
      (node (ref "U3") (pin "B3") (pinfunction "VSS_B3") (pintype "passive"))
      (node (ref "U3") (pin "B5") (pinfunction "VSS_B5") (pintype "passive"))
      (node (ref "U3") (pin "B7") (pinfunction "VSS_B7") (pintype "passive"))
      (node (ref "U3") (pin "B9") (pinfunction "VSS_B9") (pintype "passive"))
      (node (ref "U3") (pin "C10") (pinfunction "VSS_C10") (pintype "passive"))
      (node (ref "U3") (pin "C12") (pinfunction "VSS_C12") (pintype "passive"))
      (node (ref "U3") (pin "C14") (pinfunction "VSS_C14") (pintype "passive"))
      (node (ref "U3") (pin "C16") (pinfunction "VSS_C16") (pintype "passive"))
      (node (ref "U3") (pin "C18") (pinfunction "VSS_C18") (pintype "passive"))
      (node (ref "U3") (pin "C2") (pinfunction "VSS_C2") (pintype "passive"))
      (node (ref "U3") (pin "C20") (pinfunction "VSS_C20") (pintype "passive"))
      (node (ref "U3") (pin "C4") (pinfunction "VSS_C4") (pintype "passive"))
      (node (ref "U3") (pin "C6") (pinfunction "VSS_C6") (pintype "passive"))
      (node (ref "U3") (pin "C8") (pinfunction "VSS_C8") (pintype "passive"))
      (node (ref "U3") (pin "D1") (pinfunction "VSS_D1") (pintype "passive"))
      (node (ref "U3") (pin "D11") (pinfunction "VSS_D11") (pintype "passive"))
      (node (ref "U3") (pin "D13") (pinfunction "VSS_D13") (pintype "passive"))
      (node (ref "U3") (pin "D15") (pinfunction "VSS_D15") (pintype "passive"))
      (node (ref "U3") (pin "D17") (pinfunction "VSS_D17") (pintype "passive"))
      (node (ref "U3") (pin "D19") (pinfunction "VSS_D19") (pintype "passive"))
      (node (ref "U3") (pin "D21") (pinfunction "VSS_D21") (pintype "passive"))
      (node (ref "U3") (pin "D22") (pinfunction "VSS_D22") (pintype "passive"))
      (node (ref "U3") (pin "D3") (pinfunction "VSS_D3") (pintype "passive"))
      (node (ref "U3") (pin "D5") (pinfunction "VSS_D5") (pintype "passive"))
      (node (ref "U3") (pin "D7") (pinfunction "VSS_D7") (pintype "passive"))
      (node (ref "U3") (pin "D9") (pinfunction "VSS_D9") (pintype "passive"))
      (node (ref "U3") (pin "E10") (pinfunction "VSS_E10") (pintype "passive"))
      (node (ref "U3") (pin "E12") (pinfunction "VSS_E12") (pintype "passive"))
      (node (ref "U3") (pin "E14") (pinfunction "VSS_E14") (pintype "passive"))
      (node (ref "U3") (pin "E16") (pinfunction "VSS_E16") (pintype "passive"))
      (node (ref "U3") (pin "E18") (pinfunction "VSS_E18") (pintype "passive"))
      (node (ref "U3") (pin "E2") (pinfunction "VSS_E2") (pintype "passive"))
      (node (ref "U3") (pin "E20") (pinfunction "VSS_E20") (pintype "passive"))
      (node (ref "U3") (pin "E4") (pinfunction "VSS_E4") (pintype "passive"))
      (node (ref "U3") (pin "E6") (pinfunction "VSS_E6") (pintype "passive"))
      (node (ref "U3") (pin "E8") (pinfunction "VSS_E8") (pintype "passive"))
      (node (ref "U3") (pin "F1") (pinfunction "VSS_F1") (pintype "passive"))
      (node (ref "U3") (pin "F11") (pinfunction "VSS_F11") (pintype "passive"))
      (node (ref "U3") (pin "F13") (pinfunction "VSS_F13") (pintype "passive"))
      (node (ref "U3") (pin "F15") (pinfunction "VSS_F15") (pintype "passive"))
      (node (ref "U3") (pin "F17") (pinfunction "VSS_F17") (pintype "passive"))
      (node (ref "U3") (pin "F19") (pinfunction "VSS_F19") (pintype "passive"))
      (node (ref "U3") (pin "F21") (pinfunction "VSS_F21") (pintype "passive"))
      (node (ref "U3") (pin "F22") (pinfunction "VSS_F22") (pintype "passive"))
      (node (ref "U3") (pin "F3") (pinfunction "VSS_F3") (pintype "passive"))
      (node (ref "U3") (pin "F5") (pinfunction "VSS_F5") (pintype "passive"))
      (node (ref "U3") (pin "F7") (pinfunction "VSS_F7") (pintype "passive"))
      (node (ref "U3") (pin "F9") (pinfunction "VSS_F9") (pintype "passive"))
      (node (ref "U3") (pin "G10") (pinfunction "VSS_G10") (pintype "passive"))
      (node (ref "U3") (pin "G12") (pinfunction "VSS_G12") (pintype "passive"))
      (node (ref "U3") (pin "G14") (pinfunction "VSS_G14") (pintype "passive"))
      (node (ref "U3") (pin "G16") (pinfunction "VSS_G16") (pintype "passive"))
      (node (ref "U3") (pin "G18") (pinfunction "VSS_G18") (pintype "passive"))
      (node (ref "U3") (pin "G2") (pinfunction "VSS_G2") (pintype "passive"))
      (node (ref "U3") (pin "G20") (pinfunction "VSS_G20") (pintype "passive"))
      (node (ref "U3") (pin "G4") (pinfunction "VSS_G4") (pintype "passive"))
      (node (ref "U3") (pin "G6") (pinfunction "VSS_G6") (pintype "passive"))
      (node (ref "U3") (pin "G8") (pinfunction "VSS_G8") (pintype "passive"))
      (node (ref "U3") (pin "H1") (pinfunction "VSS_H1") (pintype "passive"))
      (node (ref "U3") (pin "H11") (pinfunction "VSS_H11") (pintype "passive"))
      (node (ref "U3") (pin "H13") (pinfunction "VSS_H13") (pintype "passive"))
      (node (ref "U3") (pin "H15") (pinfunction "VSS_H15") (pintype "passive"))
      (node (ref "U3") (pin "H17") (pinfunction "VSS_H17") (pintype "passive"))
      (node (ref "U3") (pin "H19") (pinfunction "VSS_H19") (pintype "passive"))
      (node (ref "U3") (pin "H21") (pinfunction "VSS_H21") (pintype "passive"))
      (node (ref "U3") (pin "H22") (pinfunction "VSS_H22") (pintype "passive"))
      (node (ref "U3") (pin "H3") (pinfunction "VSS_H3") (pintype "passive"))
      (node (ref "U3") (pin "H5") (pinfunction "VSS_H5") (pintype "passive"))
      (node (ref "U3") (pin "H7") (pinfunction "VSS_H7") (pintype "passive"))
      (node (ref "U3") (pin "H9") (pinfunction "VSS_H9") (pintype "passive"))
      (node (ref "U3") (pin "J10") (pinfunction "VSS_J10") (pintype "passive"))
      (node (ref "U3") (pin "J12") (pinfunction "VSS_J12") (pintype "passive"))
      (node (ref "U3") (pin "J14") (pinfunction "VSS_J14") (pintype "passive"))
      (node (ref "U3") (pin "J16") (pinfunction "VSS_J16") (pintype "passive"))
      (node (ref "U3") (pin "J18") (pinfunction "VSS_J18") (pintype "passive"))
      (node (ref "U3") (pin "J2") (pinfunction "VSS_J2") (pintype "passive"))
      (node (ref "U3") (pin "J20") (pinfunction "VSS_J20") (pintype "passive"))
      (node (ref "U3") (pin "J4") (pinfunction "VSS_J4") (pintype "passive"))
      (node (ref "U3") (pin "J6") (pinfunction "VSS_J6") (pintype "passive"))
      (node (ref "U3") (pin "J8") (pinfunction "VSS_J8") (pintype "passive"))
      (node (ref "U3") (pin "K1") (pinfunction "VSS_K1") (pintype "passive"))
      (node (ref "U3") (pin "K11") (pinfunction "VSS_K11") (pintype "passive"))
      (node (ref "U3") (pin "K13") (pinfunction "VSS_K13") (pintype "passive"))
      (node (ref "U3") (pin "K15") (pinfunction "VSS_K15") (pintype "passive"))
      (node (ref "U3") (pin "K17") (pinfunction "VSS_K17") (pintype "passive"))
      (node (ref "U3") (pin "K19") (pinfunction "VSS_K19") (pintype "passive"))
      (node (ref "U3") (pin "K21") (pinfunction "VSS_K21") (pintype "passive"))
      (node (ref "U3") (pin "K22") (pinfunction "VSS_K22") (pintype "passive"))
      (node (ref "U3") (pin "K3") (pinfunction "VSS_K3") (pintype "passive"))
      (node (ref "U3") (pin "K5") (pinfunction "VSS_K5") (pintype "passive"))
      (node (ref "U3") (pin "K7") (pinfunction "VSS_K7") (pintype "passive"))
      (node (ref "U3") (pin "K9") (pinfunction "VSS_K9") (pintype "passive"))
      (node (ref "U3") (pin "L10") (pinfunction "VSS_L10") (pintype "passive"))
      (node (ref "U3") (pin "L12") (pinfunction "VSS_L12") (pintype "passive"))
      (node (ref "U3") (pin "L14") (pinfunction "VSS_L14") (pintype "passive"))
      (node (ref "U3") (pin "L16") (pinfunction "VSS_L16") (pintype "passive"))
      (node (ref "U3") (pin "L18") (pinfunction "VSS_L18") (pintype "passive"))
      (node (ref "U3") (pin "L2") (pinfunction "VSS_L2") (pintype "passive"))
      (node (ref "U3") (pin "L20") (pinfunction "VSS_L20") (pintype "passive"))
      (node (ref "U3") (pin "L4") (pinfunction "VSS_L4") (pintype "passive"))
      (node (ref "U3") (pin "L6") (pinfunction "VSS_L6") (pintype "passive"))
      (node (ref "U3") (pin "L8") (pinfunction "VSS_L8") (pintype "passive"))
      (node (ref "U3") (pin "M1") (pinfunction "VSS_M1") (pintype "passive"))
      (node (ref "U3") (pin "M11") (pinfunction "VSS_M11") (pintype "passive"))
      (node (ref "U3") (pin "M13") (pinfunction "VSS_M13") (pintype "passive"))
      (node (ref "U3") (pin "M15") (pinfunction "VSS_M15") (pintype "passive"))
      (node (ref "U3") (pin "M17") (pinfunction "VSS_M17") (pintype "passive"))
      (node (ref "U3") (pin "M19") (pinfunction "VSS_M19") (pintype "passive"))
      (node (ref "U3") (pin "M21") (pinfunction "VSS_M21") (pintype "passive"))
      (node (ref "U3") (pin "M3") (pinfunction "VSS_M3") (pintype "passive"))
      (node (ref "U3") (pin "M5") (pinfunction "VSS_M5") (pintype "passive"))
      (node (ref "U3") (pin "M7") (pinfunction "VSS_M7") (pintype "passive"))
      (node (ref "U3") (pin "M9") (pinfunction "VSS_M9") (pintype "passive"))
      (node (ref "U3") (pin "N10") (pinfunction "VSS_N10") (pintype "passive"))
      (node (ref "U3") (pin "N12") (pinfunction "VSS_N12") (pintype "passive"))
      (node (ref "U3") (pin "N14") (pinfunction "VSS_N14") (pintype "passive"))
      (node (ref "U3") (pin "N16") (pinfunction "VSS_N16") (pintype "passive"))
      (node (ref "U3") (pin "N18") (pinfunction "VSS_N18") (pintype "passive"))
      (node (ref "U3") (pin "N2") (pinfunction "VSS_N2") (pintype "passive"))
      (node (ref "U3") (pin "N4") (pinfunction "VSS_N4") (pintype "passive"))
      (node (ref "U3") (pin "N6") (pinfunction "VSS_N6") (pintype "passive"))
      (node (ref "U3") (pin "N8") (pinfunction "VSS_N8") (pintype "passive"))
      (node (ref "U3") (pin "P1") (pinfunction "VSS_P1") (pintype "passive"))
      (node (ref "U3") (pin "P11") (pinfunction "VSS_P11") (pintype "passive"))
      (node (ref "U3") (pin "P13") (pinfunction "VSS_P13") (pintype "passive"))
      (node (ref "U3") (pin "P15") (pinfunction "VSS_P15") (pintype "passive"))
      (node (ref "U3") (pin "P17") (pinfunction "VSS_P17") (pintype "passive"))
      (node (ref "U3") (pin "P19") (pinfunction "VSS_P19") (pintype "passive"))
      (node (ref "U3") (pin "P21") (pinfunction "VSS_P21") (pintype "passive"))
      (node (ref "U3") (pin "P22") (pinfunction "VSS_P22") (pintype "passive"))
      (node (ref "U3") (pin "P3") (pinfunction "VSS_P3") (pintype "passive"))
      (node (ref "U3") (pin "P5") (pinfunction "VSS_P5") (pintype "passive"))
      (node (ref "U3") (pin "P7") (pinfunction "VSS_P7") (pintype "passive"))
      (node (ref "U3") (pin "P9") (pinfunction "VSS_P9") (pintype "passive"))
      (node (ref "U3") (pin "R10") (pinfunction "VSS_R10") (pintype "passive"))
      (node (ref "U3") (pin "R12") (pinfunction "VSS_R12") (pintype "passive"))
      (node (ref "U3") (pin "R14") (pinfunction "VSS_R14") (pintype "passive"))
      (node (ref "U3") (pin "R16") (pinfunction "VSS_R16") (pintype "passive"))
      (node (ref "U3") (pin "R18") (pinfunction "VSS_R18") (pintype "passive"))
      (node (ref "U3") (pin "R2") (pinfunction "VSS_R2") (pintype "passive"))
      (node (ref "U3") (pin "R20") (pinfunction "VSS_R20") (pintype "passive"))
      (node (ref "U3") (pin "R4") (pinfunction "VSS_R4") (pintype "passive"))
      (node (ref "U3") (pin "R6") (pinfunction "VSS_R6") (pintype "passive"))
      (node (ref "U3") (pin "R8") (pinfunction "VSS_R8") (pintype "passive"))
      (node (ref "U3") (pin "T1") (pinfunction "VSS_T1") (pintype "passive"))
      (node (ref "U3") (pin "T11") (pinfunction "VSS_T11") (pintype "passive"))
      (node (ref "U3") (pin "T13") (pinfunction "VSS_T13") (pintype "passive"))
      (node (ref "U3") (pin "T15") (pinfunction "VSS_T15") (pintype "passive"))
      (node (ref "U3") (pin "T17") (pinfunction "VSS_T17") (pintype "passive"))
      (node (ref "U3") (pin "T19") (pinfunction "VSS_T19") (pintype "passive"))
      (node (ref "U3") (pin "T21") (pinfunction "VSS_T21") (pintype "passive"))
      (node (ref "U3") (pin "T22") (pinfunction "VSS_T22") (pintype "passive"))
      (node (ref "U3") (pin "T3") (pinfunction "VSS_T3") (pintype "passive"))
      (node (ref "U3") (pin "T5") (pinfunction "VSS_T5") (pintype "passive"))
      (node (ref "U3") (pin "T7") (pinfunction "VSS_T7") (pintype "passive"))
      (node (ref "U3") (pin "T9") (pinfunction "VSS_T9") (pintype "passive"))
      (node (ref "U3") (pin "U10") (pinfunction "VSS_U10") (pintype "passive"))
      (node (ref "U3") (pin "U12") (pinfunction "VSS_U12") (pintype "passive"))
      (node (ref "U3") (pin "U14") (pinfunction "VSS_U14") (pintype "passive"))
      (node (ref "U3") (pin "U16") (pinfunction "VSS_U16") (pintype "passive"))
      (node (ref "U3") (pin "U18") (pinfunction "VSS_U18") (pintype "passive"))
      (node (ref "U3") (pin "U2") (pinfunction "VSS_U2") (pintype "passive"))
      (node (ref "U3") (pin "U20") (pinfunction "VSS_U20") (pintype "passive"))
      (node (ref "U3") (pin "U4") (pinfunction "VSS_U4") (pintype "passive"))
      (node (ref "U3") (pin "U6") (pinfunction "VSS_U6") (pintype "passive"))
      (node (ref "U3") (pin "U8") (pinfunction "VSS_U8") (pintype "passive"))
      (node (ref "U3") (pin "V1") (pinfunction "VSS_V1") (pintype "passive"))
      (node (ref "U3") (pin "V11") (pinfunction "VSS_V11") (pintype "passive"))
      (node (ref "U3") (pin "V13") (pinfunction "VSS_V13") (pintype "passive"))
      (node (ref "U3") (pin "V15") (pinfunction "VSS_V15") (pintype "passive"))
      (node (ref "U3") (pin "V17") (pinfunction "VSS_V17") (pintype "passive"))
      (node (ref "U3") (pin "V19") (pinfunction "VSS_V19") (pintype "passive"))
      (node (ref "U3") (pin "V21") (pinfunction "VSS_V21") (pintype "passive"))
      (node (ref "U3") (pin "V22") (pinfunction "VSS_V22") (pintype "passive"))
      (node (ref "U3") (pin "V3") (pinfunction "VSS_V3") (pintype "passive"))
      (node (ref "U3") (pin "V5") (pinfunction "VSS_V5") (pintype "passive"))
      (node (ref "U3") (pin "V7") (pinfunction "VSS_V7") (pintype "passive"))
      (node (ref "U3") (pin "V9") (pinfunction "VSS_V9") (pintype "passive"))
      (node (ref "U3") (pin "W10") (pinfunction "VSS_W10") (pintype "passive"))
      (node (ref "U3") (pin "W12") (pinfunction "VSS_W12") (pintype "passive"))
      (node (ref "U3") (pin "W14") (pinfunction "VSS_W14") (pintype "passive"))
      (node (ref "U3") (pin "W16") (pinfunction "VSS_W16") (pintype "passive"))
      (node (ref "U3") (pin "W18") (pinfunction "VSS_W18") (pintype "passive"))
      (node (ref "U3") (pin "W2") (pinfunction "VSS_W2") (pintype "passive"))
      (node (ref "U3") (pin "W20") (pinfunction "VSS_W20") (pintype "passive"))
      (node (ref "U3") (pin "W4") (pinfunction "VSS_W4") (pintype "passive"))
      (node (ref "U3") (pin "W6") (pinfunction "VSS_W6") (pintype "passive"))
      (node (ref "U3") (pin "W8") (pinfunction "VSS_W8") (pintype "passive"))
      (node (ref "U3") (pin "Y1") (pinfunction "VSS_Y1") (pintype "passive"))
      (node (ref "U3") (pin "Y11") (pinfunction "VSS_Y11") (pintype "passive"))
      (node (ref "U3") (pin "Y13") (pinfunction "VSS_Y13") (pintype "passive"))
      (node (ref "U3") (pin "Y15") (pinfunction "VSS_Y15") (pintype "passive"))
      (node (ref "U3") (pin "Y17") (pinfunction "VSS_Y17") (pintype "passive"))
      (node (ref "U3") (pin "Y19") (pinfunction "VSS_Y19") (pintype "passive"))
      (node (ref "U3") (pin "Y21") (pinfunction "VSS_Y21") (pintype "passive"))
      (node (ref "U3") (pin "Y22") (pinfunction "VSS_Y22") (pintype "passive"))
      (node (ref "U3") (pin "Y3") (pinfunction "VSS_Y3") (pintype "passive"))
      (node (ref "U3") (pin "Y5") (pinfunction "VSS_Y5") (pintype "passive"))
      (node (ref "U3") (pin "Y7") (pinfunction "VSS_Y7") (pintype "passive"))
      (node (ref "U3") (pin "Y9") (pinfunction "VSS_Y9") (pintype "passive"))
      (node (ref "U4") (pin "A10") (pinfunction "VSS_A10") (pintype "passive"))
      (node (ref "U4") (pin "A12") (pinfunction "VSS_A12") (pintype "passive"))
      (node (ref "U4") (pin "A14") (pinfunction "VSS_A14") (pintype "passive"))
      (node (ref "U4") (pin "A16") (pinfunction "VSS_A16") (pintype "passive"))
      (node (ref "U4") (pin "A18") (pinfunction "VSS_A18") (pintype "passive"))
      (node (ref "U4") (pin "A2") (pinfunction "VSS_A2") (pintype "passive"))
      (node (ref "U4") (pin "A20") (pinfunction "VSS_A20") (pintype "passive"))
      (node (ref "U4") (pin "A4") (pinfunction "VSS_A4") (pintype "passive"))
      (node (ref "U4") (pin "A6") (pinfunction "VSS_A6") (pintype "passive"))
      (node (ref "U4") (pin "A8") (pinfunction "VSS_A8") (pintype "passive"))
      (node (ref "U4") (pin "AA10") (pinfunction "VSS_AA10") (pintype "passive"))
      (node (ref "U4") (pin "AA12") (pinfunction "VSS_AA12") (pintype "passive"))
      (node (ref "U4") (pin "AA14") (pinfunction "VSS_AA14") (pintype "passive"))
      (node (ref "U4") (pin "AA16") (pinfunction "VSS_AA16") (pintype "passive"))
      (node (ref "U4") (pin "AA18") (pinfunction "VSS_AA18") (pintype "passive"))
      (node (ref "U4") (pin "AA2") (pinfunction "VSS_AA2") (pintype "passive"))
      (node (ref "U4") (pin "AA4") (pinfunction "VSS_AA4") (pintype "passive"))
      (node (ref "U4") (pin "AA6") (pinfunction "VSS_AA6") (pintype "passive"))
      (node (ref "U4") (pin "AA8") (pinfunction "VSS_AA8") (pintype "passive"))
      (node (ref "U4") (pin "AB11") (pinfunction "VSS_AB11") (pintype "passive"))
      (node (ref "U4") (pin "AB13") (pinfunction "VSS_AB13") (pintype "passive"))
      (node (ref "U4") (pin "AB15") (pinfunction "VSS_AB15") (pintype "passive"))
      (node (ref "U4") (pin "AB17") (pinfunction "VSS_AB17") (pintype "passive"))
      (node (ref "U4") (pin "AB3") (pinfunction "VSS_AB3") (pintype "passive"))
      (node (ref "U4") (pin "AB5") (pinfunction "VSS_AB5") (pintype "passive"))
      (node (ref "U4") (pin "AB7") (pinfunction "VSS_AB7") (pintype "passive"))
      (node (ref "U4") (pin "AB9") (pinfunction "VSS_AB9") (pintype "passive"))
      (node (ref "U4") (pin "B1") (pinfunction "VSS_B1") (pintype "passive"))
      (node (ref "U4") (pin "B11") (pinfunction "VSS_B11") (pintype "passive"))
      (node (ref "U4") (pin "B13") (pinfunction "VSS_B13") (pintype "passive"))
      (node (ref "U4") (pin "B15") (pinfunction "VSS_B15") (pintype "passive"))
      (node (ref "U4") (pin "B17") (pinfunction "VSS_B17") (pintype "passive"))
      (node (ref "U4") (pin "B19") (pinfunction "VSS_B19") (pintype "passive"))
      (node (ref "U4") (pin "B21") (pinfunction "VSS_B21") (pintype "passive"))
      (node (ref "U4") (pin "B22") (pinfunction "VSS_B22") (pintype "passive"))
      (node (ref "U4") (pin "B3") (pinfunction "VSS_B3") (pintype "passive"))
      (node (ref "U4") (pin "B5") (pinfunction "VSS_B5") (pintype "passive"))
      (node (ref "U4") (pin "B7") (pinfunction "VSS_B7") (pintype "passive"))
      (node (ref "U4") (pin "B9") (pinfunction "VSS_B9") (pintype "passive"))
      (node (ref "U4") (pin "C10") (pinfunction "VSS_C10") (pintype "passive"))
      (node (ref "U4") (pin "C12") (pinfunction "VSS_C12") (pintype "passive"))
      (node (ref "U4") (pin "C14") (pinfunction "VSS_C14") (pintype "passive"))
      (node (ref "U4") (pin "C16") (pinfunction "VSS_C16") (pintype "passive"))
      (node (ref "U4") (pin "C18") (pinfunction "VSS_C18") (pintype "passive"))
      (node (ref "U4") (pin "C2") (pinfunction "VSS_C2") (pintype "passive"))
      (node (ref "U4") (pin "C20") (pinfunction "VSS_C20") (pintype "passive"))
      (node (ref "U4") (pin "C4") (pinfunction "VSS_C4") (pintype "passive"))
      (node (ref "U4") (pin "C6") (pinfunction "VSS_C6") (pintype "passive"))
      (node (ref "U4") (pin "C8") (pinfunction "VSS_C8") (pintype "passive"))
      (node (ref "U4") (pin "D1") (pinfunction "VSS_D1") (pintype "passive"))
      (node (ref "U4") (pin "D11") (pinfunction "VSS_D11") (pintype "passive"))
      (node (ref "U4") (pin "D13") (pinfunction "VSS_D13") (pintype "passive"))
      (node (ref "U4") (pin "D15") (pinfunction "VSS_D15") (pintype "passive"))
      (node (ref "U4") (pin "D17") (pinfunction "VSS_D17") (pintype "passive"))
      (node (ref "U4") (pin "D19") (pinfunction "VSS_D19") (pintype "passive"))
      (node (ref "U4") (pin "D21") (pinfunction "VSS_D21") (pintype "passive"))
      (node (ref "U4") (pin "D22") (pinfunction "VSS_D22") (pintype "passive"))
      (node (ref "U4") (pin "D3") (pinfunction "VSS_D3") (pintype "passive"))
      (node (ref "U4") (pin "D5") (pinfunction "VSS_D5") (pintype "passive"))
      (node (ref "U4") (pin "D7") (pinfunction "VSS_D7") (pintype "passive"))
      (node (ref "U4") (pin "D9") (pinfunction "VSS_D9") (pintype "passive"))
      (node (ref "U4") (pin "E10") (pinfunction "VSS_E10") (pintype "passive"))
      (node (ref "U4") (pin "E12") (pinfunction "VSS_E12") (pintype "passive"))
      (node (ref "U4") (pin "E14") (pinfunction "VSS_E14") (pintype "passive"))
      (node (ref "U4") (pin "E16") (pinfunction "VSS_E16") (pintype "passive"))
      (node (ref "U4") (pin "E18") (pinfunction "VSS_E18") (pintype "passive"))
      (node (ref "U4") (pin "E2") (pinfunction "VSS_E2") (pintype "passive"))
      (node (ref "U4") (pin "E20") (pinfunction "VSS_E20") (pintype "passive"))
      (node (ref "U4") (pin "E4") (pinfunction "VSS_E4") (pintype "passive"))
      (node (ref "U4") (pin "E6") (pinfunction "VSS_E6") (pintype "passive"))
      (node (ref "U4") (pin "E8") (pinfunction "VSS_E8") (pintype "passive"))
      (node (ref "U4") (pin "F1") (pinfunction "VSS_F1") (pintype "passive"))
      (node (ref "U4") (pin "F11") (pinfunction "VSS_F11") (pintype "passive"))
      (node (ref "U4") (pin "F13") (pinfunction "VSS_F13") (pintype "passive"))
      (node (ref "U4") (pin "F15") (pinfunction "VSS_F15") (pintype "passive"))
      (node (ref "U4") (pin "F17") (pinfunction "VSS_F17") (pintype "passive"))
      (node (ref "U4") (pin "F19") (pinfunction "VSS_F19") (pintype "passive"))
      (node (ref "U4") (pin "F21") (pinfunction "VSS_F21") (pintype "passive"))
      (node (ref "U4") (pin "F22") (pinfunction "VSS_F22") (pintype "passive"))
      (node (ref "U4") (pin "F3") (pinfunction "VSS_F3") (pintype "passive"))
      (node (ref "U4") (pin "F5") (pinfunction "VSS_F5") (pintype "passive"))
      (node (ref "U4") (pin "F7") (pinfunction "VSS_F7") (pintype "passive"))
      (node (ref "U4") (pin "F9") (pinfunction "VSS_F9") (pintype "passive"))
      (node (ref "U4") (pin "G10") (pinfunction "VSS_G10") (pintype "passive"))
      (node (ref "U4") (pin "G12") (pinfunction "VSS_G12") (pintype "passive"))
      (node (ref "U4") (pin "G14") (pinfunction "VSS_G14") (pintype "passive"))
      (node (ref "U4") (pin "G16") (pinfunction "VSS_G16") (pintype "passive"))
      (node (ref "U4") (pin "G18") (pinfunction "VSS_G18") (pintype "passive"))
      (node (ref "U4") (pin "G2") (pinfunction "VSS_G2") (pintype "passive"))
      (node (ref "U4") (pin "G20") (pinfunction "VSS_G20") (pintype "passive"))
      (node (ref "U4") (pin "G4") (pinfunction "VSS_G4") (pintype "passive"))
      (node (ref "U4") (pin "G6") (pinfunction "VSS_G6") (pintype "passive"))
      (node (ref "U4") (pin "G8") (pinfunction "VSS_G8") (pintype "passive"))
      (node (ref "U4") (pin "H1") (pinfunction "VSS_H1") (pintype "passive"))
      (node (ref "U4") (pin "H11") (pinfunction "VSS_H11") (pintype "passive"))
      (node (ref "U4") (pin "H13") (pinfunction "VSS_H13") (pintype "passive"))
      (node (ref "U4") (pin "H15") (pinfunction "VSS_H15") (pintype "passive"))
      (node (ref "U4") (pin "H17") (pinfunction "VSS_H17") (pintype "passive"))
      (node (ref "U4") (pin "H19") (pinfunction "VSS_H19") (pintype "passive"))
      (node (ref "U4") (pin "H21") (pinfunction "VSS_H21") (pintype "passive"))
      (node (ref "U4") (pin "H22") (pinfunction "VSS_H22") (pintype "passive"))
      (node (ref "U4") (pin "H3") (pinfunction "VSS_H3") (pintype "passive"))
      (node (ref "U4") (pin "H5") (pinfunction "VSS_H5") (pintype "passive"))
      (node (ref "U4") (pin "H7") (pinfunction "VSS_H7") (pintype "passive"))
      (node (ref "U4") (pin "H9") (pinfunction "VSS_H9") (pintype "passive"))
      (node (ref "U4") (pin "J10") (pinfunction "VSS_J10") (pintype "passive"))
      (node (ref "U4") (pin "J12") (pinfunction "VSS_J12") (pintype "passive"))
      (node (ref "U4") (pin "J14") (pinfunction "VSS_J14") (pintype "passive"))
      (node (ref "U4") (pin "J16") (pinfunction "VSS_J16") (pintype "passive"))
      (node (ref "U4") (pin "J18") (pinfunction "VSS_J18") (pintype "passive"))
      (node (ref "U4") (pin "J2") (pinfunction "VSS_J2") (pintype "passive"))
      (node (ref "U4") (pin "J20") (pinfunction "VSS_J20") (pintype "passive"))
      (node (ref "U4") (pin "J4") (pinfunction "VSS_J4") (pintype "passive"))
      (node (ref "U4") (pin "J6") (pinfunction "VSS_J6") (pintype "passive"))
      (node (ref "U4") (pin "J8") (pinfunction "VSS_J8") (pintype "passive"))
      (node (ref "U4") (pin "K1") (pinfunction "VSS_K1") (pintype "passive"))
      (node (ref "U4") (pin "K11") (pinfunction "VSS_K11") (pintype "passive"))
      (node (ref "U4") (pin "K13") (pinfunction "VSS_K13") (pintype "passive"))
      (node (ref "U4") (pin "K15") (pinfunction "VSS_K15") (pintype "passive"))
      (node (ref "U4") (pin "K17") (pinfunction "VSS_K17") (pintype "passive"))
      (node (ref "U4") (pin "K19") (pinfunction "VSS_K19") (pintype "passive"))
      (node (ref "U4") (pin "K21") (pinfunction "VSS_K21") (pintype "passive"))
      (node (ref "U4") (pin "K22") (pinfunction "VSS_K22") (pintype "passive"))
      (node (ref "U4") (pin "K3") (pinfunction "VSS_K3") (pintype "passive"))
      (node (ref "U4") (pin "K5") (pinfunction "VSS_K5") (pintype "passive"))
      (node (ref "U4") (pin "K7") (pinfunction "VSS_K7") (pintype "passive"))
      (node (ref "U4") (pin "K9") (pinfunction "VSS_K9") (pintype "passive"))
      (node (ref "U4") (pin "L10") (pinfunction "VSS_L10") (pintype "passive"))
      (node (ref "U4") (pin "L12") (pinfunction "VSS_L12") (pintype "passive"))
      (node (ref "U4") (pin "L14") (pinfunction "VSS_L14") (pintype "passive"))
      (node (ref "U4") (pin "L16") (pinfunction "VSS_L16") (pintype "passive"))
      (node (ref "U4") (pin "L18") (pinfunction "VSS_L18") (pintype "passive"))
      (node (ref "U4") (pin "L2") (pinfunction "VSS_L2") (pintype "passive"))
      (node (ref "U4") (pin "L20") (pinfunction "VSS_L20") (pintype "passive"))
      (node (ref "U4") (pin "L4") (pinfunction "VSS_L4") (pintype "passive"))
      (node (ref "U4") (pin "L6") (pinfunction "VSS_L6") (pintype "passive"))
      (node (ref "U4") (pin "L8") (pinfunction "VSS_L8") (pintype "passive"))
      (node (ref "U4") (pin "M1") (pinfunction "VSS_M1") (pintype "passive"))
      (node (ref "U4") (pin "M11") (pinfunction "VSS_M11") (pintype "passive"))
      (node (ref "U4") (pin "M13") (pinfunction "VSS_M13") (pintype "passive"))
      (node (ref "U4") (pin "M15") (pinfunction "VSS_M15") (pintype "passive"))
      (node (ref "U4") (pin "M17") (pinfunction "VSS_M17") (pintype "passive"))
      (node (ref "U4") (pin "M19") (pinfunction "VSS_M19") (pintype "passive"))
      (node (ref "U4") (pin "M21") (pinfunction "VSS_M21") (pintype "passive"))
      (node (ref "U4") (pin "M3") (pinfunction "VSS_M3") (pintype "passive"))
      (node (ref "U4") (pin "M5") (pinfunction "VSS_M5") (pintype "passive"))
      (node (ref "U4") (pin "M7") (pinfunction "VSS_M7") (pintype "passive"))
      (node (ref "U4") (pin "M9") (pinfunction "VSS_M9") (pintype "passive"))
      (node (ref "U4") (pin "N10") (pinfunction "VSS_N10") (pintype "passive"))
      (node (ref "U4") (pin "N12") (pinfunction "VSS_N12") (pintype "passive"))
      (node (ref "U4") (pin "N14") (pinfunction "VSS_N14") (pintype "passive"))
      (node (ref "U4") (pin "N16") (pinfunction "VSS_N16") (pintype "passive"))
      (node (ref "U4") (pin "N18") (pinfunction "VSS_N18") (pintype "passive"))
      (node (ref "U4") (pin "N2") (pinfunction "VSS_N2") (pintype "passive"))
      (node (ref "U4") (pin "N4") (pinfunction "VSS_N4") (pintype "passive"))
      (node (ref "U4") (pin "N6") (pinfunction "VSS_N6") (pintype "passive"))
      (node (ref "U4") (pin "N8") (pinfunction "VSS_N8") (pintype "passive"))
      (node (ref "U4") (pin "P1") (pinfunction "VSS_P1") (pintype "passive"))
      (node (ref "U4") (pin "P11") (pinfunction "VSS_P11") (pintype "passive"))
      (node (ref "U4") (pin "P13") (pinfunction "VSS_P13") (pintype "passive"))
      (node (ref "U4") (pin "P15") (pinfunction "VSS_P15") (pintype "passive"))
      (node (ref "U4") (pin "P17") (pinfunction "VSS_P17") (pintype "passive"))
      (node (ref "U4") (pin "P19") (pinfunction "VSS_P19") (pintype "passive"))
      (node (ref "U4") (pin "P21") (pinfunction "VSS_P21") (pintype "passive"))
      (node (ref "U4") (pin "P22") (pinfunction "VSS_P22") (pintype "passive"))
      (node (ref "U4") (pin "P3") (pinfunction "VSS_P3") (pintype "passive"))
      (node (ref "U4") (pin "P5") (pinfunction "VSS_P5") (pintype "passive"))
      (node (ref "U4") (pin "P7") (pinfunction "VSS_P7") (pintype "passive"))
      (node (ref "U4") (pin "P9") (pinfunction "VSS_P9") (pintype "passive"))
      (node (ref "U4") (pin "R10") (pinfunction "VSS_R10") (pintype "passive"))
      (node (ref "U4") (pin "R12") (pinfunction "VSS_R12") (pintype "passive"))
      (node (ref "U4") (pin "R14") (pinfunction "VSS_R14") (pintype "passive"))
      (node (ref "U4") (pin "R16") (pinfunction "VSS_R16") (pintype "passive"))
      (node (ref "U4") (pin "R18") (pinfunction "VSS_R18") (pintype "passive"))
      (node (ref "U4") (pin "R2") (pinfunction "VSS_R2") (pintype "passive"))
      (node (ref "U4") (pin "R20") (pinfunction "VSS_R20") (pintype "passive"))
      (node (ref "U4") (pin "R4") (pinfunction "VSS_R4") (pintype "passive"))
      (node (ref "U4") (pin "R6") (pinfunction "VSS_R6") (pintype "passive"))
      (node (ref "U4") (pin "R8") (pinfunction "VSS_R8") (pintype "passive"))
      (node (ref "U4") (pin "T1") (pinfunction "VSS_T1") (pintype "passive"))
      (node (ref "U4") (pin "T11") (pinfunction "VSS_T11") (pintype "passive"))
      (node (ref "U4") (pin "T13") (pinfunction "VSS_T13") (pintype "passive"))
      (node (ref "U4") (pin "T15") (pinfunction "VSS_T15") (pintype "passive"))
      (node (ref "U4") (pin "T17") (pinfunction "VSS_T17") (pintype "passive"))
      (node (ref "U4") (pin "T19") (pinfunction "VSS_T19") (pintype "passive"))
      (node (ref "U4") (pin "T21") (pinfunction "VSS_T21") (pintype "passive"))
      (node (ref "U4") (pin "T22") (pinfunction "VSS_T22") (pintype "passive"))
      (node (ref "U4") (pin "T3") (pinfunction "VSS_T3") (pintype "passive"))
      (node (ref "U4") (pin "T5") (pinfunction "VSS_T5") (pintype "passive"))
      (node (ref "U4") (pin "T7") (pinfunction "VSS_T7") (pintype "passive"))
      (node (ref "U4") (pin "T9") (pinfunction "VSS_T9") (pintype "passive"))
      (node (ref "U4") (pin "U10") (pinfunction "VSS_U10") (pintype "passive"))
      (node (ref "U4") (pin "U12") (pinfunction "VSS_U12") (pintype "passive"))
      (node (ref "U4") (pin "U14") (pinfunction "VSS_U14") (pintype "passive"))
      (node (ref "U4") (pin "U16") (pinfunction "VSS_U16") (pintype "passive"))
      (node (ref "U4") (pin "U18") (pinfunction "VSS_U18") (pintype "passive"))
      (node (ref "U4") (pin "U2") (pinfunction "VSS_U2") (pintype "passive"))
      (node (ref "U4") (pin "U20") (pinfunction "VSS_U20") (pintype "passive"))
      (node (ref "U4") (pin "U4") (pinfunction "VSS_U4") (pintype "passive"))
      (node (ref "U4") (pin "U6") (pinfunction "VSS_U6") (pintype "passive"))
      (node (ref "U4") (pin "U8") (pinfunction "VSS_U8") (pintype "passive"))
      (node (ref "U4") (pin "V1") (pinfunction "VSS_V1") (pintype "passive"))
      (node (ref "U4") (pin "V11") (pinfunction "VSS_V11") (pintype "passive"))
      (node (ref "U4") (pin "V13") (pinfunction "VSS_V13") (pintype "passive"))
      (node (ref "U4") (pin "V15") (pinfunction "VSS_V15") (pintype "passive"))
      (node (ref "U4") (pin "V17") (pinfunction "VSS_V17") (pintype "passive"))
      (node (ref "U4") (pin "V19") (pinfunction "VSS_V19") (pintype "passive"))
      (node (ref "U4") (pin "V21") (pinfunction "VSS_V21") (pintype "passive"))
      (node (ref "U4") (pin "V22") (pinfunction "VSS_V22") (pintype "passive"))
      (node (ref "U4") (pin "V3") (pinfunction "VSS_V3") (pintype "passive"))
      (node (ref "U4") (pin "V5") (pinfunction "VSS_V5") (pintype "passive"))
      (node (ref "U4") (pin "V7") (pinfunction "VSS_V7") (pintype "passive"))
      (node (ref "U4") (pin "V9") (pinfunction "VSS_V9") (pintype "passive"))
      (node (ref "U4") (pin "W10") (pinfunction "VSS_W10") (pintype "passive"))
      (node (ref "U4") (pin "W12") (pinfunction "VSS_W12") (pintype "passive"))
      (node (ref "U4") (pin "W14") (pinfunction "VSS_W14") (pintype "passive"))
      (node (ref "U4") (pin "W16") (pinfunction "VSS_W16") (pintype "passive"))
      (node (ref "U4") (pin "W18") (pinfunction "VSS_W18") (pintype "passive"))
      (node (ref "U4") (pin "W2") (pinfunction "VSS_W2") (pintype "passive"))
      (node (ref "U4") (pin "W20") (pinfunction "VSS_W20") (pintype "passive"))
      (node (ref "U4") (pin "W4") (pinfunction "VSS_W4") (pintype "passive"))
      (node (ref "U4") (pin "W6") (pinfunction "VSS_W6") (pintype "passive"))
      (node (ref "U4") (pin "W8") (pinfunction "VSS_W8") (pintype "passive"))
      (node (ref "U4") (pin "Y1") (pinfunction "VSS_Y1") (pintype "passive"))
      (node (ref "U4") (pin "Y11") (pinfunction "VSS_Y11") (pintype "passive"))
      (node (ref "U4") (pin "Y13") (pinfunction "VSS_Y13") (pintype "passive"))
      (node (ref "U4") (pin "Y15") (pinfunction "VSS_Y15") (pintype "passive"))
      (node (ref "U4") (pin "Y17") (pinfunction "VSS_Y17") (pintype "passive"))
      (node (ref "U4") (pin "Y19") (pinfunction "VSS_Y19") (pintype "passive"))
      (node (ref "U4") (pin "Y21") (pinfunction "VSS_Y21") (pintype "passive"))
      (node (ref "U4") (pin "Y22") (pinfunction "VSS_Y22") (pintype "passive"))
      (node (ref "U4") (pin "Y3") (pinfunction "VSS_Y3") (pintype "passive"))
      (node (ref "U4") (pin "Y5") (pinfunction "VSS_Y5") (pintype "passive"))
      (node (ref "U4") (pin "Y7") (pinfunction "VSS_Y7") (pintype "passive"))
      (node (ref "U4") (pin "Y9") (pinfunction "VSS_Y9") (pintype "passive"))
    )
  )
)
